# Cynara_Viride.net
KiCad netlist of a schematic drawn in EAGLE
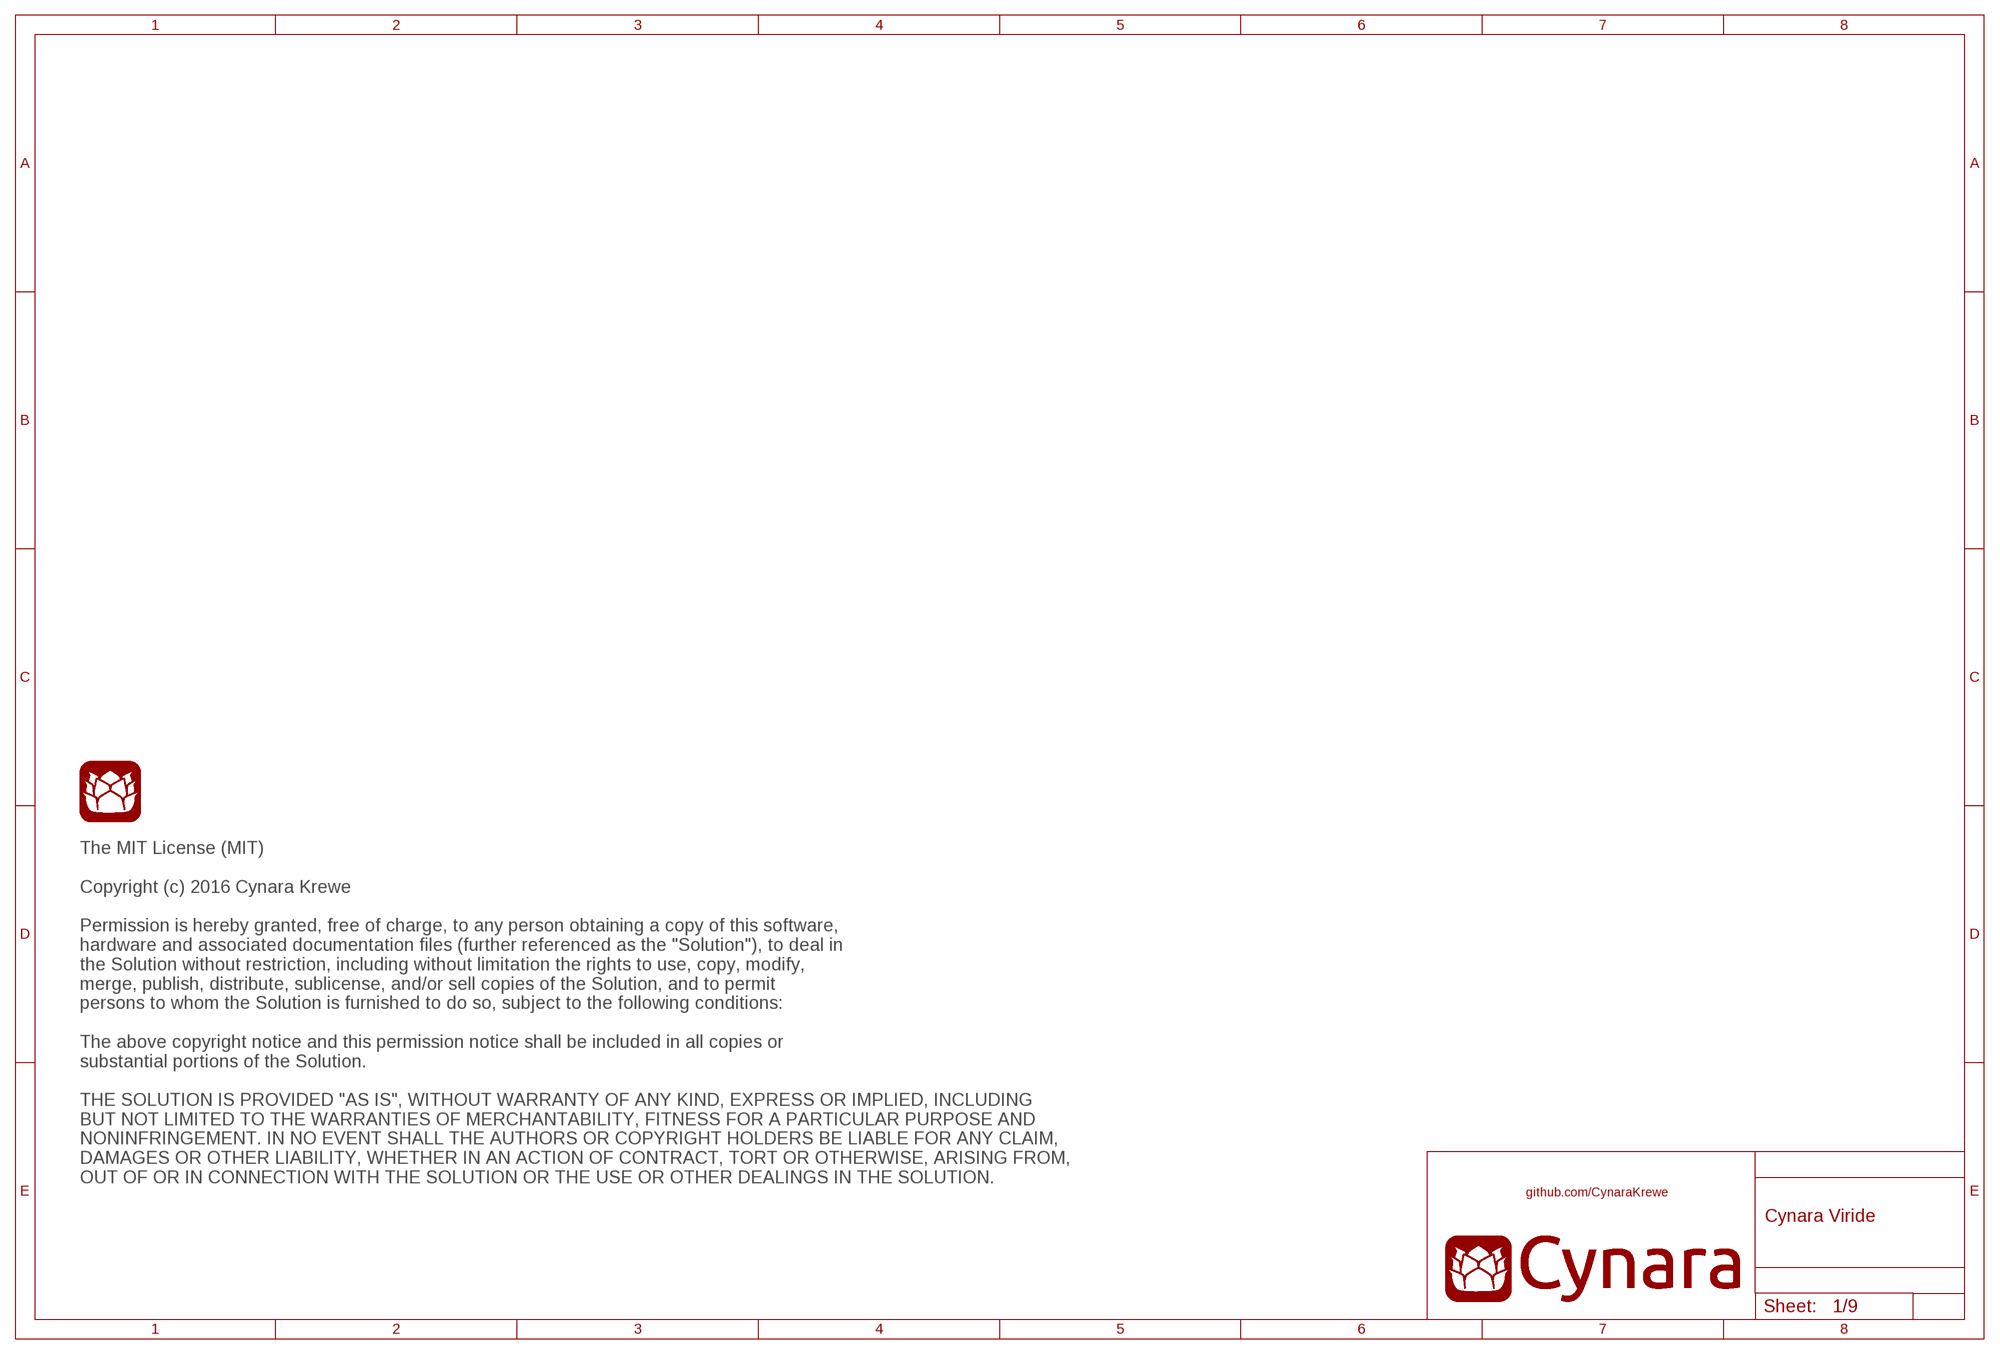
[diagram p0: schematic, sheet 1]
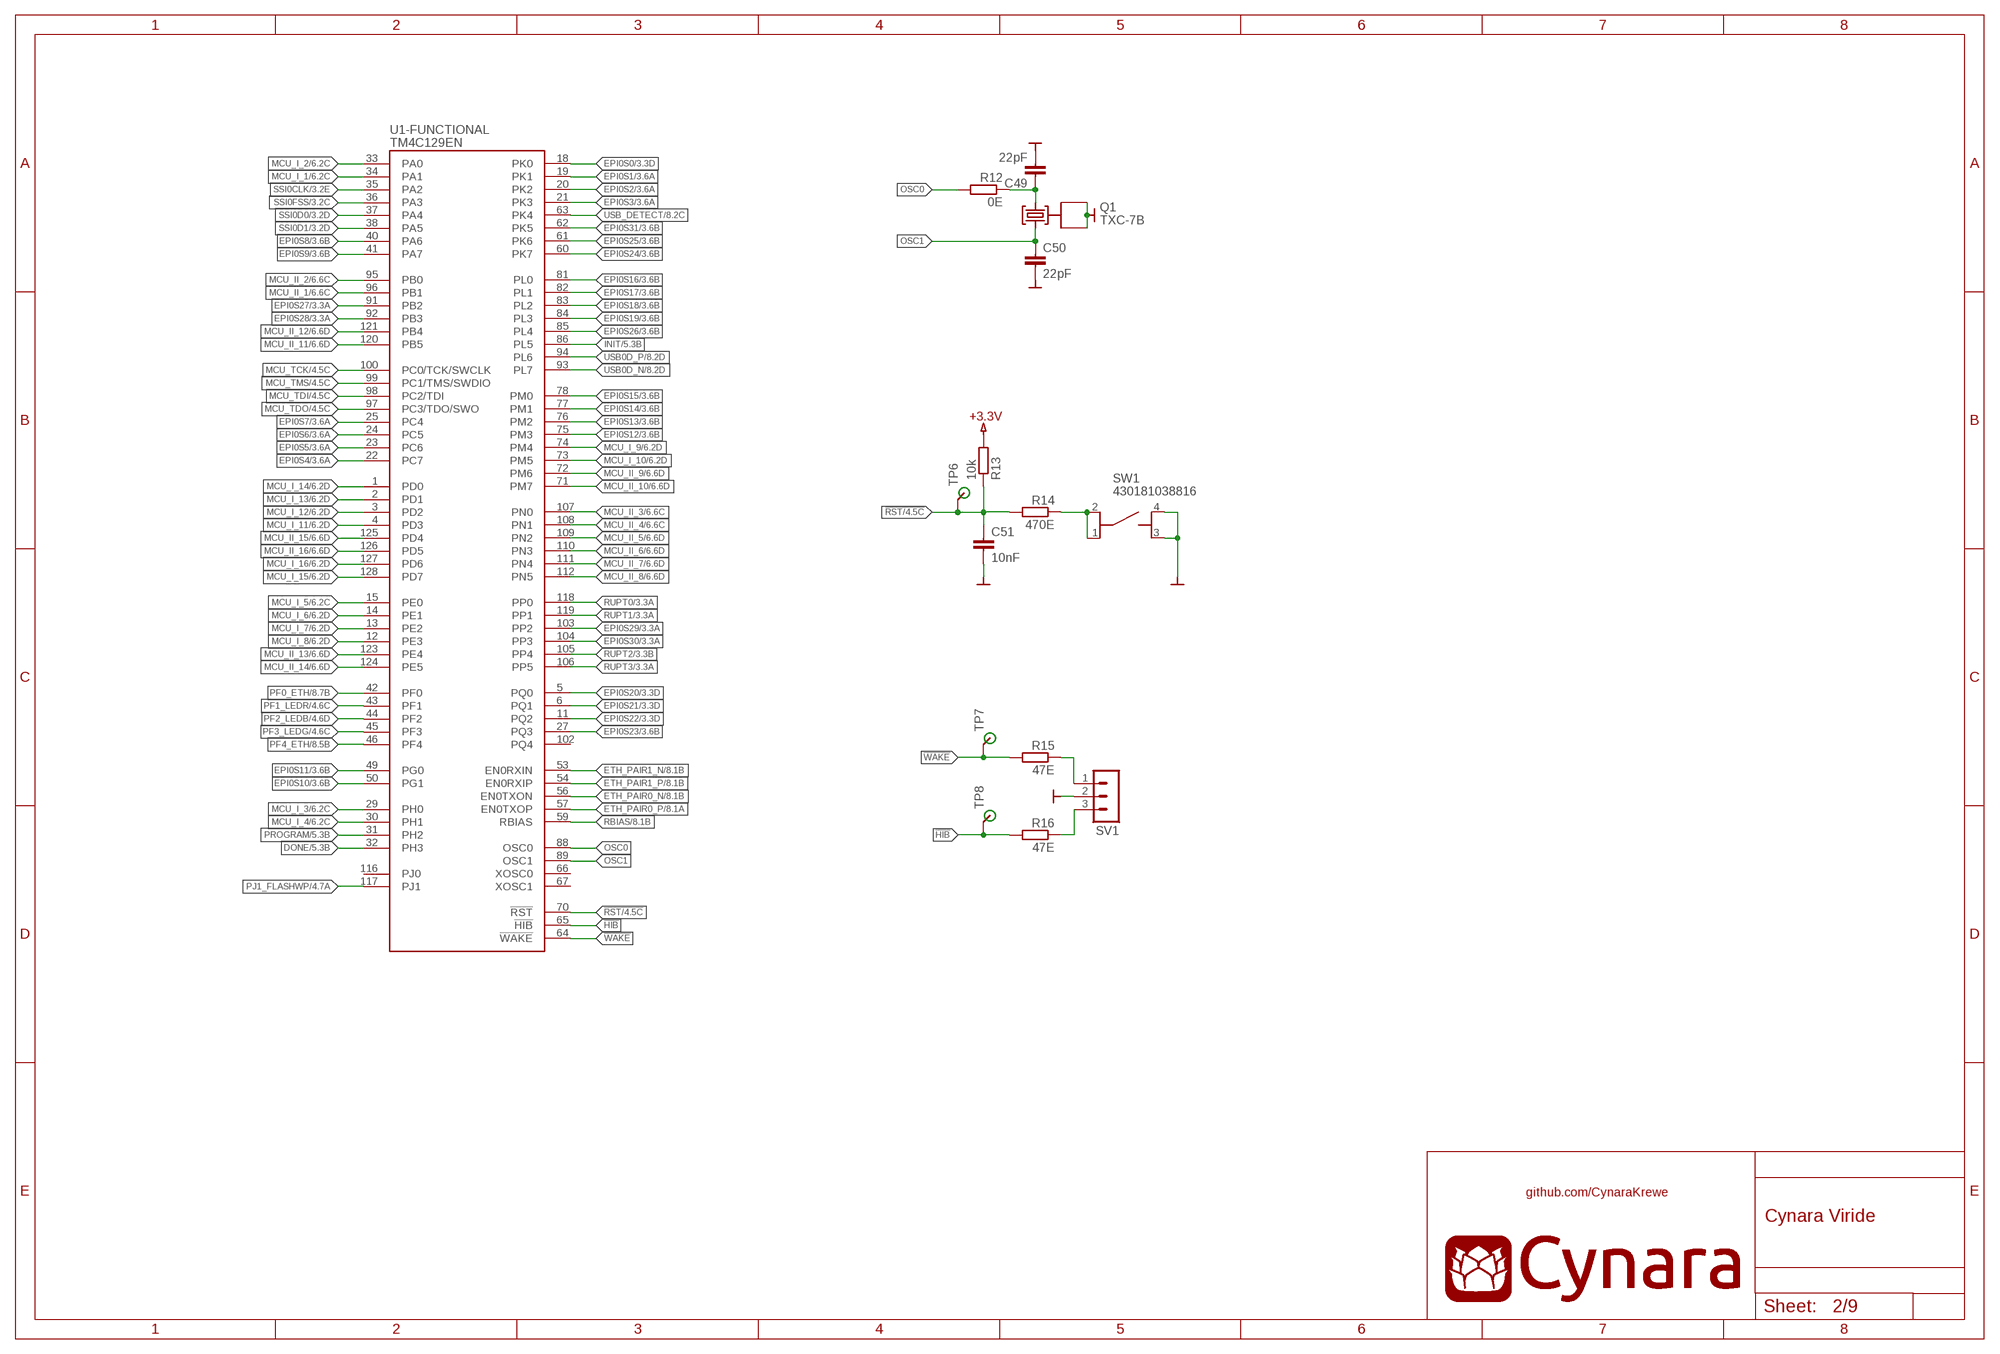
[diagram p1: schematic, sheet 2]
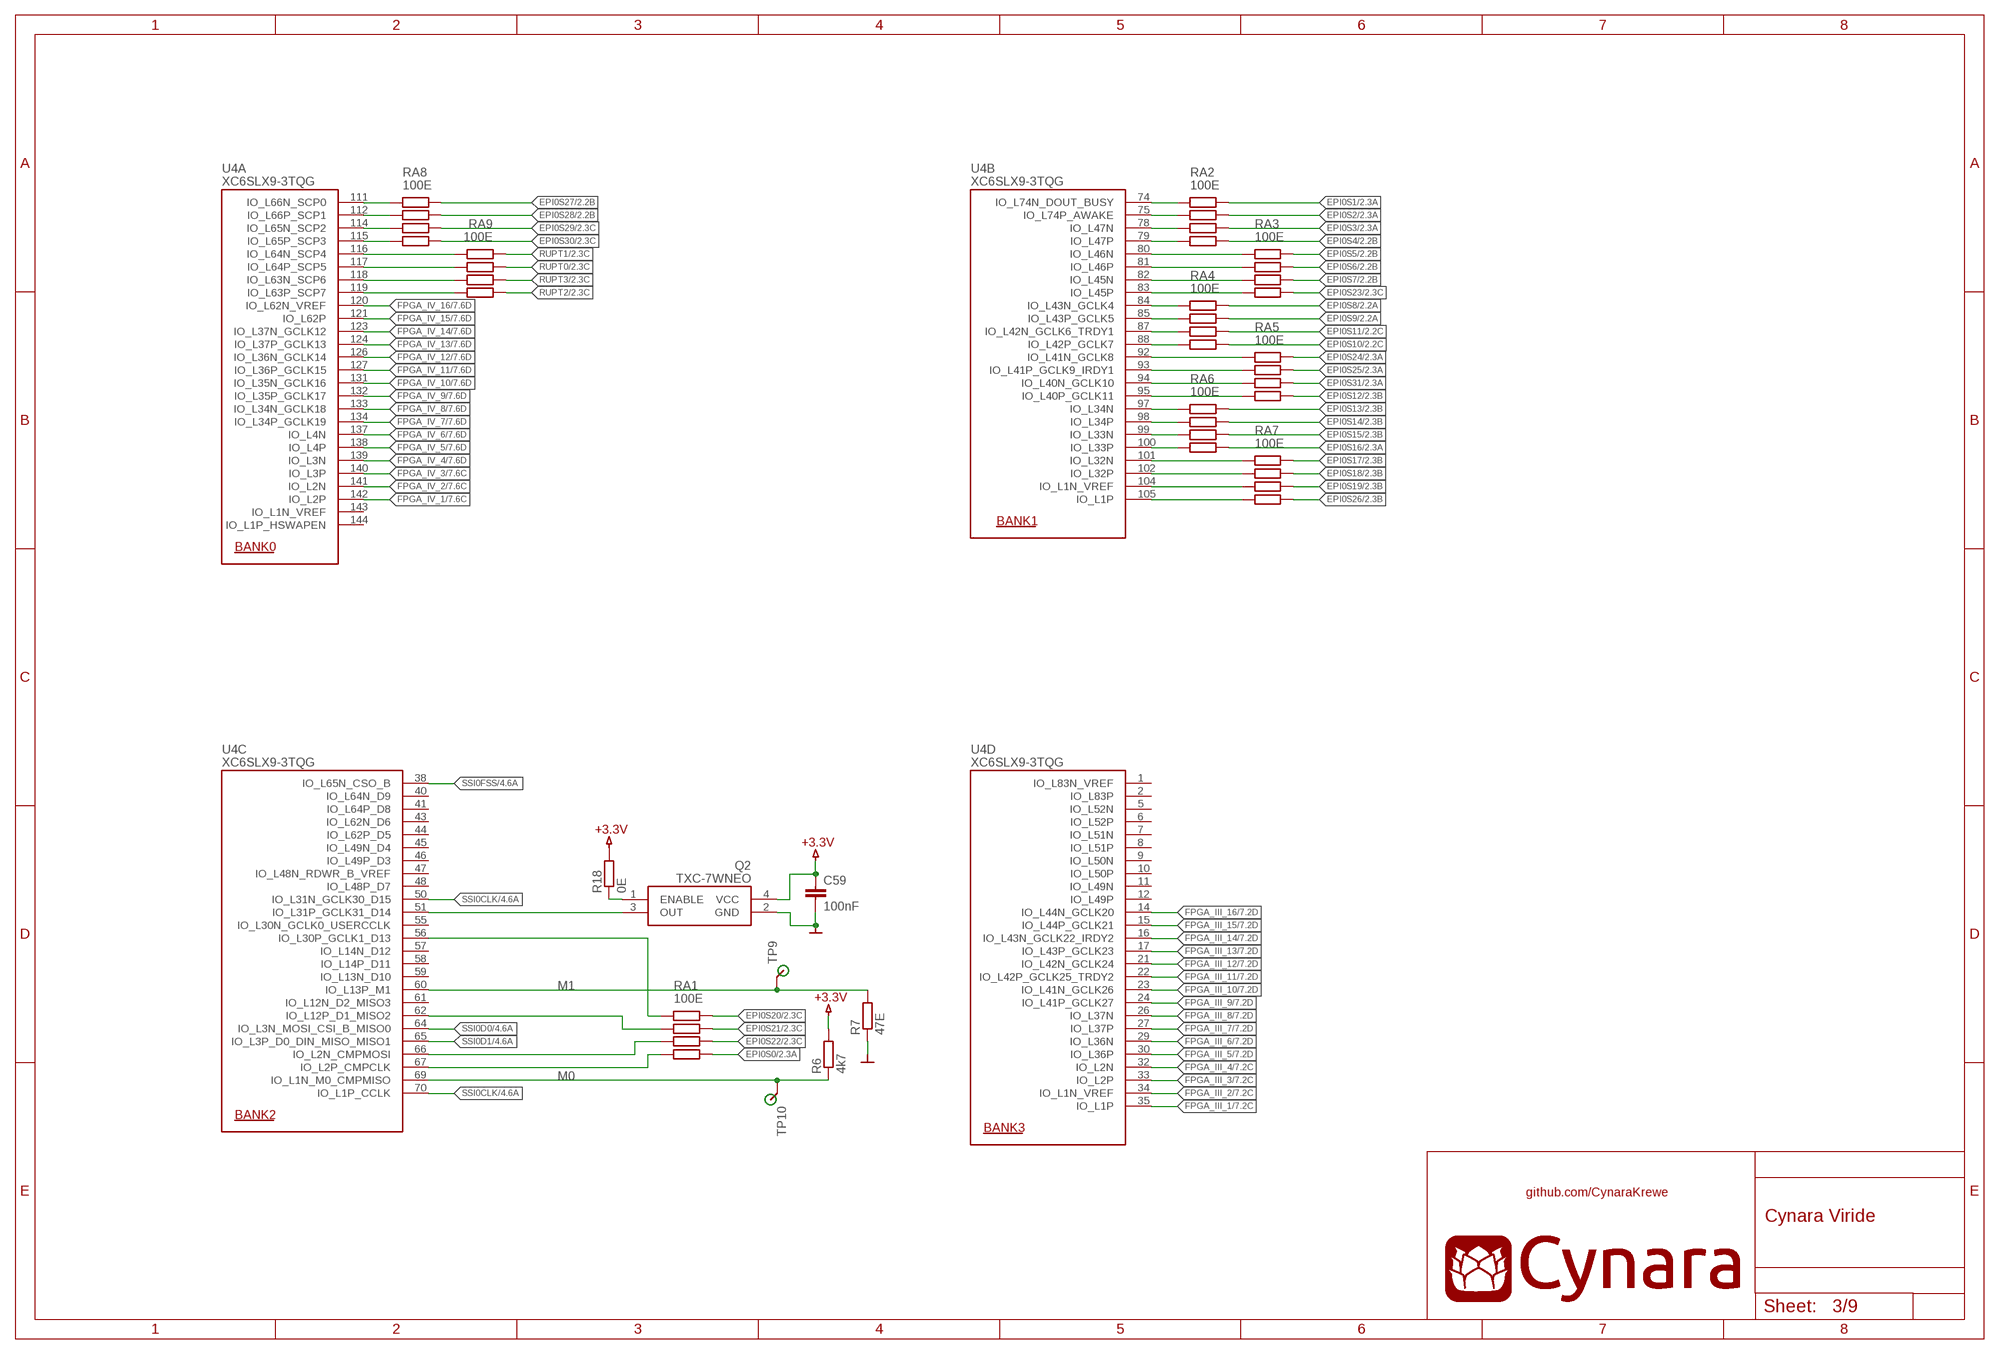
[diagram p2: schematic, sheet 3]
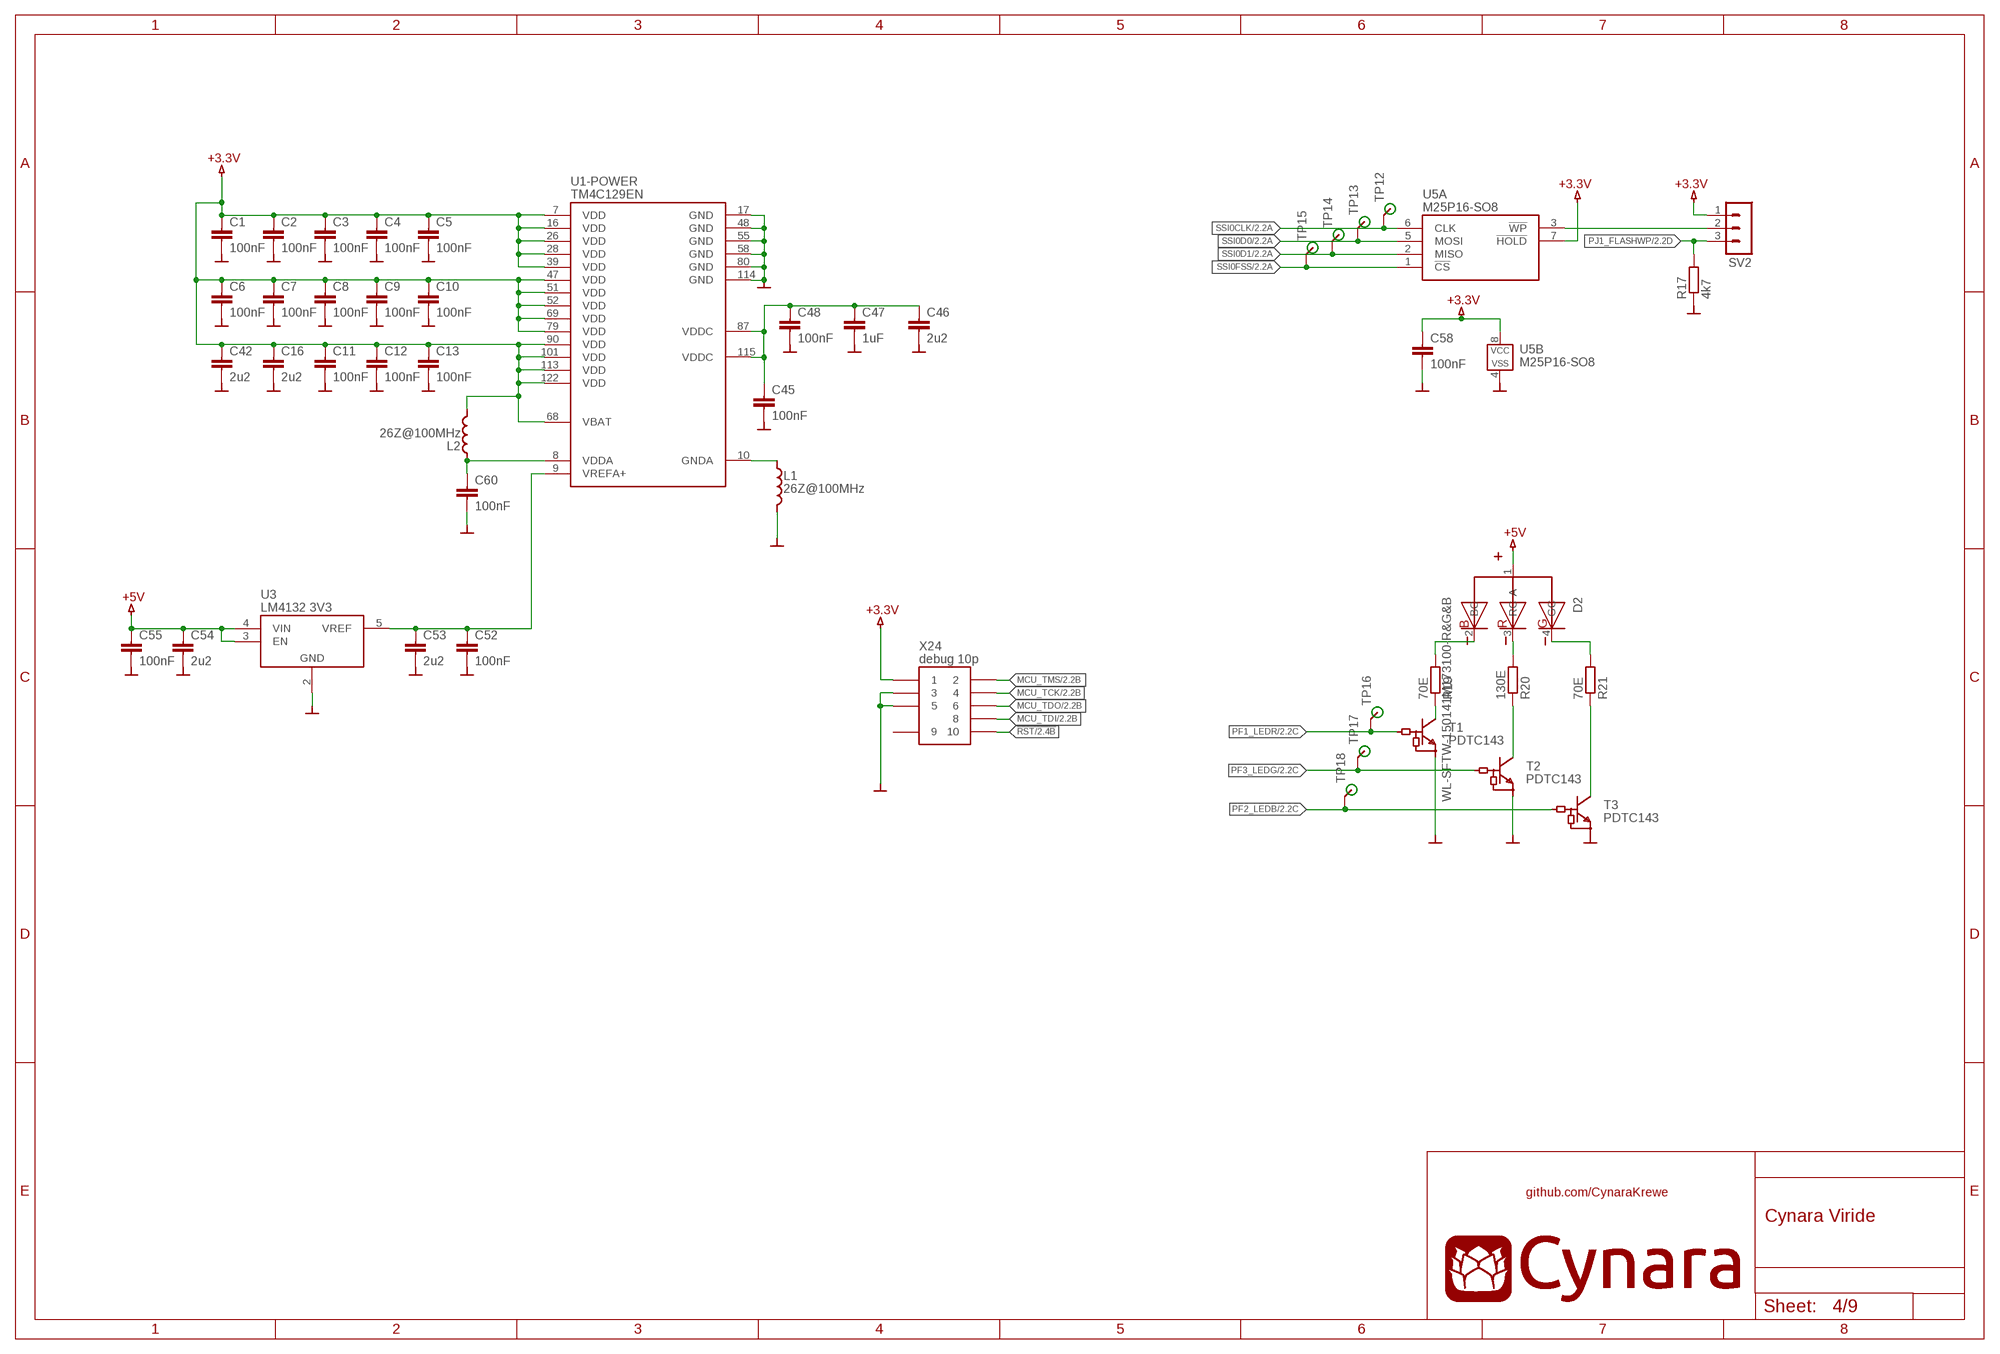
[diagram p3: schematic, sheet 4]
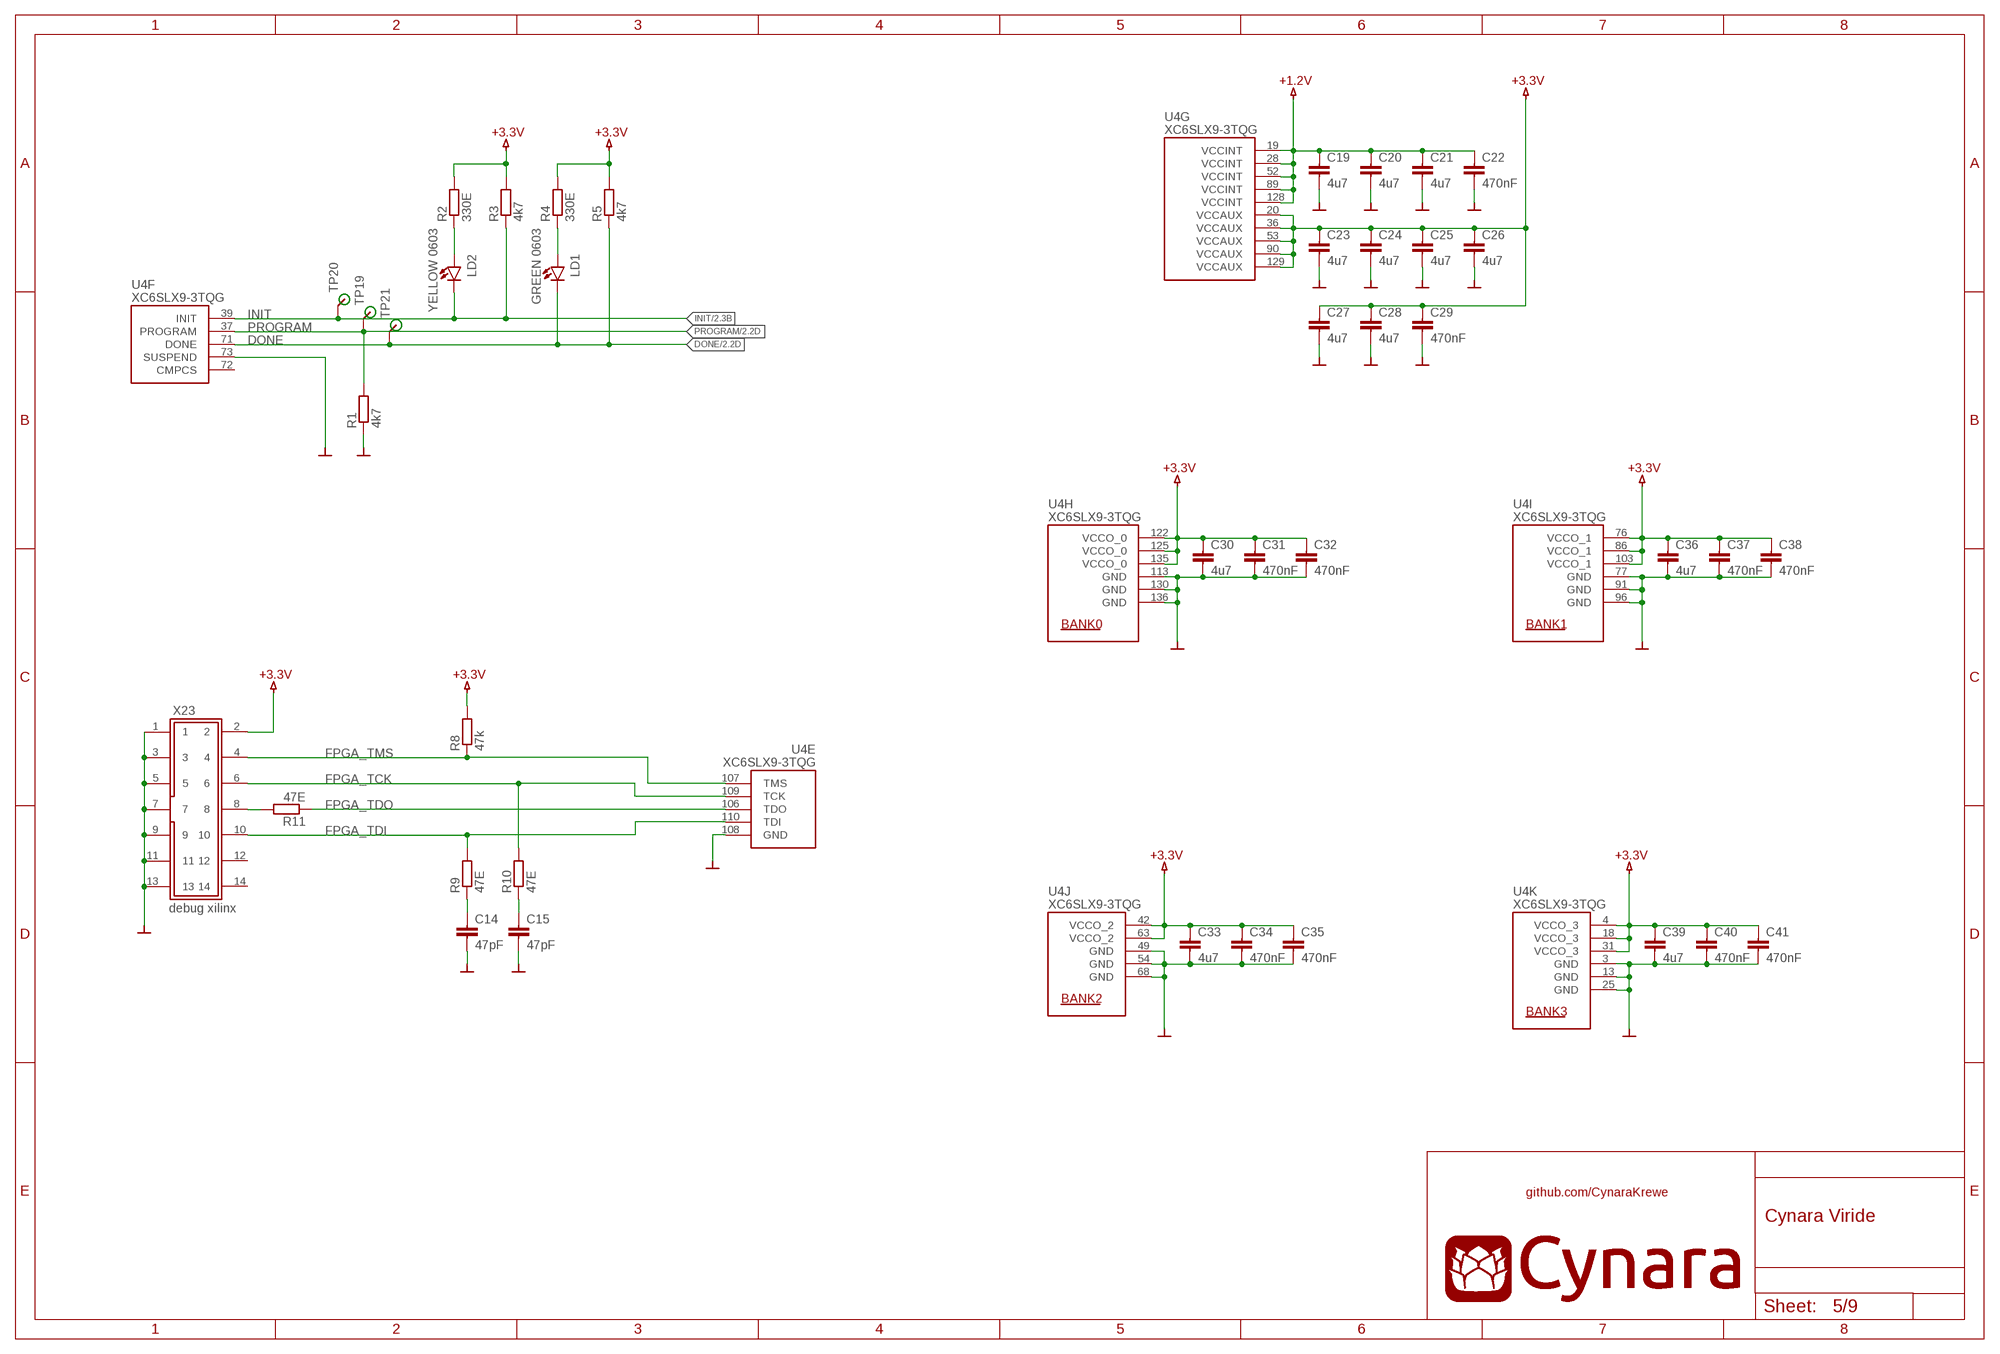
[diagram p4: schematic, sheet 5]
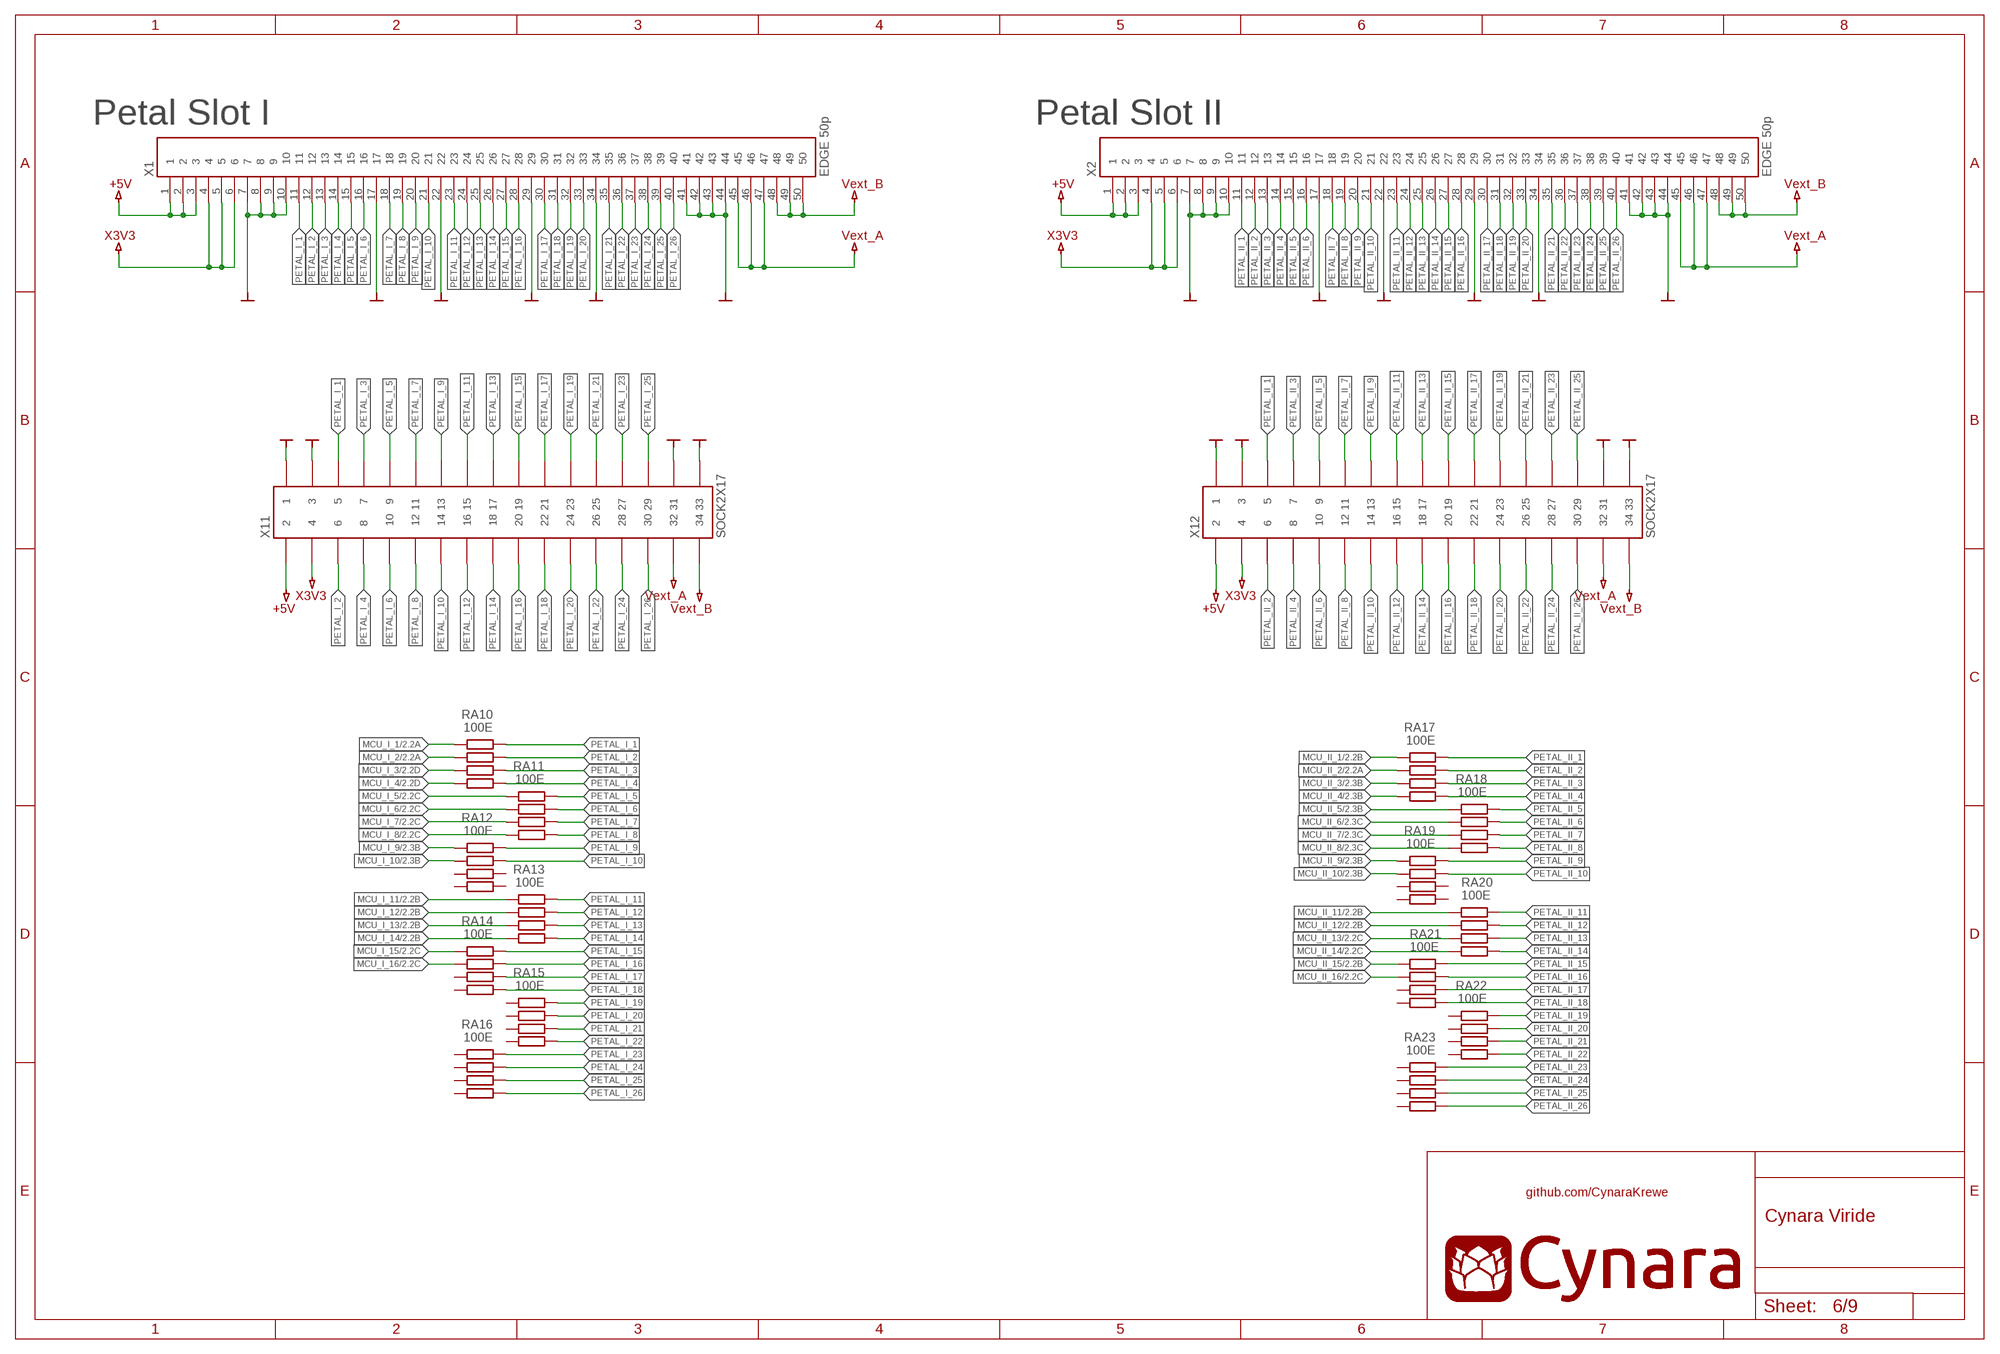
[diagram p5: schematic, sheet 6]
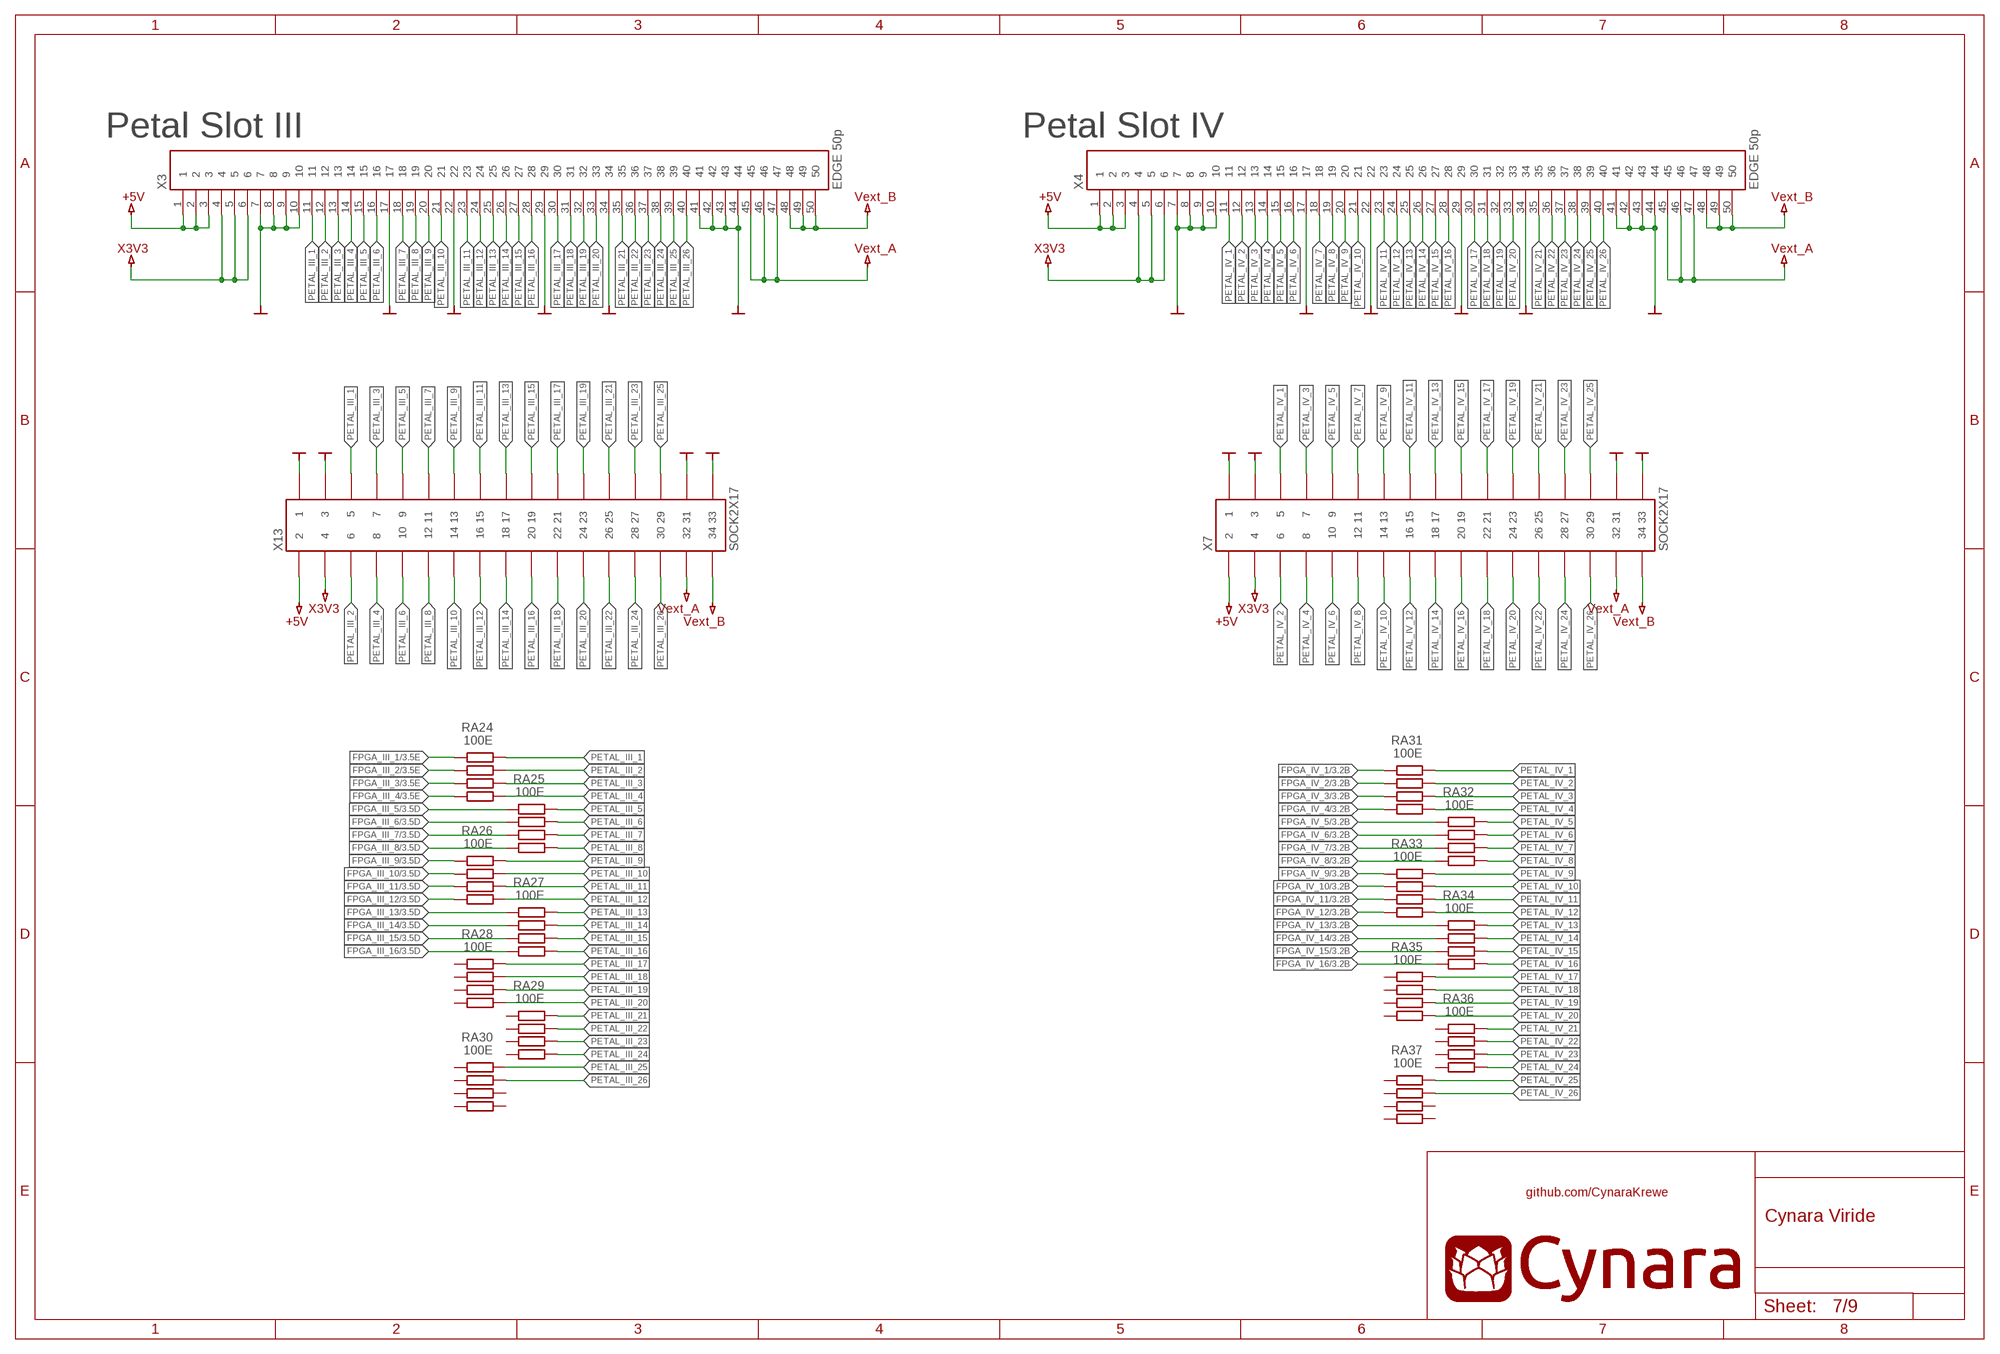
[diagram p6: schematic, sheet 7]
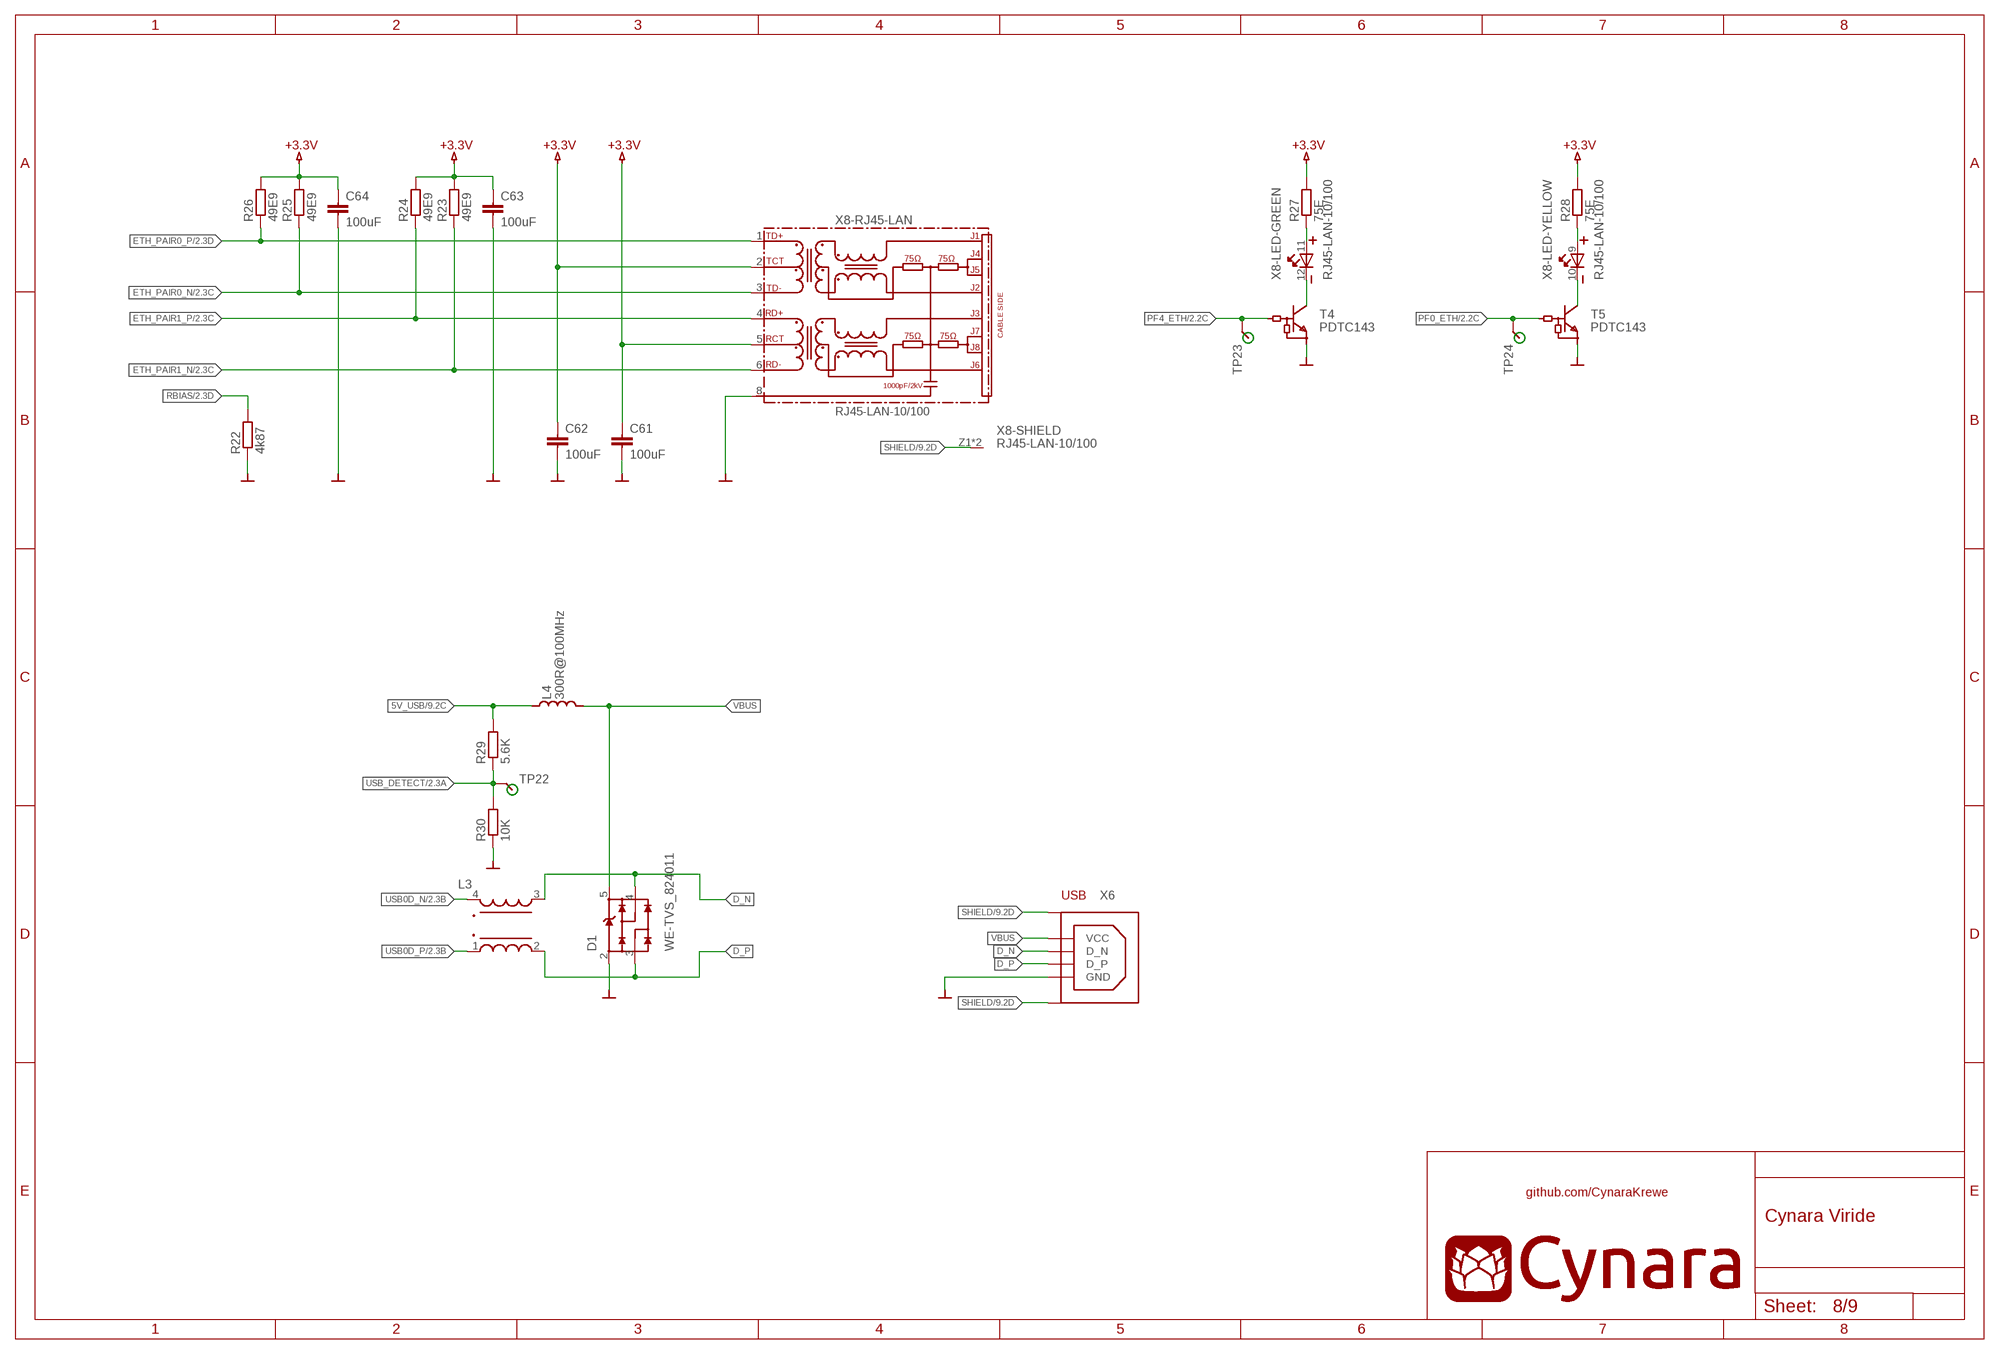
[diagram p7: schematic, sheet 8]
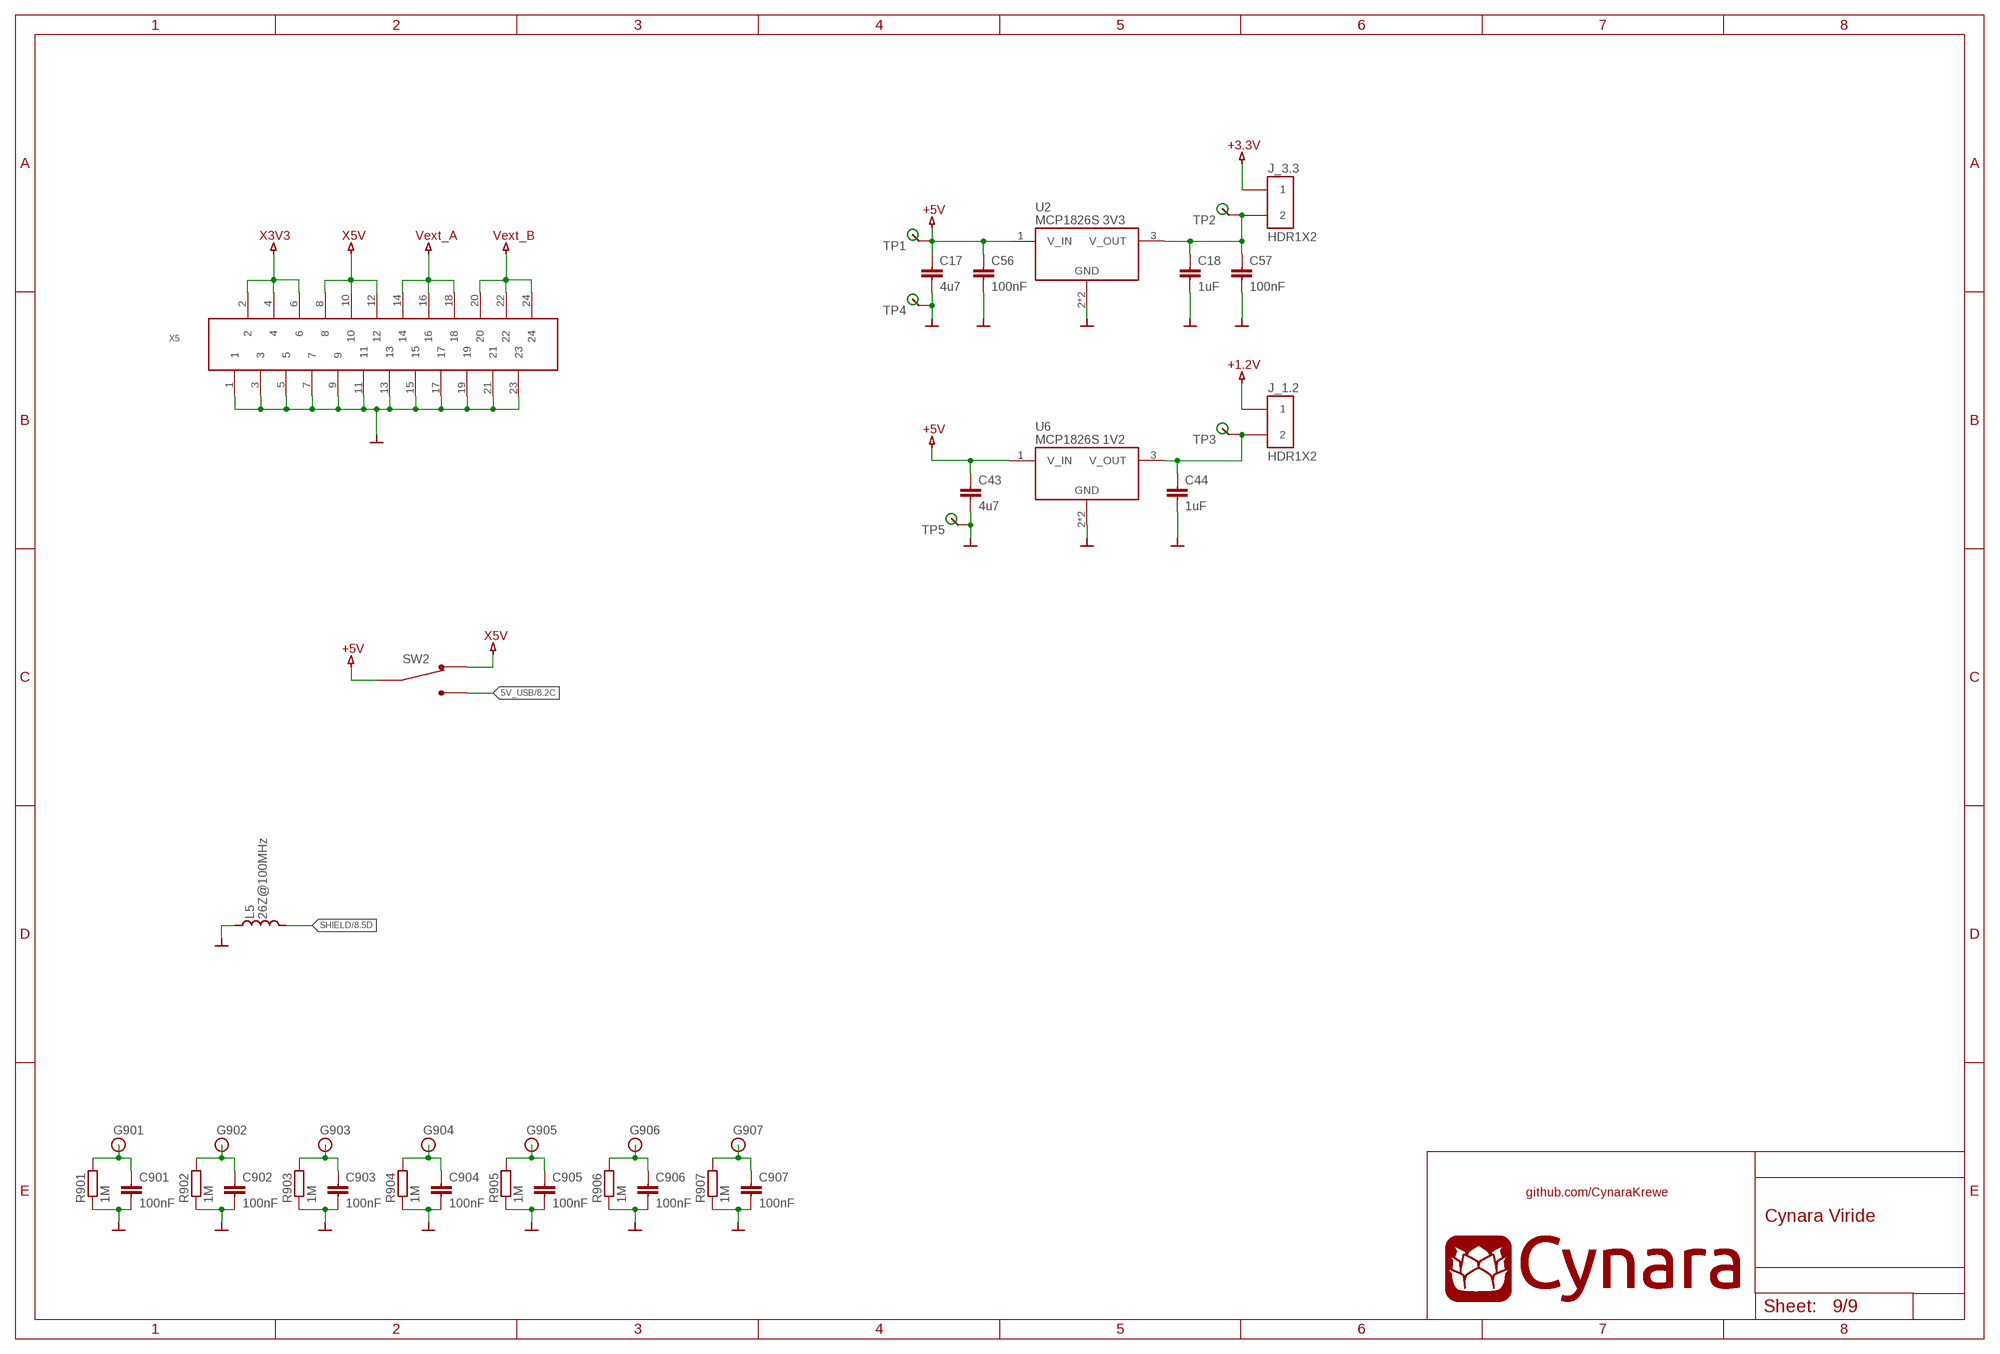
[diagram p8: schematic, sheet 9]

(export (version "E")
  (design (tool "Eeschema 10.0.6"))
  (components
    (comp (ref "C61")
      (value "100uF")
      (footprint "eagle-import:C0603")
      (libsource (lib "eagle-import") (part "C-EUC0603"))
    )
    (comp (ref "C62")
      (value "100uF")
      (footprint "eagle-import:C0603")
      (libsource (lib "eagle-import") (part "C-EUC0603"))
    )
    (comp (ref "C63")
      (value "100uF")
      (footprint "eagle-import:C0603")
      (libsource (lib "eagle-import") (part "C-EUC0603"))
    )
    (comp (ref "C64")
      (value "100uF")
      (footprint "eagle-import:C0603")
      (libsource (lib "eagle-import") (part "C-EUC0603"))
    )
    (comp (ref "D1")
      (value "WE-TVS_824011")
      (footprint "eagle-import:WE-TVS_SOT23-5L")
      (libsource (lib "eagle-import") (part "WE-TVS_824011"))
    )
    (comp (ref "L3")
      (value "WE-CNSW_1206")
      (footprint "eagle-import:WE-CNSW_1206")
      (libsource (lib "eagle-import") (part "WE-CNSW_1206"))
    )
    (comp (ref "L4")
      (value "300R@100MHz")
      (footprint "eagle-import:L1608")
      (fields (field (name "MANUFACTURER") "Wurth") (field (name "MANUFACTURERPARTNO") "742792641"))
      (libsource (lib "eagle-import") (part "BEAD_[0603]300R@100MHZ"))
    )
    (comp (ref "R22")
      (value "4k87")
      (footprint "eagle-import:R0603")
      (libsource (lib "eagle-import") (part "R-EU_R0603"))
    )
    (comp (ref "R23")
      (value "49E9")
      (footprint "eagle-import:R0603")
      (libsource (lib "eagle-import") (part "R-EU_R0603"))
    )
    (comp (ref "R24")
      (value "49E9")
      (footprint "eagle-import:R0603")
      (libsource (lib "eagle-import") (part "R-EU_R0603"))
    )
    (comp (ref "R25")
      (value "49E9")
      (footprint "eagle-import:R0603")
      (libsource (lib "eagle-import") (part "R-EU_R0603"))
    )
    (comp (ref "R26")
      (value "49E9")
      (footprint "eagle-import:R0603")
      (libsource (lib "eagle-import") (part "R-EU_R0603"))
    )
    (comp (ref "R27")
      (value "75E")
      (footprint "eagle-import:R0603")
      (libsource (lib "eagle-import") (part "R-EU_R0603"))
    )
    (comp (ref "R28")
      (value "75E")
      (footprint "eagle-import:R0603")
      (libsource (lib "eagle-import") (part "R-EU_R0603"))
    )
    (comp (ref "R29")
      (value "5.6K")
      (footprint "eagle-import:R0603")
      (libsource (lib "eagle-import") (part "R-EU_R0603"))
    )
    (comp (ref "R30")
      (value "10K")
      (footprint "eagle-import:R0603")
      (libsource (lib "eagle-import") (part "R-EU_R0603"))
    )
    (comp (ref "T4")
      (value "PDTC143")
      (footprint "eagle-import:SOT23-3")
      (fields (field (name "MANUFACTURER") "NXP") (field (name "MANUFACTURERPARTNO") "PDTC143ET,215"))
      (libsource (lib "eagle-import") (part "DIGITAL_TRANSISTOR4K7"))
    )
    (comp (ref "T5")
      (value "PDTC143")
      (footprint "eagle-import:SOT23-3")
      (fields (field (name "MANUFACTURER") "NXP") (field (name "MANUFACTURERPARTNO") "PDTC143ET,215"))
      (libsource (lib "eagle-import") (part "DIGITAL_TRANSISTOR4K7"))
    )
    (comp (ref "TP22")
      (value "TESTPAD-SMD")
      (footprint "eagle-import:TP-SMD")
      (libsource (lib "eagle-import") (part "TESTPAD-SMD"))
    )
    (comp (ref "TP23")
      (value "TESTPAD-SMD")
      (footprint "eagle-import:TP-SMD")
      (libsource (lib "eagle-import") (part "TESTPAD-SMD"))
    )
    (comp (ref "TP24")
      (value "TESTPAD-SMD")
      (footprint "eagle-import:TP-SMD")
      (libsource (lib "eagle-import") (part "TESTPAD-SMD"))
    )
    (comp (ref "X6")
      (value "USB2.0-TYPE-B")
      (footprint "eagle-import:61400416121")
      (fields (field (name "MANUFACTURER") "Wurth") (field (name "MANUFACTURERPARTNO") "61400416121"))
      (libsource (lib "eagle-import") (part "USB2.0-TYPE-B"))
    )
    (comp (ref "X8")
      (value "RJ45-LAN-10/100")
      (footprint "eagle-import:74990-WITH-LED-TYPE1")
      (fields
        (field (name "MANUFACTURER") "Würth Elektronik eiSos GmbH")
        (field (name "CREATED-BY") "Christin Zierenner")
      )
      (libsource (lib "eagle-import") (part "RJ45-LAN-10/100"))
    )
    (comp (ref "U$21")
      (value "CYNARA_FRONT")
      (footprint "eagle-import:CYNARA_BELOW_W15MM")
      (libsource (lib "eagle-import") (part "CYNARA_FRONT"))
    )
    (comp (ref "C59")
      (value "100nF")
      (footprint "eagle-import:C0603")
      (libsource (lib "eagle-import") (part "C-EUC0603"))
    )
    (comp (ref "Q2")
      (value "TXC-7WNEO")
      (footprint "eagle-import:TXC-7W")
      (libsource (lib "eagle-import") (part "TXC-7WNEO"))
    )
    (comp (ref "R6")
      (value "4k7")
      (footprint "eagle-import:R0603")
      (libsource (lib "eagle-import") (part "R-EU_R0603"))
    )
    (comp (ref "R7")
      (value "47E")
      (footprint "eagle-import:R0603")
      (libsource (lib "eagle-import") (part "R-EU_R0603"))
    )
    (comp (ref "R18")
      (value "0E")
      (footprint "eagle-import:R0603")
      (libsource (lib "eagle-import") (part "R-EU_R0603"))
    )
    (comp (ref "RA1")
      (value "100E")
      (footprint "eagle-import:CRA06S")
      (libsource (lib "eagle-import") (part "RES-ARRAY--4X100E"))
    )
    (comp (ref "RA2")
      (value "100E")
      (footprint "eagle-import:CRA06S")
      (libsource (lib "eagle-import") (part "RES-ARRAY--4X100E"))
    )
    (comp (ref "RA3")
      (value "100E")
      (footprint "eagle-import:CRA06S")
      (libsource (lib "eagle-import") (part "RES-ARRAY--4X100E"))
    )
    (comp (ref "RA4")
      (value "100E")
      (footprint "eagle-import:CRA06S")
      (libsource (lib "eagle-import") (part "RES-ARRAY--4X100E"))
    )
    (comp (ref "RA5")
      (value "100E")
      (footprint "eagle-import:CRA06S")
      (libsource (lib "eagle-import") (part "RES-ARRAY--4X100E"))
    )
    (comp (ref "RA6")
      (value "100E")
      (footprint "eagle-import:CRA06S")
      (libsource (lib "eagle-import") (part "RES-ARRAY--4X100E"))
    )
    (comp (ref "RA7")
      (value "100E")
      (footprint "eagle-import:CRA06S")
      (libsource (lib "eagle-import") (part "RES-ARRAY--4X100E"))
    )
    (comp (ref "RA8")
      (value "100E")
      (footprint "eagle-import:CRA06S")
      (libsource (lib "eagle-import") (part "RES-ARRAY--4X100E"))
    )
    (comp (ref "RA9")
      (value "100E")
      (footprint "eagle-import:CRA06S")
      (libsource (lib "eagle-import") (part "RES-ARRAY--4X100E"))
    )
    (comp (ref "TP9")
      (value "TESTPAD-SMD")
      (footprint "eagle-import:TP-SMD")
      (libsource (lib "eagle-import") (part "TESTPAD-SMD"))
    )
    (comp (ref "TP10")
      (value "TESTPAD-SMD")
      (footprint "eagle-import:TP-SMD")
      (libsource (lib "eagle-import") (part "TESTPAD-SMD"))
    )
    (comp (ref "U4")
      (value "XC6SLX9-3TQG")
      (footprint "eagle-import:TQG144")
      (fields (field (name "MANUFACTURER") "Xilinx") (field (name "MANUFACTURERPARTNO") "XC6SLX9-3TQG144C"))
      (libsource (lib "eagle-import") (part "XC6SLX9-3TQG144C"))
    )
    (comp (ref "C1")
      (value "100nF")
      (footprint "eagle-import:C0603")
      (libsource (lib "eagle-import") (part "C-EUC0603"))
    )
    (comp (ref "C2")
      (value "100nF")
      (footprint "eagle-import:C0603")
      (libsource (lib "eagle-import") (part "C-EUC0603"))
    )
    (comp (ref "C3")
      (value "100nF")
      (footprint "eagle-import:C0603")
      (libsource (lib "eagle-import") (part "C-EUC0603"))
    )
    (comp (ref "C4")
      (value "100nF")
      (footprint "eagle-import:C0603")
      (libsource (lib "eagle-import") (part "C-EUC0603"))
    )
    (comp (ref "C5")
      (value "100nF")
      (footprint "eagle-import:C0603")
      (libsource (lib "eagle-import") (part "C-EUC0603"))
    )
    (comp (ref "C6")
      (value "100nF")
      (footprint "eagle-import:C0603")
      (libsource (lib "eagle-import") (part "C-EUC0603"))
    )
    (comp (ref "C7")
      (value "100nF")
      (footprint "eagle-import:C0603")
      (libsource (lib "eagle-import") (part "C-EUC0603"))
    )
    (comp (ref "C8")
      (value "100nF")
      (footprint "eagle-import:C0603")
      (libsource (lib "eagle-import") (part "C-EUC0603"))
    )
    (comp (ref "C9")
      (value "100nF")
      (footprint "eagle-import:C0603")
      (libsource (lib "eagle-import") (part "C-EUC0603"))
    )
    (comp (ref "C10")
      (value "100nF")
      (footprint "eagle-import:C0603")
      (libsource (lib "eagle-import") (part "C-EUC0603"))
    )
    (comp (ref "C11")
      (value "100nF")
      (footprint "eagle-import:C0603")
      (libsource (lib "eagle-import") (part "C-EUC0603"))
    )
    (comp (ref "C12")
      (value "100nF")
      (footprint "eagle-import:C0603")
      (libsource (lib "eagle-import") (part "C-EUC0603"))
    )
    (comp (ref "C13")
      (value "100nF")
      (footprint "eagle-import:C0603")
      (libsource (lib "eagle-import") (part "C-EUC0603"))
    )
    (comp (ref "C16")
      (value "2u2")
      (footprint "eagle-import:C0603")
      (libsource (lib "eagle-import") (part "C-EUC0603"))
    )
    (comp (ref "C42")
      (value "2u2")
      (footprint "eagle-import:C0603")
      (libsource (lib "eagle-import") (part "C-EUC0603"))
    )
    (comp (ref "C45")
      (value "100nF")
      (footprint "eagle-import:C0603")
      (libsource (lib "eagle-import") (part "C-EUC0603"))
    )
    (comp (ref "C46")
      (value "2u2")
      (footprint "eagle-import:C0603")
      (libsource (lib "eagle-import") (part "C-EUC0603"))
    )
    (comp (ref "C47")
      (value "1uF")
      (footprint "eagle-import:C0603")
      (libsource (lib "eagle-import") (part "C-EUC0603"))
    )
    (comp (ref "C48")
      (value "100nF")
      (footprint "eagle-import:C0603")
      (libsource (lib "eagle-import") (part "C-EUC0603"))
    )
    (comp (ref "C52")
      (value "100nF")
      (footprint "eagle-import:C0603")
      (libsource (lib "eagle-import") (part "C-EUC0603"))
    )
    (comp (ref "C53")
      (value "2u2")
      (footprint "eagle-import:C0603")
      (libsource (lib "eagle-import") (part "C-EUC0603"))
    )
    (comp (ref "C54")
      (value "2u2")
      (footprint "eagle-import:C0603")
      (libsource (lib "eagle-import") (part "C-EUC0603"))
    )
    (comp (ref "C55")
      (value "100nF")
      (footprint "eagle-import:C0603")
      (libsource (lib "eagle-import") (part "C-EUC0603"))
    )
    (comp (ref "C58")
      (value "100nF")
      (footprint "eagle-import:C0603")
      (libsource (lib "eagle-import") (part "C-EUC0603"))
    )
    (comp (ref "C60")
      (value "100nF")
      (footprint "eagle-import:C0603")
      (libsource (lib "eagle-import") (part "C-EUC0603"))
    )
    (comp (ref "D2")
      (value "WL-SFTW-150141M173100-R&G&B")
      (footprint "eagle-import:3528-COMMON-ANODE")
      (libsource (lib "eagle-import") (part "WL-SFTW-150141M173100-R&G&B"))
    )
    (comp (ref "L1")
      (value "26Z@100MHz")
      (footprint "eagle-import:L1608")
      (fields (field (name "MANUFACTURER") "Murata") (field (name "MANUFACTURERPARTNO") "BLM18KG260TN1D"))
      (libsource (lib "eagle-import") (part "BEAD_[0603]26Z@100MHZ"))
    )
    (comp (ref "L2")
      (value "26Z@100MHz")
      (footprint "eagle-import:L1608")
      (fields (field (name "MANUFACTURER") "Murata") (field (name "MANUFACTURERPARTNO") "BLM18KG260TN1D"))
      (libsource (lib "eagle-import") (part "BEAD_[0603]26Z@100MHZ"))
    )
    (comp (ref "R17")
      (value "4k7")
      (footprint "eagle-import:R0603")
      (libsource (lib "eagle-import") (part "R-EU_R0603"))
    )
    (comp (ref "R19")
      (value "70E")
      (footprint "eagle-import:R0603")
      (libsource (lib "eagle-import") (part "R-EU_R0603"))
    )
    (comp (ref "R20")
      (value "130E")
      (footprint "eagle-import:R0603")
      (libsource (lib "eagle-import") (part "R-EU_R0603"))
    )
    (comp (ref "R21")
      (value "70E")
      (footprint "eagle-import:R0603")
      (libsource (lib "eagle-import") (part "R-EU_R0603"))
    )
    (comp (ref "SV2")
      (value "MA03-1")
      (footprint "eagle-import:MA03-1")
      (libsource (lib "eagle-import") (part "MA03-1"))
    )
    (comp (ref "T1")
      (value "PDTC143")
      (footprint "eagle-import:SOT23-3")
      (fields (field (name "MANUFACTURER") "NXP") (field (name "MANUFACTURERPARTNO") "PDTC143ET,215"))
      (libsource (lib "eagle-import") (part "DIGITAL_TRANSISTOR4K7"))
    )
    (comp (ref "T2")
      (value "PDTC143")
      (footprint "eagle-import:SOT23-3")
      (fields (field (name "MANUFACTURER") "NXP") (field (name "MANUFACTURERPARTNO") "PDTC143ET,215"))
      (libsource (lib "eagle-import") (part "DIGITAL_TRANSISTOR4K7"))
    )
    (comp (ref "T3")
      (value "PDTC143")
      (footprint "eagle-import:SOT23-3")
      (fields (field (name "MANUFACTURER") "NXP") (field (name "MANUFACTURERPARTNO") "PDTC143ET,215"))
      (libsource (lib "eagle-import") (part "DIGITAL_TRANSISTOR4K7"))
    )
    (comp (ref "TP12")
      (value "TESTPAD-SMD")
      (footprint "eagle-import:TP-SMD")
      (libsource (lib "eagle-import") (part "TESTPAD-SMD"))
    )
    (comp (ref "TP13")
      (value "TESTPAD-SMD")
      (footprint "eagle-import:TP-SMD")
      (libsource (lib "eagle-import") (part "TESTPAD-SMD"))
    )
    (comp (ref "TP14")
      (value "TESTPAD-SMD")
      (footprint "eagle-import:TP-SMD")
      (libsource (lib "eagle-import") (part "TESTPAD-SMD"))
    )
    (comp (ref "TP15")
      (value "TESTPAD-SMD")
      (footprint "eagle-import:TP-SMD")
      (libsource (lib "eagle-import") (part "TESTPAD-SMD"))
    )
    (comp (ref "TP16")
      (value "TESTPAD-SMD")
      (footprint "eagle-import:TP-SMD")
      (libsource (lib "eagle-import") (part "TESTPAD-SMD"))
    )
    (comp (ref "TP17")
      (value "TESTPAD-SMD")
      (footprint "eagle-import:TP-SMD")
      (libsource (lib "eagle-import") (part "TESTPAD-SMD"))
    )
    (comp (ref "TP18")
      (value "TESTPAD-SMD")
      (footprint "eagle-import:TP-SMD")
      (libsource (lib "eagle-import") (part "TESTPAD-SMD"))
    )
    (comp (ref "U1")
      (value "TM4C129EN")
      (footprint "eagle-import:S-PQFP-G128")
      (fields
        (field (name "MANUFACTURER") "Texas Instruments")
        (field (name "MANUFACTURERPARTNO") "TM4C129ENCPDT")
      )
      (libsource (lib "eagle-import") (part "SPLIT-TM4C129ENCPDT-TQFP128"))
    )
    (comp (ref "U3")
      (value "LM4132 3V3")
      (footprint "eagle-import:DBV(R-PDSO-G5)")
      (fields
        (field (name "MANUFACTURER") "Texas Instruments")
        (field (name "MANUFACTURERPARTNO") "LM4132AMF-3.3/NOPB")
      )
      (libsource (lib "eagle-import") (part "LM4132-3V3"))
    )
    (comp (ref "U5")
      (value "M25P16-SO8")
      (footprint "eagle-import:SOIC127P600X120-8N")
      (fields (field (name "MANUFACTURER") "Micron") (field (name "MANUFACTURERPARTNO") "M25P16-VMN6P"))
      (libsource (lib "eagle-import") (part "M25P16-SO8"))
    )
    (comp (ref "X24")
      (value "debug 10p")
      (footprint "eagle-import:DEBUG-CORTEXM10")
      (fields (field (name "MANUFACTURER") "SAMTEC") (field (name "MANUFACTURERPARTNO") "62101021021"))
      (libsource (lib "eagle-import") (part "DEBUG-CORTEXM10"))
    )
    (comp (ref "C14")
      (value "47pF")
      (footprint "eagle-import:C0603")
      (libsource (lib "eagle-import") (part "C-EUC0603"))
    )
    (comp (ref "C15")
      (value "47pF")
      (footprint "eagle-import:C0603")
      (libsource (lib "eagle-import") (part "C-EUC0603"))
    )
    (comp (ref "C19")
      (value "4u7")
      (footprint "eagle-import:C0603")
      (libsource (lib "eagle-import") (part "C-EUC0603"))
    )
    (comp (ref "C20")
      (value "4u7")
      (footprint "eagle-import:C0603")
      (libsource (lib "eagle-import") (part "C-EUC0603"))
    )
    (comp (ref "C21")
      (value "4u7")
      (footprint "eagle-import:C0603")
      (libsource (lib "eagle-import") (part "C-EUC0603"))
    )
    (comp (ref "C22")
      (value "470nF")
      (footprint "eagle-import:C0603")
      (libsource (lib "eagle-import") (part "C-EUC0603"))
    )
    (comp (ref "C23")
      (value "4u7")
      (footprint "eagle-import:C0603")
      (libsource (lib "eagle-import") (part "C-EUC0603"))
    )
    (comp (ref "C24")
      (value "4u7")
      (footprint "eagle-import:C0603")
      (libsource (lib "eagle-import") (part "C-EUC0603"))
    )
    (comp (ref "C25")
      (value "4u7")
      (footprint "eagle-import:C0603")
      (libsource (lib "eagle-import") (part "C-EUC0603"))
    )
    (comp (ref "C26")
      (value "4u7")
      (footprint "eagle-import:C0603")
      (libsource (lib "eagle-import") (part "C-EUC0603"))
    )
    (comp (ref "C27")
      (value "4u7")
      (footprint "eagle-import:C0603")
      (libsource (lib "eagle-import") (part "C-EUC0603"))
    )
    (comp (ref "C28")
      (value "4u7")
      (footprint "eagle-import:C0603")
      (libsource (lib "eagle-import") (part "C-EUC0603"))
    )
    (comp (ref "C29")
      (value "470nF")
      (footprint "eagle-import:C0603")
      (libsource (lib "eagle-import") (part "C-EUC0603"))
    )
    (comp (ref "C30")
      (value "4u7")
      (footprint "eagle-import:C0603")
      (libsource (lib "eagle-import") (part "C-EUC0603"))
    )
    (comp (ref "C31")
      (value "470nF")
      (footprint "eagle-import:C0603")
      (libsource (lib "eagle-import") (part "C-EUC0603"))
    )
    (comp (ref "C32")
      (value "470nF")
      (footprint "eagle-import:C0603")
      (libsource (lib "eagle-import") (part "C-EUC0603"))
    )
    (comp (ref "C33")
      (value "4u7")
      (footprint "eagle-import:C0603")
      (libsource (lib "eagle-import") (part "C-EUC0603"))
    )
    (comp (ref "C34")
      (value "470nF")
      (footprint "eagle-import:C0603")
      (libsource (lib "eagle-import") (part "C-EUC0603"))
    )
    (comp (ref "C35")
      (value "470nF")
      (footprint "eagle-import:C0603")
      (libsource (lib "eagle-import") (part "C-EUC0603"))
    )
    (comp (ref "C36")
      (value "4u7")
      (footprint "eagle-import:C0603")
      (libsource (lib "eagle-import") (part "C-EUC0603"))
    )
    (comp (ref "C37")
      (value "470nF")
      (footprint "eagle-import:C0603")
      (libsource (lib "eagle-import") (part "C-EUC0603"))
    )
    (comp (ref "C38")
      (value "470nF")
      (footprint "eagle-import:C0603")
      (libsource (lib "eagle-import") (part "C-EUC0603"))
    )
    (comp (ref "C39")
      (value "4u7")
      (footprint "eagle-import:C0603")
      (libsource (lib "eagle-import") (part "C-EUC0603"))
    )
    (comp (ref "C40")
      (value "470nF")
      (footprint "eagle-import:C0603")
      (libsource (lib "eagle-import") (part "C-EUC0603"))
    )
    (comp (ref "C41")
      (value "470nF")
      (footprint "eagle-import:C0603")
      (libsource (lib "eagle-import") (part "C-EUC0603"))
    )
    (comp (ref "LD1")
      (value "GREEN 0603")
      (footprint "eagle-import:LED_1608")
      (fields (field (name "MANUFACTURER") "KINGBRIGHT") (field (name "MANUFACTURERPARTNO") "KP-1608SGC"))
      (libsource (lib "eagle-import") (part "LED-0603_GREEN"))
    )
    (comp (ref "LD2")
      (value "YELLOW 0603")
      (footprint "eagle-import:LED_1608")
      (fields (field (name "MANUFACTURER") "KINGBRIGHT") (field (name "MANUFACTURERPARTNO") "KP-1608SYC"))
      (libsource (lib "eagle-import") (part "LED-0603_YELLOW"))
    )
    (comp (ref "R1")
      (value "4k7")
      (footprint "eagle-import:R0603")
      (libsource (lib "eagle-import") (part "R-EU_R0603"))
    )
    (comp (ref "R2")
      (value "330E")
      (footprint "eagle-import:R0603")
      (libsource (lib "eagle-import") (part "R-EU_R0603"))
    )
    (comp (ref "R3")
      (value "4k7")
      (footprint "eagle-import:R0603")
      (libsource (lib "eagle-import") (part "R-EU_R0603"))
    )
    (comp (ref "R4")
      (value "330E")
      (footprint "eagle-import:R0603")
      (libsource (lib "eagle-import") (part "R-EU_R0603"))
    )
    (comp (ref "R5")
      (value "4k7")
      (footprint "eagle-import:R0603")
      (libsource (lib "eagle-import") (part "R-EU_R0603"))
    )
    (comp (ref "R8")
      (value "47k")
      (footprint "eagle-import:R0603")
      (libsource (lib "eagle-import") (part "R-EU_R0603"))
    )
    (comp (ref "R9")
      (value "47E")
      (footprint "eagle-import:R0603")
      (libsource (lib "eagle-import") (part "R-EU_R0603"))
    )
    (comp (ref "R10")
      (value "47E")
      (footprint "eagle-import:R0603")
      (libsource (lib "eagle-import") (part "R-EU_R0603"))
    )
    (comp (ref "R11")
      (value "47E")
      (footprint "eagle-import:R0603")
      (libsource (lib "eagle-import") (part "R-EU_R0603"))
    )
    (comp (ref "TP19")
      (value "TESTPAD-SMD")
      (footprint "eagle-import:TP-SMD")
      (libsource (lib "eagle-import") (part "TESTPAD-SMD"))
    )
    (comp (ref "TP20")
      (value "TESTPAD-SMD")
      (footprint "eagle-import:TP-SMD")
      (libsource (lib "eagle-import") (part "TESTPAD-SMD"))
    )
    (comp (ref "TP21")
      (value "TESTPAD-SMD")
      (footprint "eagle-import:TP-SMD")
      (libsource (lib "eagle-import") (part "TESTPAD-SMD"))
    )
    (comp (ref "X23")
      (value "debug xilinx")
      (footprint "eagle-import:87832-1420")
      (fields (field (name "MANUFACTURER") "MOLEX") (field (name "MANUFACTURERPARTNO") "87832-1420"))
      (libsource (lib "eagle-import") (part "DEBUG-XILINX"))
    )
    (comp (ref "RA10")
      (value "100E")
      (footprint "eagle-import:CRA06S")
      (libsource (lib "eagle-import") (part "RES-ARRAY--4X100E"))
    )
    (comp (ref "RA11")
      (value "100E")
      (footprint "eagle-import:CRA06S")
      (libsource (lib "eagle-import") (part "RES-ARRAY--4X100E"))
    )
    (comp (ref "RA12")
      (value "100E")
      (footprint "eagle-import:CRA06S")
      (libsource (lib "eagle-import") (part "RES-ARRAY--4X100E"))
    )
    (comp (ref "RA13")
      (value "100E")
      (footprint "eagle-import:CRA06S")
      (libsource (lib "eagle-import") (part "RES-ARRAY--4X100E"))
    )
    (comp (ref "RA14")
      (value "100E")
      (footprint "eagle-import:CRA06S")
      (libsource (lib "eagle-import") (part "RES-ARRAY--4X100E"))
    )
    (comp (ref "RA15")
      (value "100E")
      (footprint "eagle-import:CRA06S")
      (libsource (lib "eagle-import") (part "RES-ARRAY--4X100E"))
    )
    (comp (ref "RA16")
      (value "100E")
      (footprint "eagle-import:CRA06S")
      (libsource (lib "eagle-import") (part "RES-ARRAY--4X100E"))
    )
    (comp (ref "RA17")
      (value "100E")
      (footprint "eagle-import:CRA06S")
      (libsource (lib "eagle-import") (part "RES-ARRAY--4X100E"))
    )
    (comp (ref "RA18")
      (value "100E")
      (footprint "eagle-import:CRA06S")
      (libsource (lib "eagle-import") (part "RES-ARRAY--4X100E"))
    )
    (comp (ref "RA19")
      (value "100E")
      (footprint "eagle-import:CRA06S")
      (libsource (lib "eagle-import") (part "RES-ARRAY--4X100E"))
    )
    (comp (ref "RA20")
      (value "100E")
      (footprint "eagle-import:CRA06S")
      (libsource (lib "eagle-import") (part "RES-ARRAY--4X100E"))
    )
    (comp (ref "RA21")
      (value "100E")
      (footprint "eagle-import:CRA06S")
      (libsource (lib "eagle-import") (part "RES-ARRAY--4X100E"))
    )
    (comp (ref "RA22")
      (value "100E")
      (footprint "eagle-import:CRA06S")
      (libsource (lib "eagle-import") (part "RES-ARRAY--4X100E"))
    )
    (comp (ref "RA23")
      (value "100E")
      (footprint "eagle-import:CRA06S")
      (libsource (lib "eagle-import") (part "RES-ARRAY--4X100E"))
    )
    (comp (ref "X1")
      (value "EDGE 50p")
      (footprint "eagle-import:MB1-150-01-XX-S-XX-SL")
      (fields
        (field (name "MANUFACTURER") "SAMTEC")
        (field (name "MANUFACTURERPARTNO") "MB1-150-01-F-S-02-SL")
      )
      (libsource (lib "eagle-import") (part "EDGE_CONNECT"))
    )
    (comp (ref "X2")
      (value "EDGE 50p")
      (footprint "eagle-import:MB1-150-01-XX-S-XX-SL")
      (fields
        (field (name "MANUFACTURER") "SAMTEC")
        (field (name "MANUFACTURERPARTNO") "MB1-150-01-F-S-02-SL")
      )
      (libsource (lib "eagle-import") (part "EDGE_CONNECT"))
    )
    (comp (ref "X11")
      (value "SOCK2X17")
      (footprint "eagle-import:2X17P-FEMALE")
      (fields (field (name "MANUFACTURER") "WURTH") (field (name "MANUFACTURERPARTNO") "61303421821"))
      (libsource (lib "eagle-import") (part "HDR2X17-F-VERT"))
    )
    (comp (ref "X12")
      (value "SOCK2X17")
      (footprint "eagle-import:2X17P-FEMALE")
      (fields (field (name "MANUFACTURER") "WURTH") (field (name "MANUFACTURERPARTNO") "61303421821"))
      (libsource (lib "eagle-import") (part "HDR2X17-F-VERT"))
    )
    (comp (ref "C49")
      (value "22pF")
      (footprint "eagle-import:C0603")
      (libsource (lib "eagle-import") (part "C-EUC0603"))
    )
    (comp (ref "C50")
      (value "22pF")
      (footprint "eagle-import:C0603")
      (libsource (lib "eagle-import") (part "C-EUC0603"))
    )
    (comp (ref "C51")
      (value "10nF")
      (footprint "eagle-import:C0603")
      (libsource (lib "eagle-import") (part "C-EUC0603"))
    )
    (comp (ref "Q1")
      (value "TXC-7B")
      (footprint "eagle-import:TXC-7B")
      (libsource (lib "eagle-import") (part "TXC-7B"))
    )
    (comp (ref "R12")
      (value "0E")
      (footprint "eagle-import:R0603")
      (libsource (lib "eagle-import") (part "R-EU_R0603"))
    )
    (comp (ref "R13")
      (value "10k")
      (footprint "eagle-import:R0603")
      (libsource (lib "eagle-import") (part "R-EU_R0603"))
    )
    (comp (ref "R14")
      (value "470E")
      (footprint "eagle-import:R0603")
      (libsource (lib "eagle-import") (part "R-EU_R0603"))
    )
    (comp (ref "R15")
      (value "47E")
      (footprint "eagle-import:R0603")
      (libsource (lib "eagle-import") (part "R-EU_R0603"))
    )
    (comp (ref "R16")
      (value "47E")
      (footprint "eagle-import:R0603")
      (libsource (lib "eagle-import") (part "R-EU_R0603"))
    )
    (comp (ref "SV1")
      (value "MA03-1")
      (footprint "eagle-import:MA03-1")
      (libsource (lib "eagle-import") (part "MA03-1"))
    )
    (comp (ref "SW1")
      (value "430181038816")
      (footprint "eagle-import:430181038816")
      (libsource (lib "eagle-import") (part "430181038816"))
    )
    (comp (ref "TP6")
      (value "TESTPAD-SMD")
      (footprint "eagle-import:TP-SMD")
      (libsource (lib "eagle-import") (part "TESTPAD-SMD"))
    )
    (comp (ref "TP7")
      (value "TESTPAD-SMD")
      (footprint "eagle-import:TP-SMD")
      (libsource (lib "eagle-import") (part "TESTPAD-SMD"))
    )
    (comp (ref "TP8")
      (value "TESTPAD-SMD")
      (footprint "eagle-import:TP-SMD")
      (libsource (lib "eagle-import") (part "TESTPAD-SMD"))
    )
    (comp (ref "C17")
      (value "4u7")
      (footprint "eagle-import:C0603")
      (libsource (lib "eagle-import") (part "C-EUC0603"))
    )
    (comp (ref "C18")
      (value "1uF")
      (footprint "eagle-import:C0603")
      (libsource (lib "eagle-import") (part "C-EUC0603"))
    )
    (comp (ref "C43")
      (value "4u7")
      (footprint "eagle-import:C0603")
      (libsource (lib "eagle-import") (part "C-EUC0603"))
    )
    (comp (ref "C44")
      (value "1uF")
      (footprint "eagle-import:C0603")
      (libsource (lib "eagle-import") (part "C-EUC0603"))
    )
    (comp (ref "C56")
      (value "100nF")
      (footprint "eagle-import:C0603")
      (libsource (lib "eagle-import") (part "C-EUC0603"))
    )
    (comp (ref "C57")
      (value "100nF")
      (footprint "eagle-import:C0603")
      (libsource (lib "eagle-import") (part "C-EUC0603"))
    )
    (comp (ref "C901")
      (value "100nF")
      (footprint "eagle-import:C0603")
      (libsource (lib "eagle-import") (part "C-EUC0603"))
    )
    (comp (ref "C902")
      (value "100nF")
      (footprint "eagle-import:C0603")
      (libsource (lib "eagle-import") (part "C-EUC0603"))
    )
    (comp (ref "C903")
      (value "100nF")
      (footprint "eagle-import:C0603")
      (libsource (lib "eagle-import") (part "C-EUC0603"))
    )
    (comp (ref "C904")
      (value "100nF")
      (footprint "eagle-import:C0603")
      (libsource (lib "eagle-import") (part "C-EUC0603"))
    )
    (comp (ref "C905")
      (value "100nF")
      (footprint "eagle-import:C0603")
      (libsource (lib "eagle-import") (part "C-EUC0603"))
    )
    (comp (ref "C906")
      (value "100nF")
      (footprint "eagle-import:C0603")
      (libsource (lib "eagle-import") (part "C-EUC0603"))
    )
    (comp (ref "C907")
      (value "100nF")
      (footprint "eagle-import:C0603")
      (libsource (lib "eagle-import") (part "C-EUC0603"))
    )
    (comp (ref "G901")
      (value "HOLE=3,5/6,6")
      (footprint "eagle-import:HOLE-3,5_6,6")
      (libsource (lib "eagle-import") (part "HOLE=3,5/6,6"))
    )
    (comp (ref "G902")
      (value "HOLE=3,5/6,6")
      (footprint "eagle-import:HOLE-3,5_6,6")
      (libsource (lib "eagle-import") (part "HOLE=3,5/6,6"))
    )
    (comp (ref "G903")
      (value "HOLE=3,5/6,6")
      (footprint "eagle-import:HOLE-3,5_6,6")
      (libsource (lib "eagle-import") (part "HOLE=3,5/6,6"))
    )
    (comp (ref "G904")
      (value "HOLE=3,5/6,6")
      (footprint "eagle-import:HOLE-3,5_6,6")
      (libsource (lib "eagle-import") (part "HOLE=3,5/6,6"))
    )
    (comp (ref "G905")
      (value "HOLE=3,5/6,6")
      (footprint "eagle-import:HOLE-3,5_6,6")
      (libsource (lib "eagle-import") (part "HOLE=3,5/6,6"))
    )
    (comp (ref "G906")
      (value "HOLE=3,5/6,6")
      (footprint "eagle-import:HOLE-3,5_6,6")
      (libsource (lib "eagle-import") (part "HOLE=3,5/6,6"))
    )
    (comp (ref "G907")
      (value "HOLE=3,5/6,6")
      (footprint "eagle-import:HOLE-3,5_6,6")
      (libsource (lib "eagle-import") (part "HOLE=3,5/6,6"))
    )
    (comp (ref "J_1.2")
      (value "HDR1X2")
      (footprint "eagle-import:1X2")
      (fields (field (name "MANUFACTURER") "Wurth") (field (name "MANUFACTURERPARTNO") "61300211121"))
      (libsource (lib "eagle-import") (part "HDR1X2-M"))
    )
    (comp (ref "J_3.3")
      (value "HDR1X2")
      (footprint "eagle-import:1X2")
      (fields (field (name "MANUFACTURER") "Wurth") (field (name "MANUFACTURERPARTNO") "61300211121"))
      (libsource (lib "eagle-import") (part "HDR1X2-M"))
    )
    (comp (ref "L5")
      (value "26Z@100MHz")
      (footprint "eagle-import:L1608")
      (fields (field (name "MANUFACTURER") "Murata") (field (name "MANUFACTURERPARTNO") "BLM18KG260TN1D"))
      (libsource (lib "eagle-import") (part "BEAD_[0603]26Z@100MHZ"))
    )
    (comp (ref "R901")
      (value "1M")
      (footprint "eagle-import:R0603")
      (libsource (lib "eagle-import") (part "R-EU_R0603"))
    )
    (comp (ref "R902")
      (value "1M")
      (footprint "eagle-import:R0603")
      (libsource (lib "eagle-import") (part "R-EU_R0603"))
    )
    (comp (ref "R903")
      (value "1M")
      (footprint "eagle-import:R0603")
      (libsource (lib "eagle-import") (part "R-EU_R0603"))
    )
    (comp (ref "R904")
      (value "1M")
      (footprint "eagle-import:R0603")
      (libsource (lib "eagle-import") (part "R-EU_R0603"))
    )
    (comp (ref "R905")
      (value "1M")
      (footprint "eagle-import:R0603")
      (libsource (lib "eagle-import") (part "R-EU_R0603"))
    )
    (comp (ref "R906")
      (value "1M")
      (footprint "eagle-import:R0603")
      (libsource (lib "eagle-import") (part "R-EU_R0603"))
    )
    (comp (ref "R907")
      (value "1M")
      (footprint "eagle-import:R0603")
      (libsource (lib "eagle-import") (part "R-EU_R0603"))
    )
    (comp (ref "SW2")
      (value "C&K_1000")
      (footprint "eagle-import:1XXX-MX-XX-C")
      (fields
        (field (name "MANUFACTURER") "C&K Components")
        (field (name "MANUFACTURERPARTNO") "1101M2S3CGE2")
      )
      (libsource (lib "eagle-import") (part "C&K_1000"))
    )
    (comp (ref "TP1")
      (value "TESTPAD-SMD")
      (footprint "eagle-import:TP-SMD")
      (libsource (lib "eagle-import") (part "TESTPAD-SMD"))
    )
    (comp (ref "TP2")
      (value "TESTPAD-SMD")
      (footprint "eagle-import:TP-SMD")
      (libsource (lib "eagle-import") (part "TESTPAD-SMD"))
    )
    (comp (ref "TP3")
      (value "TESTPAD-SMD")
      (footprint "eagle-import:TP-SMD")
      (libsource (lib "eagle-import") (part "TESTPAD-SMD"))
    )
    (comp (ref "TP4")
      (value "TESTPAD-SMD")
      (footprint "eagle-import:TP-SMD")
      (libsource (lib "eagle-import") (part "TESTPAD-SMD"))
    )
    (comp (ref "TP5")
      (value "TESTPAD-SMD")
      (footprint "eagle-import:TP-SMD")
      (libsource (lib "eagle-import") (part "TESTPAD-SMD"))
    )
    (comp (ref "U2")
      (value "MCP1826S 3V3")
      (footprint "eagle-import:SOT-223")
      (fields
        (field (name "MANUFACTURER") "Microchip")
        (field (name "MANUFACTURERPARTNO") "MCP1826S-3302E/DB")
      )
      (libsource (lib "eagle-import") (part "MCP1826S-3V3"))
    )
    (comp (ref "U6")
      (value "MCP1826S 1V2")
      (footprint "eagle-import:SOT-223")
      (fields
        (field (name "MANUFACTURER") "Microchip")
        (field (name "MANUFACTURERPARTNO") "MCP1826S-1202E/DB")
      )
      (libsource (lib "eagle-import") (part "MCP1826S-1V2"))
    )
    (comp (ref "X5")
      (value "MicroMatch 24")
      (footprint "eagle-import:MICROMATCH-24-MALE")
      (fields (field (name "MANUFACTURER") "WURTH") (field (name "MANUFACTURERPARTNO") "690357102472"))
      (libsource (lib "eagle-import") (part "WR-MM_MALEP24"))
    )
    (comp (ref "RA24")
      (value "100E")
      (footprint "eagle-import:CRA06S")
      (libsource (lib "eagle-import") (part "RES-ARRAY--4X100E"))
    )
    (comp (ref "RA25")
      (value "100E")
      (footprint "eagle-import:CRA06S")
      (libsource (lib "eagle-import") (part "RES-ARRAY--4X100E"))
    )
    (comp (ref "RA26")
      (value "100E")
      (footprint "eagle-import:CRA06S")
      (libsource (lib "eagle-import") (part "RES-ARRAY--4X100E"))
    )
    (comp (ref "RA27")
      (value "100E")
      (footprint "eagle-import:CRA06S")
      (libsource (lib "eagle-import") (part "RES-ARRAY--4X100E"))
    )
    (comp (ref "RA28")
      (value "100E")
      (footprint "eagle-import:CRA06S")
      (libsource (lib "eagle-import") (part "RES-ARRAY--4X100E"))
    )
    (comp (ref "RA29")
      (value "100E")
      (footprint "eagle-import:CRA06S")
      (libsource (lib "eagle-import") (part "RES-ARRAY--4X100E"))
    )
    (comp (ref "RA30")
      (value "100E")
      (footprint "eagle-import:CRA06S")
      (libsource (lib "eagle-import") (part "RES-ARRAY--4X100E"))
    )
    (comp (ref "RA31")
      (value "100E")
      (footprint "eagle-import:CRA06S")
      (libsource (lib "eagle-import") (part "RES-ARRAY--4X100E"))
    )
    (comp (ref "RA32")
      (value "100E")
      (footprint "eagle-import:CRA06S")
      (libsource (lib "eagle-import") (part "RES-ARRAY--4X100E"))
    )
    (comp (ref "RA33")
      (value "100E")
      (footprint "eagle-import:CRA06S")
      (libsource (lib "eagle-import") (part "RES-ARRAY--4X100E"))
    )
    (comp (ref "RA34")
      (value "100E")
      (footprint "eagle-import:CRA06S")
      (libsource (lib "eagle-import") (part "RES-ARRAY--4X100E"))
    )
    (comp (ref "RA35")
      (value "100E")
      (footprint "eagle-import:CRA06S")
      (libsource (lib "eagle-import") (part "RES-ARRAY--4X100E"))
    )
    (comp (ref "RA36")
      (value "100E")
      (footprint "eagle-import:CRA06S")
      (libsource (lib "eagle-import") (part "RES-ARRAY--4X100E"))
    )
    (comp (ref "RA37")
      (value "100E")
      (footprint "eagle-import:CRA06S")
      (libsource (lib "eagle-import") (part "RES-ARRAY--4X100E"))
    )
    (comp (ref "X3")
      (value "EDGE 50p")
      (footprint "eagle-import:MB1-150-01-XX-S-XX-SL")
      (fields
        (field (name "MANUFACTURER") "SAMTEC")
        (field (name "MANUFACTURERPARTNO") "MB1-150-01-F-S-02-SL")
      )
      (libsource (lib "eagle-import") (part "EDGE_CONNECT"))
    )
    (comp (ref "X4")
      (value "EDGE 50p")
      (footprint "eagle-import:MB1-150-01-XX-S-XX-SL")
      (fields
        (field (name "MANUFACTURER") "SAMTEC")
        (field (name "MANUFACTURERPARTNO") "MB1-150-01-F-S-02-SL")
      )
      (libsource (lib "eagle-import") (part "EDGE_CONNECT"))
    )
    (comp (ref "X7")
      (value "SOCK2X17")
      (footprint "eagle-import:2X17P-FEMALE")
      (fields (field (name "MANUFACTURER") "WURTH") (field (name "MANUFACTURERPARTNO") "61303421821"))
      (libsource (lib "eagle-import") (part "HDR2X17-F-VERT"))
    )
    (comp (ref "X13")
      (value "SOCK2X17")
      (footprint "eagle-import:2X17P-FEMALE")
      (fields (field (name "MANUFACTURER") "WURTH") (field (name "MANUFACTURERPARTNO") "61303421821"))
      (libsource (lib "eagle-import") (part "HDR2X17-F-VERT"))
    )
  )
  (nets
    (net (code "1") (name "+1.2V") (class "Default")
      (node (ref "C19") (pin "1") (pinfunction "1_1") (pintype "passive"))
      (node (ref "C20") (pin "1") (pinfunction "1_1") (pintype "passive"))
      (node (ref "C21") (pin "1") (pinfunction "1_1") (pintype "passive"))
      (node (ref "C22") (pin "1") (pinfunction "1_1") (pintype "passive"))
      (node (ref "J_1.2") (pin "1") (pinfunction "1_1") (pintype "passive"))
      (node (ref "U4") (pin "128") (pinfunction "VCCINT_128") (pintype "power_in"))
      (node (ref "U4") (pin "19") (pinfunction "VCCINT_19") (pintype "power_in"))
      (node (ref "U4") (pin "28") (pinfunction "VCCINT_28") (pintype "power_in"))
      (node (ref "U4") (pin "52") (pinfunction "VCCINT_52") (pintype "power_in"))
      (node (ref "U4") (pin "89") (pinfunction "VCCINT_89") (pintype "power_in"))
    )
    (net (code "2") (name "+3.3V") (class "Default")
      (node (ref "C1") (pin "1") (pinfunction "1_1") (pintype "passive"))
      (node (ref "C10") (pin "1") (pinfunction "1_1") (pintype "passive"))
      (node (ref "C11") (pin "1") (pinfunction "1_1") (pintype "passive"))
      (node (ref "C12") (pin "1") (pinfunction "1_1") (pintype "passive"))
      (node (ref "C13") (pin "1") (pinfunction "1_1") (pintype "passive"))
      (node (ref "C16") (pin "1") (pinfunction "1_1") (pintype "passive"))
      (node (ref "C2") (pin "1") (pinfunction "1_1") (pintype "passive"))
      (node (ref "C23") (pin "1") (pinfunction "1_1") (pintype "passive"))
      (node (ref "C24") (pin "1") (pinfunction "1_1") (pintype "passive"))
      (node (ref "C25") (pin "1") (pinfunction "1_1") (pintype "passive"))
      (node (ref "C26") (pin "1") (pinfunction "1_1") (pintype "passive"))
      (node (ref "C27") (pin "1") (pinfunction "1_1") (pintype "passive"))
      (node (ref "C28") (pin "1") (pinfunction "1_1") (pintype "passive"))
      (node (ref "C29") (pin "1") (pinfunction "1_1") (pintype "passive"))
      (node (ref "C3") (pin "1") (pinfunction "1_1") (pintype "passive"))
      (node (ref "C30") (pin "1") (pinfunction "1_1") (pintype "passive"))
      (node (ref "C31") (pin "1") (pinfunction "1_1") (pintype "passive"))
      (node (ref "C32") (pin "1") (pinfunction "1_1") (pintype "passive"))
      (node (ref "C33") (pin "1") (pinfunction "1_1") (pintype "passive"))
      (node (ref "C34") (pin "1") (pinfunction "1_1") (pintype "passive"))
      (node (ref "C35") (pin "1") (pinfunction "1_1") (pintype "passive"))
      (node (ref "C36") (pin "1") (pinfunction "1_1") (pintype "passive"))
      (node (ref "C37") (pin "1") (pinfunction "1_1") (pintype "passive"))
      (node (ref "C38") (pin "1") (pinfunction "1_1") (pintype "passive"))
      (node (ref "C39") (pin "1") (pinfunction "1_1") (pintype "passive"))
      (node (ref "C4") (pin "1") (pinfunction "1_1") (pintype "passive"))
      (node (ref "C40") (pin "1") (pinfunction "1_1") (pintype "passive"))
      (node (ref "C41") (pin "1") (pinfunction "1_1") (pintype "passive"))
      (node (ref "C42") (pin "1") (pinfunction "1_1") (pintype "passive"))
      (node (ref "C5") (pin "1") (pinfunction "1_1") (pintype "passive"))
      (node (ref "C58") (pin "1") (pinfunction "1_1") (pintype "passive"))
      (node (ref "C59") (pin "1") (pinfunction "1_1") (pintype "passive"))
      (node (ref "C6") (pin "1") (pinfunction "1_1") (pintype "passive"))
      (node (ref "C61") (pin "1") (pinfunction "1_1") (pintype "passive"))
      (node (ref "C62") (pin "1") (pinfunction "1_1") (pintype "passive"))
      (node (ref "C63") (pin "1") (pinfunction "1_1") (pintype "passive"))
      (node (ref "C64") (pin "1") (pinfunction "1_1") (pintype "passive"))
      (node (ref "C7") (pin "1") (pinfunction "1_1") (pintype "passive"))
      (node (ref "C8") (pin "1") (pinfunction "1_1") (pintype "passive"))
      (node (ref "C9") (pin "1") (pinfunction "1_1") (pintype "passive"))
      (node (ref "J_3.3") (pin "1") (pinfunction "1_1") (pintype "passive"))
      (node (ref "L2") (pin "2") (pinfunction "F_2") (pintype "passive"))
      (node (ref "Q2") (pin "4") (pinfunction "VCC_4") (pintype "power_in"))
      (node (ref "R13") (pin "2") (pinfunction "2_2") (pintype "passive"))
      (node (ref "R18") (pin "2") (pinfunction "2_2") (pintype "passive"))
      (node (ref "R2") (pin "2") (pinfunction "2_2") (pintype "passive"))
      (node (ref "R23") (pin "2") (pinfunction "2_2") (pintype "passive"))
      (node (ref "R24") (pin "2") (pinfunction "2_2") (pintype "passive"))
      (node (ref "R25") (pin "2") (pinfunction "2_2") (pintype "passive"))
      (node (ref "R26") (pin "2") (pinfunction "2_2") (pintype "passive"))
      (node (ref "R27") (pin "2") (pinfunction "2_2") (pintype "passive"))
      (node (ref "R28") (pin "2") (pinfunction "2_2") (pintype "passive"))
      (node (ref "R3") (pin "2") (pinfunction "2_2") (pintype "passive"))
      (node (ref "R4") (pin "2") (pinfunction "2_2") (pintype "passive"))
      (node (ref "R5") (pin "2") (pinfunction "2_2") (pintype "passive"))
      (node (ref "R6") (pin "2") (pinfunction "2_2") (pintype "passive"))
      (node (ref "R8") (pin "2") (pinfunction "2_2") (pintype "passive"))
      (node (ref "SV2") (pin "1") (pinfunction "1_1") (pintype "passive"))
      (node (ref "U1") (pin "101") (pinfunction "VDD_101") (pintype "power_in"))
      (node (ref "U1") (pin "113") (pinfunction "VDD_113") (pintype "power_in"))
      (node (ref "U1") (pin "122") (pinfunction "VDD_122") (pintype "power_in"))
      (node (ref "U1") (pin "16") (pinfunction "VDD_16") (pintype "power_in"))
      (node (ref "U1") (pin "26") (pinfunction "VDD_26") (pintype "power_in"))
      (node (ref "U1") (pin "28") (pinfunction "VDD_28") (pintype "power_in"))
      (node (ref "U1") (pin "39") (pinfunction "VDD_39") (pintype "power_in"))
      (node (ref "U1") (pin "47") (pinfunction "VDD_47") (pintype "power_in"))
      (node (ref "U1") (pin "51") (pinfunction "VDD_51") (pintype "power_in"))
      (node (ref "U1") (pin "52") (pinfunction "VDD_52") (pintype "power_in"))
      (node (ref "U1") (pin "68") (pinfunction "VBAT_68") (pintype "power_in"))
      (node (ref "U1") (pin "69") (pinfunction "VDD_69") (pintype "power_in"))
      (node (ref "U1") (pin "7") (pinfunction "VDD_7") (pintype "power_in"))
      (node (ref "U1") (pin "79") (pinfunction "VDD_79") (pintype "power_in"))
      (node (ref "U1") (pin "90") (pinfunction "VDD_90") (pintype "power_in"))
      (node (ref "U4") (pin "103") (pinfunction "VCCO_1_103") (pintype "power_in"))
      (node (ref "U4") (pin "122") (pinfunction "VCCO_0_122") (pintype "power_in"))
      (node (ref "U4") (pin "125") (pinfunction "VCCO_0_125") (pintype "power_in"))
      (node (ref "U4") (pin "129") (pinfunction "VCCAUX_129") (pintype "power_in"))
      (node (ref "U4") (pin "135") (pinfunction "VCCO_0_135") (pintype "power_in"))
      (node (ref "U4") (pin "18") (pinfunction "VCCO_3_18") (pintype "power_in"))
      (node (ref "U4") (pin "20") (pinfunction "VCCAUX_20") (pintype "power_in"))
      (node (ref "U4") (pin "31") (pinfunction "VCCO_3_31") (pintype "power_in"))
      (node (ref "U4") (pin "36") (pinfunction "VCCAUX_36") (pintype "power_in"))
      (node (ref "U4") (pin "4") (pinfunction "VCCO_3_4") (pintype "power_in"))
      (node (ref "U4") (pin "42") (pinfunction "VCCO_2_42") (pintype "power_in"))
      (node (ref "U4") (pin "53") (pinfunction "VCCAUX_53") (pintype "power_in"))
      (node (ref "U4") (pin "63") (pinfunction "VCCO_2_63") (pintype "power_in"))
      (node (ref "U4") (pin "76") (pinfunction "VCCO_1_76") (pintype "power_in"))
      (node (ref "U4") (pin "86") (pinfunction "VCCO_1_86") (pintype "power_in"))
      (node (ref "U4") (pin "90") (pinfunction "VCCAUX_90") (pintype "power_in"))
      (node (ref "U5") (pin "7") (pinfunction "~{HOLD}_7") (pintype "bidirectional"))
      (node (ref "U5") (pin "8") (pinfunction "VCC_8") (pintype "power_in"))
      (node (ref "X23") (pin "2") (pinfunction "2_2") (pintype "passive"))
      (node (ref "X24") (pin "1") (pinfunction "1_1") (pintype "passive"))
      (node (ref "X8") (pin "2") (pinfunction "TCT_2") (pintype "bidirectional"))
      (node (ref "X8") (pin "5") (pinfunction "RCT_5") (pintype "bidirectional"))
    )
    (net (code "3") (name "+5V") (class "Default")
      (node (ref "C17") (pin "1") (pinfunction "1_1") (pintype "passive"))
      (node (ref "C43") (pin "1") (pinfunction "1_1") (pintype "passive"))
      (node (ref "C54") (pin "1") (pinfunction "1_1") (pintype "passive"))
      (node (ref "C55") (pin "1") (pinfunction "1_1") (pintype "passive"))
      (node (ref "C56") (pin "1") (pinfunction "1_1") (pintype "passive"))
      (node (ref "D2") (pin "1") (pinfunction "A_1") (pintype "bidirectional"))
      (node (ref "SW2") (pin "2") (pinfunction "2_2") (pintype "bidirectional"))
      (node (ref "TP1") (pin "1") (pinfunction "1_1") (pintype "passive"))
      (node (ref "U2") (pin "1") (pinfunction "V_IN_1") (pintype "input"))
      (node (ref "U3") (pin "3") (pinfunction "EN_3") (pintype "input"))
      (node (ref "U3") (pin "4") (pinfunction "VIN_4") (pintype "power_in"))
      (node (ref "U6") (pin "1") (pinfunction "V_IN_1") (pintype "input"))
      (node (ref "X1") (pin "1") (pinfunction "1_1") (pintype "bidirectional"))
      (node (ref "X1") (pin "2") (pinfunction "2_2") (pintype "bidirectional"))
      (node (ref "X1") (pin "3") (pinfunction "3_3") (pintype "bidirectional"))
      (node (ref "X11") (pin "2") (pinfunction "2_2") (pintype "passive"))
      (node (ref "X12") (pin "2") (pinfunction "2_2") (pintype "passive"))
      (node (ref "X13") (pin "2") (pinfunction "2_2") (pintype "passive"))
      (node (ref "X2") (pin "1") (pinfunction "1_1") (pintype "bidirectional"))
      (node (ref "X2") (pin "2") (pinfunction "2_2") (pintype "bidirectional"))
      (node (ref "X2") (pin "3") (pinfunction "3_3") (pintype "bidirectional"))
      (node (ref "X3") (pin "1") (pinfunction "1_1") (pintype "bidirectional"))
      (node (ref "X3") (pin "2") (pinfunction "2_2") (pintype "bidirectional"))
      (node (ref "X3") (pin "3") (pinfunction "3_3") (pintype "bidirectional"))
      (node (ref "X4") (pin "1") (pinfunction "1_1") (pintype "bidirectional"))
      (node (ref "X4") (pin "2") (pinfunction "2_2") (pintype "bidirectional"))
      (node (ref "X4") (pin "3") (pinfunction "3_3") (pintype "bidirectional"))
      (node (ref "X7") (pin "2") (pinfunction "2_2") (pintype "passive"))
    )
    (net (code "4") (name "5V_USB") (class "Default")
      (node (ref "L4") (pin "1") (pinfunction "E_1") (pintype "passive"))
      (node (ref "R29") (pin "2") (pinfunction "2_2") (pintype "passive"))
      (node (ref "SW2") (pin "1") (pinfunction "1_1") (pintype "bidirectional"))
    )
    (net (code "5") (name "DONE") (class "Default")
      (node (ref "LD1") (pin "C") (pinfunction "K_C") (pintype "tri_state"))
      (node (ref "R5") (pin "1") (pinfunction "1_1") (pintype "passive"))
      (node (ref "TP21") (pin "1") (pinfunction "1_1") (pintype "passive"))
      (node (ref "U1") (pin "32") (pinfunction "PH3_32") (pintype "bidirectional"))
      (node (ref "U4") (pin "71") (pinfunction "DONE_71") (pintype "output"))
    )
    (net (code "6") (name "D_N") (class "Default")
      (node (ref "D1") (pin "4") (pinfunction "2_4") (pintype "passive"))
      (node (ref "L3") (pin "3") (pinfunction "2_3") (pintype "passive"))
      (node (ref "X6") (pin "2") (pinfunction "D_N_2") (pintype "passive"))
    )
    (net (code "7") (name "D_P") (class "Default")
      (node (ref "D1") (pin "3") (pinfunction "1_3") (pintype "passive"))
      (node (ref "L3") (pin "2") (pinfunction "3_2") (pintype "passive"))
      (node (ref "X6") (pin "3") (pinfunction "D_P_3") (pintype "passive"))
    )
    (net (code "8") (name "EPI0S0") (class "Default")
      (node (ref "RA1") (pin "4B") (pinfunction "4B_4B") (pintype "passive"))
      (node (ref "U1") (pin "18") (pinfunction "PK0_18") (pintype "bidirectional"))
    )
    (net (code "9") (name "EPI0S1") (class "Default")
      (node (ref "RA2") (pin "1B") (pinfunction "1B_1B") (pintype "passive"))
      (node (ref "U1") (pin "19") (pinfunction "PK1_19") (pintype "bidirectional"))
    )
    (net (code "10") (name "EPI0S2") (class "Default")
      (node (ref "RA2") (pin "2B") (pinfunction "2B_2B") (pintype "passive"))
      (node (ref "U1") (pin "20") (pinfunction "PK2_20") (pintype "bidirectional"))
    )
    (net (code "11") (name "EPI0S3") (class "Default")
      (node (ref "RA2") (pin "3B") (pinfunction "3B_3B") (pintype "passive"))
      (node (ref "U1") (pin "21") (pinfunction "PK3_21") (pintype "bidirectional"))
    )
    (net (code "12") (name "EPI0S4") (class "Default")
      (node (ref "RA2") (pin "4B") (pinfunction "4B_4B") (pintype "passive"))
      (node (ref "U1") (pin "22") (pinfunction "PC7_22") (pintype "bidirectional"))
    )
    (net (code "13") (name "EPI0S5") (class "Default")
      (node (ref "RA3") (pin "1B") (pinfunction "1B_1B") (pintype "passive"))
      (node (ref "U1") (pin "23") (pinfunction "PC6_23") (pintype "bidirectional"))
    )
    (net (code "14") (name "EPI0S6") (class "Default")
      (node (ref "RA3") (pin "2B") (pinfunction "2B_2B") (pintype "passive"))
      (node (ref "U1") (pin "24") (pinfunction "PC5_24") (pintype "bidirectional"))
    )
    (net (code "15") (name "EPI0S7") (class "Default")
      (node (ref "RA3") (pin "3B") (pinfunction "3B_3B") (pintype "passive"))
      (node (ref "U1") (pin "25") (pinfunction "PC4_25") (pintype "bidirectional"))
    )
    (net (code "16") (name "EPI0S8") (class "Default")
      (node (ref "RA4") (pin "1B") (pinfunction "1B_1B") (pintype "passive"))
      (node (ref "U1") (pin "40") (pinfunction "PA6_40") (pintype "bidirectional"))
    )
    (net (code "17") (name "EPI0S9") (class "Default")
      (node (ref "RA4") (pin "2B") (pinfunction "2B_2B") (pintype "passive"))
      (node (ref "U1") (pin "41") (pinfunction "PA7_41") (pintype "bidirectional"))
    )
    (net (code "18") (name "EPI0S10") (class "Default")
      (node (ref "RA4") (pin "4B") (pinfunction "4B_4B") (pintype "passive"))
      (node (ref "U1") (pin "50") (pinfunction "PG1_50") (pintype "bidirectional"))
    )
    (net (code "19") (name "EPI0S11") (class "Default")
      (node (ref "RA4") (pin "3B") (pinfunction "3B_3B") (pintype "passive"))
      (node (ref "U1") (pin "49") (pinfunction "PG0_49") (pintype "bidirectional"))
    )
    (net (code "20") (name "EPI0S12") (class "Default")
      (node (ref "RA5") (pin "4B") (pinfunction "4B_4B") (pintype "passive"))
      (node (ref "U1") (pin "75") (pinfunction "PM3_75") (pintype "bidirectional"))
    )
    (net (code "21") (name "EPI0S13") (class "Default")
      (node (ref "RA6") (pin "1B") (pinfunction "1B_1B") (pintype "passive"))
      (node (ref "U1") (pin "76") (pinfunction "PM2_76") (pintype "bidirectional"))
    )
    (net (code "22") (name "EPI0S14") (class "Default")
      (node (ref "RA6") (pin "2B") (pinfunction "2B_2B") (pintype "passive"))
      (node (ref "U1") (pin "77") (pinfunction "PM1_77") (pintype "bidirectional"))
    )
    (net (code "23") (name "EPI0S15") (class "Default")
      (node (ref "RA6") (pin "3B") (pinfunction "3B_3B") (pintype "passive"))
      (node (ref "U1") (pin "78") (pinfunction "PM0_78") (pintype "bidirectional"))
    )
    (net (code "24") (name "EPI0S16") (class "Default")
      (node (ref "RA6") (pin "4B") (pinfunction "4B_4B") (pintype "passive"))
      (node (ref "U1") (pin "81") (pinfunction "PL0_81") (pintype "bidirectional"))
    )
    (net (code "25") (name "EPI0S17") (class "Default")
      (node (ref "RA7") (pin "1B") (pinfunction "1B_1B") (pintype "passive"))
      (node (ref "U1") (pin "82") (pinfunction "PL1_82") (pintype "bidirectional"))
    )
    (net (code "26") (name "EPI0S18") (class "Default")
      (node (ref "RA7") (pin "2B") (pinfunction "2B_2B") (pintype "passive"))
      (node (ref "U1") (pin "83") (pinfunction "PL2_83") (pintype "bidirectional"))
    )
    (net (code "27") (name "EPI0S19") (class "Default")
      (node (ref "RA7") (pin "3B") (pinfunction "3B_3B") (pintype "passive"))
      (node (ref "U1") (pin "84") (pinfunction "PL3_84") (pintype "bidirectional"))
    )
    (net (code "28") (name "EPI0S20") (class "Default")
      (node (ref "RA1") (pin "1B") (pinfunction "1B_1B") (pintype "passive"))
      (node (ref "U1") (pin "5") (pinfunction "PQ0_5") (pintype "bidirectional"))
    )
    (net (code "29") (name "EPI0S21") (class "Default")
      (node (ref "RA1") (pin "2B") (pinfunction "2B_2B") (pintype "passive"))
      (node (ref "U1") (pin "6") (pinfunction "PQ1_6") (pintype "bidirectional"))
    )
    (net (code "30") (name "EPI0S22") (class "Default")
      (node (ref "RA1") (pin "3B") (pinfunction "3B_3B") (pintype "passive"))
      (node (ref "U1") (pin "11") (pinfunction "PQ2_11") (pintype "bidirectional"))
    )
    (net (code "31") (name "EPI0S23") (class "Default")
      (node (ref "RA3") (pin "4B") (pinfunction "4B_4B") (pintype "passive"))
      (node (ref "U1") (pin "27") (pinfunction "PQ3_27") (pintype "bidirectional"))
    )
    (net (code "32") (name "EPI0S24") (class "Default")
      (node (ref "RA5") (pin "1B") (pinfunction "1B_1B") (pintype "passive"))
      (node (ref "U1") (pin "60") (pinfunction "PK7_60") (pintype "bidirectional"))
    )
    (net (code "33") (name "EPI0S25") (class "Default")
      (node (ref "RA5") (pin "2B") (pinfunction "2B_2B") (pintype "passive"))
      (node (ref "U1") (pin "61") (pinfunction "PK6_61") (pintype "bidirectional"))
    )
    (net (code "34") (name "EPI0S26") (class "Default")
      (node (ref "RA7") (pin "4B") (pinfunction "4B_4B") (pintype "passive"))
      (node (ref "U1") (pin "85") (pinfunction "PL4_85") (pintype "bidirectional"))
    )
    (net (code "35") (name "EPI0S27") (class "Default")
      (node (ref "RA8") (pin "1B") (pinfunction "1B_1B") (pintype "passive"))
      (node (ref "U1") (pin "91") (pinfunction "PB2_91") (pintype "bidirectional"))
    )
    (net (code "36") (name "EPI0S28") (class "Default")
      (node (ref "RA8") (pin "2B") (pinfunction "2B_2B") (pintype "passive"))
      (node (ref "U1") (pin "92") (pinfunction "PB3_92") (pintype "bidirectional"))
    )
    (net (code "37") (name "EPI0S29") (class "Default")
      (node (ref "RA8") (pin "3B") (pinfunction "3B_3B") (pintype "passive"))
      (node (ref "U1") (pin "103") (pinfunction "PP2_103") (pintype "bidirectional"))
    )
    (net (code "38") (name "EPI0S30") (class "Default")
      (node (ref "RA8") (pin "4B") (pinfunction "4B_4B") (pintype "passive"))
      (node (ref "U1") (pin "104") (pinfunction "PP3_104") (pintype "bidirectional"))
    )
    (net (code "39") (name "EPI0S31") (class "Default")
      (node (ref "RA5") (pin "3B") (pinfunction "3B_3B") (pintype "passive"))
      (node (ref "U1") (pin "62") (pinfunction "PK5_62") (pintype "bidirectional"))
    )
    (net (code "40") (name "ETH_PAIR0_N") (class "Default")
      (node (ref "R25") (pin "1") (pinfunction "1_1") (pintype "passive"))
      (node (ref "U1") (pin "56") (pinfunction "EN0TXON_56") (pintype "bidirectional"))
      (node (ref "X8") (pin "3") (pinfunction "TD-_3") (pintype "bidirectional"))
    )
    (net (code "41") (name "ETH_PAIR0_P") (class "Default")
      (node (ref "R26") (pin "1") (pinfunction "1_1") (pintype "passive"))
      (node (ref "U1") (pin "57") (pinfunction "EN0TXOP_57") (pintype "bidirectional"))
      (node (ref "X8") (pin "1") (pinfunction "TD+_1") (pintype "bidirectional"))
    )
    (net (code "42") (name "ETH_PAIR1_N") (class "Default")
      (node (ref "R23") (pin "1") (pinfunction "1_1") (pintype "passive"))
      (node (ref "U1") (pin "53") (pinfunction "EN0RXIN_53") (pintype "bidirectional"))
      (node (ref "X8") (pin "6") (pinfunction "RD-_6") (pintype "bidirectional"))
    )
    (net (code "43") (name "ETH_PAIR1_P") (class "Default")
      (node (ref "R24") (pin "1") (pinfunction "1_1") (pintype "passive"))
      (node (ref "U1") (pin "54") (pinfunction "EN0RXIP_54") (pintype "bidirectional"))
      (node (ref "X8") (pin "4") (pinfunction "RD+_4") (pintype "bidirectional"))
    )
    (net (code "44") (name "FPGA_III_1") (class "Default")
      (node (ref "RA24") (pin "1B") (pinfunction "1B_1B") (pintype "passive"))
      (node (ref "U4") (pin "35") (pinfunction "IO_L1P_35") (pintype "bidirectional"))
    )
    (net (code "45") (name "FPGA_III_2") (class "Default")
      (node (ref "RA24") (pin "2B") (pinfunction "2B_2B") (pintype "passive"))
      (node (ref "U4") (pin "34") (pinfunction "IO_L1N_VREF_34") (pintype "bidirectional"))
    )
    (net (code "46") (name "FPGA_III_3") (class "Default")
      (node (ref "RA24") (pin "3B") (pinfunction "3B_3B") (pintype "passive"))
      (node (ref "U4") (pin "33") (pinfunction "IO_L2P_33") (pintype "bidirectional"))
    )
    (net (code "47") (name "FPGA_III_4") (class "Default")
      (node (ref "RA24") (pin "4B") (pinfunction "4B_4B") (pintype "passive"))
      (node (ref "U4") (pin "32") (pinfunction "IO_L2N_32") (pintype "bidirectional"))
    )
    (net (code "48") (name "FPGA_III_5") (class "Default")
      (node (ref "RA25") (pin "1B") (pinfunction "1B_1B") (pintype "passive"))
      (node (ref "U4") (pin "30") (pinfunction "IO_L36P_30") (pintype "bidirectional"))
    )
    (net (code "49") (name "FPGA_III_6") (class "Default")
      (node (ref "RA25") (pin "2B") (pinfunction "2B_2B") (pintype "passive"))
      (node (ref "U4") (pin "29") (pinfunction "IO_L36N_29") (pintype "bidirectional"))
    )
    (net (code "50") (name "FPGA_III_7") (class "Default")
      (node (ref "RA25") (pin "3B") (pinfunction "3B_3B") (pintype "passive"))
      (node (ref "U4") (pin "27") (pinfunction "IO_L37P_27") (pintype "bidirectional"))
    )
    (net (code "51") (name "FPGA_III_8") (class "Default")
      (node (ref "RA25") (pin "4B") (pinfunction "4B_4B") (pintype "passive"))
      (node (ref "U4") (pin "26") (pinfunction "IO_L37N_26") (pintype "bidirectional"))
    )
    (net (code "52") (name "FPGA_III_9") (class "Default")
      (node (ref "RA26") (pin "1B") (pinfunction "1B_1B") (pintype "passive"))
      (node (ref "U4") (pin "24") (pinfunction "IO_L41P_GCLK27_24") (pintype "bidirectional"))
    )
    (net (code "53") (name "FPGA_III_10") (class "Default")
      (node (ref "RA26") (pin "2B") (pinfunction "2B_2B") (pintype "passive"))
      (node (ref "U4") (pin "23") (pinfunction "IO_L41N_GCLK26_23") (pintype "bidirectional"))
    )
    (net (code "54") (name "FPGA_III_11") (class "Default")
      (node (ref "RA26") (pin "3B") (pinfunction "3B_3B") (pintype "passive"))
      (node (ref "U4") (pin "22") (pinfunction "IO_L42P_GCLK25_TRDY2_22") (pintype "bidirectional"))
    )
    (net (code "55") (name "FPGA_III_12") (class "Default")
      (node (ref "RA26") (pin "4B") (pinfunction "4B_4B") (pintype "passive"))
      (node (ref "U4") (pin "21") (pinfunction "IO_L42N_GCLK24_21") (pintype "bidirectional"))
    )
    (net (code "56") (name "FPGA_III_13") (class "Default")
      (node (ref "RA27") (pin "1B") (pinfunction "1B_1B") (pintype "passive"))
      (node (ref "U4") (pin "17") (pinfunction "IO_L43P_GCLK23_17") (pintype "bidirectional"))
    )
    (net (code "57") (name "FPGA_III_14") (class "Default")
      (node (ref "RA27") (pin "2B") (pinfunction "2B_2B") (pintype "passive"))
      (node (ref "U4") (pin "16") (pinfunction "IO_L43N_GCLK22_IRDY2_16") (pintype "bidirectional"))
    )
    (net (code "58") (name "FPGA_III_15") (class "Default")
      (node (ref "RA27") (pin "3B") (pinfunction "3B_3B") (pintype "passive"))
      (node (ref "U4") (pin "15") (pinfunction "IO_L44P_GCLK21_15") (pintype "bidirectional"))
    )
    (net (code "59") (name "FPGA_III_16") (class "Default")
      (node (ref "RA27") (pin "4B") (pinfunction "4B_4B") (pintype "passive"))
      (node (ref "U4") (pin "14") (pinfunction "IO_L44N_GCLK20_14") (pintype "bidirectional"))
    )
    (net (code "60") (name "FPGA_IV_1") (class "Default")
      (node (ref "RA31") (pin "1B") (pinfunction "1B_1B") (pintype "passive"))
      (node (ref "U4") (pin "142") (pinfunction "IO_L2P_142") (pintype "bidirectional"))
    )
    (net (code "61") (name "FPGA_IV_2") (class "Default")
      (node (ref "RA31") (pin "2B") (pinfunction "2B_2B") (pintype "passive"))
      (node (ref "U4") (pin "141") (pinfunction "IO_L2N_141") (pintype "bidirectional"))
    )
    (net (code "62") (name "FPGA_IV_3") (class "Default")
      (node (ref "RA31") (pin "3B") (pinfunction "3B_3B") (pintype "passive"))
      (node (ref "U4") (pin "140") (pinfunction "IO_L3P_140") (pintype "bidirectional"))
    )
    (net (code "63") (name "FPGA_IV_4") (class "Default")
      (node (ref "RA31") (pin "4B") (pinfunction "4B_4B") (pintype "passive"))
      (node (ref "U4") (pin "139") (pinfunction "IO_L3N_139") (pintype "bidirectional"))
    )
    (net (code "64") (name "FPGA_IV_5") (class "Default")
      (node (ref "RA32") (pin "1B") (pinfunction "1B_1B") (pintype "passive"))
      (node (ref "U4") (pin "138") (pinfunction "IO_L4P_138") (pintype "bidirectional"))
    )
    (net (code "65") (name "FPGA_IV_6") (class "Default")
      (node (ref "RA32") (pin "2B") (pinfunction "2B_2B") (pintype "passive"))
      (node (ref "U4") (pin "137") (pinfunction "IO_L4N_137") (pintype "bidirectional"))
    )
    (net (code "66") (name "FPGA_IV_7") (class "Default")
      (node (ref "RA32") (pin "3B") (pinfunction "3B_3B") (pintype "passive"))
      (node (ref "U4") (pin "134") (pinfunction "IO_L34P_GCLK19_134") (pintype "bidirectional"))
    )
    (net (code "67") (name "FPGA_IV_8") (class "Default")
      (node (ref "RA32") (pin "4B") (pinfunction "4B_4B") (pintype "passive"))
      (node (ref "U4") (pin "133") (pinfunction "IO_L34N_GCLK18_133") (pintype "bidirectional"))
    )
    (net (code "68") (name "FPGA_IV_9") (class "Default")
      (node (ref "RA33") (pin "1B") (pinfunction "1B_1B") (pintype "passive"))
      (node (ref "U4") (pin "132") (pinfunction "IO_L35P_GCLK17_132") (pintype "bidirectional"))
    )
    (net (code "69") (name "FPGA_IV_10") (class "Default")
      (node (ref "RA33") (pin "2B") (pinfunction "2B_2B") (pintype "passive"))
      (node (ref "U4") (pin "131") (pinfunction "IO_L35N_GCLK16_131") (pintype "bidirectional"))
    )
    (net (code "70") (name "FPGA_IV_11") (class "Default")
      (node (ref "RA33") (pin "3B") (pinfunction "3B_3B") (pintype "passive"))
      (node (ref "U4") (pin "127") (pinfunction "IO_L36P_GCLK15_127") (pintype "bidirectional"))
    )
    (net (code "71") (name "FPGA_IV_12") (class "Default")
      (node (ref "RA33") (pin "4B") (pinfunction "4B_4B") (pintype "passive"))
      (node (ref "U4") (pin "126") (pinfunction "IO_L36N_GCLK14_126") (pintype "bidirectional"))
    )
    (net (code "72") (name "FPGA_IV_13") (class "Default")
      (node (ref "RA34") (pin "1B") (pinfunction "1B_1B") (pintype "passive"))
      (node (ref "U4") (pin "124") (pinfunction "IO_L37P_GCLK13_124") (pintype "bidirectional"))
    )
    (net (code "73") (name "FPGA_IV_14") (class "Default")
      (node (ref "RA34") (pin "2B") (pinfunction "2B_2B") (pintype "passive"))
      (node (ref "U4") (pin "123") (pinfunction "IO_L37N_GCLK12_123") (pintype "bidirectional"))
    )
    (net (code "74") (name "FPGA_IV_15") (class "Default")
      (node (ref "RA34") (pin "3B") (pinfunction "3B_3B") (pintype "passive"))
      (node (ref "U4") (pin "121") (pinfunction "IO_L62P_121") (pintype "bidirectional"))
    )
    (net (code "75") (name "FPGA_IV_16") (class "Default")
      (node (ref "RA34") (pin "4B") (pinfunction "4B_4B") (pintype "passive"))
      (node (ref "U4") (pin "120") (pinfunction "IO_L62N_VREF_120") (pintype "bidirectional"))
    )
    (net (code "76") (name "FPGA_TCK") (class "Default")
      (node (ref "R10") (pin "2") (pinfunction "2_2") (pintype "passive"))
      (node (ref "U4") (pin "109") (pinfunction "TCK_109") (pintype "bidirectional"))
      (node (ref "X23") (pin "6") (pinfunction "6_6") (pintype "passive"))
    )
    (net (code "77") (name "FPGA_TDI") (class "Default")
      (node (ref "R9") (pin "2") (pinfunction "2_2") (pintype "passive"))
      (node (ref "U4") (pin "110") (pinfunction "TDI_110") (pintype "bidirectional"))
      (node (ref "X23") (pin "10") (pinfunction "10_10") (pintype "passive"))
    )
    (net (code "78") (name "FPGA_TDO") (class "Default")
      (node (ref "R11") (pin "1") (pinfunction "1_1") (pintype "passive"))
      (node (ref "U4") (pin "106") (pinfunction "TDO_106") (pintype "bidirectional"))
    )
    (net (code "79") (name "FPGA_TMS") (class "Default")
      (node (ref "R8") (pin "1") (pinfunction "1_1") (pintype "passive"))
      (node (ref "U4") (pin "107") (pinfunction "TMS_107") (pintype "bidirectional"))
      (node (ref "X23") (pin "4") (pinfunction "4_4") (pintype "passive"))
    )
    (net (code "80") (name "GND") (class "Default")
      (node (ref "C1") (pin "2") (pinfunction "2_2") (pintype "passive"))
      (node (ref "C10") (pin "2") (pinfunction "2_2") (pintype "passive"))
      (node (ref "C11") (pin "2") (pinfunction "2_2") (pintype "passive"))
      (node (ref "C12") (pin "2") (pinfunction "2_2") (pintype "passive"))
      (node (ref "C13") (pin "2") (pinfunction "2_2") (pintype "passive"))
      (node (ref "C14") (pin "2") (pinfunction "2_2") (pintype "passive"))
      (node (ref "C15") (pin "2") (pinfunction "2_2") (pintype "passive"))
      (node (ref "C16") (pin "2") (pinfunction "2_2") (pintype "passive"))
      (node (ref "C17") (pin "2") (pinfunction "2_2") (pintype "passive"))
      (node (ref "C18") (pin "2") (pinfunction "2_2") (pintype "passive"))
      (node (ref "C19") (pin "2") (pinfunction "2_2") (pintype "passive"))
      (node (ref "C2") (pin "2") (pinfunction "2_2") (pintype "passive"))
      (node (ref "C20") (pin "2") (pinfunction "2_2") (pintype "passive"))
      (node (ref "C21") (pin "2") (pinfunction "2_2") (pintype "passive"))
      (node (ref "C22") (pin "2") (pinfunction "2_2") (pintype "passive"))
      (node (ref "C23") (pin "2") (pinfunction "2_2") (pintype "passive"))
      (node (ref "C24") (pin "2") (pinfunction "2_2") (pintype "passive"))
      (node (ref "C25") (pin "2") (pinfunction "2_2") (pintype "passive"))
      (node (ref "C26") (pin "2") (pinfunction "2_2") (pintype "passive"))
      (node (ref "C27") (pin "2") (pinfunction "2_2") (pintype "passive"))
      (node (ref "C28") (pin "2") (pinfunction "2_2") (pintype "passive"))
      (node (ref "C29") (pin "2") (pinfunction "2_2") (pintype "passive"))
      (node (ref "C3") (pin "2") (pinfunction "2_2") (pintype "passive"))
      (node (ref "C30") (pin "2") (pinfunction "2_2") (pintype "passive"))
      (node (ref "C31") (pin "2") (pinfunction "2_2") (pintype "passive"))
      (node (ref "C32") (pin "2") (pinfunction "2_2") (pintype "passive"))
      (node (ref "C33") (pin "2") (pinfunction "2_2") (pintype "passive"))
      (node (ref "C34") (pin "2") (pinfunction "2_2") (pintype "passive"))
      (node (ref "C35") (pin "2") (pinfunction "2_2") (pintype "passive"))
      (node (ref "C36") (pin "2") (pinfunction "2_2") (pintype "passive"))
      (node (ref "C37") (pin "2") (pinfunction "2_2") (pintype "passive"))
      (node (ref "C38") (pin "2") (pinfunction "2_2") (pintype "passive"))
      (node (ref "C39") (pin "2") (pinfunction "2_2") (pintype "passive"))
      (node (ref "C4") (pin "2") (pinfunction "2_2") (pintype "passive"))
      (node (ref "C40") (pin "2") (pinfunction "2_2") (pintype "passive"))
      (node (ref "C41") (pin "2") (pinfunction "2_2") (pintype "passive"))
      (node (ref "C42") (pin "2") (pinfunction "2_2") (pintype "passive"))
      (node (ref "C43") (pin "2") (pinfunction "2_2") (pintype "passive"))
      (node (ref "C44") (pin "2") (pinfunction "2_2") (pintype "passive"))
      (node (ref "C45") (pin "2") (pinfunction "2_2") (pintype "passive"))
      (node (ref "C46") (pin "2") (pinfunction "2_2") (pintype "passive"))
      (node (ref "C47") (pin "2") (pinfunction "2_2") (pintype "passive"))
      (node (ref "C48") (pin "2") (pinfunction "2_2") (pintype "passive"))
      (node (ref "C49") (pin "2") (pinfunction "2_2") (pintype "passive"))
      (node (ref "C5") (pin "2") (pinfunction "2_2") (pintype "passive"))
      (node (ref "C50") (pin "2") (pinfunction "2_2") (pintype "passive"))
      (node (ref "C51") (pin "2") (pinfunction "2_2") (pintype "passive"))
      (node (ref "C52") (pin "2") (pinfunction "2_2") (pintype "passive"))
      (node (ref "C53") (pin "2") (pinfunction "2_2") (pintype "passive"))
      (node (ref "C54") (pin "2") (pinfunction "2_2") (pintype "passive"))
      (node (ref "C55") (pin "2") (pinfunction "2_2") (pintype "passive"))
      (node (ref "C56") (pin "2") (pinfunction "2_2") (pintype "passive"))
      (node (ref "C57") (pin "2") (pinfunction "2_2") (pintype "passive"))
      (node (ref "C58") (pin "2") (pinfunction "2_2") (pintype "passive"))
      (node (ref "C59") (pin "2") (pinfunction "2_2") (pintype "passive"))
      (node (ref "C6") (pin "2") (pinfunction "2_2") (pintype "passive"))
      (node (ref "C60") (pin "2") (pinfunction "2_2") (pintype "passive"))
      (node (ref "C61") (pin "2") (pinfunction "2_2") (pintype "passive"))
      (node (ref "C62") (pin "2") (pinfunction "2_2") (pintype "passive"))
      (node (ref "C63") (pin "2") (pinfunction "2_2") (pintype "passive"))
      (node (ref "C64") (pin "2") (pinfunction "2_2") (pintype "passive"))
      (node (ref "C7") (pin "2") (pinfunction "2_2") (pintype "passive"))
      (node (ref "C8") (pin "2") (pinfunction "2_2") (pintype "passive"))
      (node (ref "C9") (pin "2") (pinfunction "2_2") (pintype "passive"))
      (node (ref "C901") (pin "2") (pinfunction "2_2") (pintype "passive"))
      (node (ref "C902") (pin "2") (pinfunction "2_2") (pintype "passive"))
      (node (ref "C903") (pin "2") (pinfunction "2_2") (pintype "passive"))
      (node (ref "C904") (pin "2") (pinfunction "2_2") (pintype "passive"))
      (node (ref "C905") (pin "2") (pinfunction "2_2") (pintype "passive"))
      (node (ref "C906") (pin "2") (pinfunction "2_2") (pintype "passive"))
      (node (ref "C907") (pin "2") (pinfunction "2_2") (pintype "passive"))
      (node (ref "D1") (pin "2") (pinfunction "GND_2") (pintype "power_in"))
      (node (ref "L1") (pin "2") (pinfunction "F_2") (pintype "passive"))
      (node (ref "L5") (pin "1") (pinfunction "E_1") (pintype "passive"))
      (node (ref "Q1") (pin "2") (pinfunction "GND_2") (pintype "power_in"))
      (node (ref "Q1") (pin "4") (pinfunction "GND_4") (pintype "power_in"))
      (node (ref "Q2") (pin "2") (pinfunction "GND_2") (pintype "power_in"))
      (node (ref "R1") (pin "1") (pinfunction "1_1") (pintype "passive"))
      (node (ref "R17") (pin "1") (pinfunction "1_1") (pintype "passive"))
      (node (ref "R22") (pin "1") (pinfunction "1_1") (pintype "passive"))
      (node (ref "R30") (pin "1") (pinfunction "1_1") (pintype "passive"))
      (node (ref "R7") (pin "1") (pinfunction "1_1") (pintype "passive"))
      (node (ref "R901") (pin "1") (pinfunction "1_1") (pintype "passive"))
      (node (ref "R902") (pin "1") (pinfunction "1_1") (pintype "passive"))
      (node (ref "R903") (pin "1") (pinfunction "1_1") (pintype "passive"))
      (node (ref "R904") (pin "1") (pinfunction "1_1") (pintype "passive"))
      (node (ref "R905") (pin "1") (pinfunction "1_1") (pintype "passive"))
      (node (ref "R906") (pin "1") (pinfunction "1_1") (pintype "passive"))
      (node (ref "R907") (pin "1") (pinfunction "1_1") (pintype "passive"))
      (node (ref "SV1") (pin "2") (pinfunction "2_2") (pintype "passive"))
      (node (ref "SW1") (pin "3") (pinfunction "3_3") (pintype "passive"))
      (node (ref "SW1") (pin "4") (pinfunction "4_4") (pintype "passive"))
      (node (ref "T1") (pin "2") (pinfunction "E_2") (pintype "tri_state"))
      (node (ref "T2") (pin "2") (pinfunction "E_2") (pintype "tri_state"))
      (node (ref "T3") (pin "2") (pinfunction "E_2") (pintype "tri_state"))
      (node (ref "T4") (pin "2") (pinfunction "E_2") (pintype "tri_state"))
      (node (ref "T5") (pin "2") (pinfunction "E_2") (pintype "tri_state"))
      (node (ref "TP4") (pin "1") (pinfunction "1_1") (pintype "passive"))
      (node (ref "TP5") (pin "1") (pinfunction "1_1") (pintype "passive"))
      (node (ref "U1") (pin "114") (pinfunction "GND_114") (pintype "power_in"))
      (node (ref "U1") (pin "17") (pinfunction "GND_17") (pintype "power_in"))
      (node (ref "U1") (pin "48") (pinfunction "GND_48") (pintype "power_in"))
      (node (ref "U1") (pin "55") (pinfunction "GND_55") (pintype "power_in"))
      (node (ref "U1") (pin "58") (pinfunction "GND_58") (pintype "power_in"))
      (node (ref "U1") (pin "80") (pinfunction "GND_80") (pintype "power_in"))
      (node (ref "U2") (pin "2") (pinfunction "GND_2") (pintype "power_in"))
      (node (ref "U2") (pin "4") (pinfunction "GND_4") (pintype "power_in"))
      (node (ref "U3") (pin "2") (pinfunction "GND_2") (pintype "power_in"))
      (node (ref "U4") (pin "108") (pinfunction "GND_108") (pintype "power_in"))
      (node (ref "U4") (pin "113") (pinfunction "GND_113") (pintype "power_in"))
      (node (ref "U4") (pin "13") (pinfunction "GND_13") (pintype "power_in"))
      (node (ref "U4") (pin "130") (pinfunction "GND_130") (pintype "power_in"))
      (node (ref "U4") (pin "136") (pinfunction "GND_136") (pintype "power_in"))
      (node (ref "U4") (pin "25") (pinfunction "GND_25") (pintype "power_in"))
      (node (ref "U4") (pin "3") (pinfunction "GND_3") (pintype "power_in"))
      (node (ref "U4") (pin "49") (pinfunction "GND_49") (pintype "power_in"))
      (node (ref "U4") (pin "54") (pinfunction "GND_54") (pintype "power_in"))
      (node (ref "U4") (pin "68") (pinfunction "GND_68") (pintype "power_in"))
      (node (ref "U4") (pin "73") (pinfunction "SUSPEND_73") (pintype "input"))
      (node (ref "U4") (pin "77") (pinfunction "GND_77") (pintype "power_in"))
      (node (ref "U4") (pin "91") (pinfunction "GND_91") (pintype "power_in"))
      (node (ref "U4") (pin "96") (pinfunction "GND_96") (pintype "power_in"))
      (node (ref "U5") (pin "4") (pinfunction "VSS_4") (pintype "power_in"))
      (node (ref "U6") (pin "2") (pinfunction "GND_2") (pintype "power_in"))
      (node (ref "U6") (pin "4") (pinfunction "GND_4") (pintype "power_in"))
      (node (ref "X1") (pin "10") (pinfunction "10_10") (pintype "bidirectional"))
      (node (ref "X1") (pin "17") (pinfunction "17_17") (pintype "bidirectional"))
      (node (ref "X1") (pin "22") (pinfunction "22_22") (pintype "bidirectional"))
      (node (ref "X1") (pin "29") (pinfunction "29_29") (pintype "bidirectional"))
      (node (ref "X1") (pin "34") (pinfunction "34_34") (pintype "bidirectional"))
      (node (ref "X1") (pin "41") (pinfunction "41_41") (pintype "bidirectional"))
      (node (ref "X1") (pin "42") (pinfunction "42_42") (pintype "bidirectional"))
      (node (ref "X1") (pin "43") (pinfunction "43_43") (pintype "bidirectional"))
      (node (ref "X1") (pin "44") (pinfunction "44_44") (pintype "bidirectional"))
      (node (ref "X1") (pin "7") (pinfunction "7_7") (pintype "bidirectional"))
      (node (ref "X1") (pin "8") (pinfunction "8_8") (pintype "bidirectional"))
      (node (ref "X1") (pin "9") (pinfunction "9_9") (pintype "bidirectional"))
      (node (ref "X11") (pin "1") (pinfunction "1_1") (pintype "passive"))
      (node (ref "X11") (pin "3") (pinfunction "3_3") (pintype "passive"))
      (node (ref "X11") (pin "31") (pinfunction "31_31") (pintype "passive"))
      (node (ref "X11") (pin "33") (pinfunction "33_33") (pintype "passive"))
      (node (ref "X12") (pin "1") (pinfunction "1_1") (pintype "passive"))
      (node (ref "X12") (pin "3") (pinfunction "3_3") (pintype "passive"))
      (node (ref "X12") (pin "31") (pinfunction "31_31") (pintype "passive"))
      (node (ref "X12") (pin "33") (pinfunction "33_33") (pintype "passive"))
      (node (ref "X13") (pin "1") (pinfunction "1_1") (pintype "passive"))
      (node (ref "X13") (pin "3") (pinfunction "3_3") (pintype "passive"))
      (node (ref "X13") (pin "31") (pinfunction "31_31") (pintype "passive"))
      (node (ref "X13") (pin "33") (pinfunction "33_33") (pintype "passive"))
      (node (ref "X2") (pin "10") (pinfunction "10_10") (pintype "bidirectional"))
      (node (ref "X2") (pin "17") (pinfunction "17_17") (pintype "bidirectional"))
      (node (ref "X2") (pin "22") (pinfunction "22_22") (pintype "bidirectional"))
      (node (ref "X2") (pin "29") (pinfunction "29_29") (pintype "bidirectional"))
      (node (ref "X2") (pin "34") (pinfunction "34_34") (pintype "bidirectional"))
      (node (ref "X2") (pin "41") (pinfunction "41_41") (pintype "bidirectional"))
      (node (ref "X2") (pin "42") (pinfunction "42_42") (pintype "bidirectional"))
      (node (ref "X2") (pin "43") (pinfunction "43_43") (pintype "bidirectional"))
      (node (ref "X2") (pin "44") (pinfunction "44_44") (pintype "bidirectional"))
      (node (ref "X2") (pin "7") (pinfunction "7_7") (pintype "bidirectional"))
      (node (ref "X2") (pin "8") (pinfunction "8_8") (pintype "bidirectional"))
      (node (ref "X2") (pin "9") (pinfunction "9_9") (pintype "bidirectional"))
      (node (ref "X23") (pin "1") (pinfunction "1_1") (pintype "passive"))
      (node (ref "X23") (pin "11") (pinfunction "11_11") (pintype "passive"))
      (node (ref "X23") (pin "13") (pinfunction "13_13") (pintype "passive"))
      (node (ref "X23") (pin "3") (pinfunction "3_3") (pintype "passive"))
      (node (ref "X23") (pin "5") (pinfunction "5_5") (pintype "passive"))
      (node (ref "X23") (pin "7") (pinfunction "7_7") (pintype "passive"))
      (node (ref "X23") (pin "9") (pinfunction "9_9") (pintype "passive"))
      (node (ref "X24") (pin "3") (pinfunction "3_3") (pintype "passive"))
      (node (ref "X24") (pin "5") (pinfunction "5_5") (pintype "passive"))
      (node (ref "X3") (pin "10") (pinfunction "10_10") (pintype "bidirectional"))
      (node (ref "X3") (pin "17") (pinfunction "17_17") (pintype "bidirectional"))
      (node (ref "X3") (pin "22") (pinfunction "22_22") (pintype "bidirectional"))
      (node (ref "X3") (pin "29") (pinfunction "29_29") (pintype "bidirectional"))
      (node (ref "X3") (pin "34") (pinfunction "34_34") (pintype "bidirectional"))
      (node (ref "X3") (pin "41") (pinfunction "41_41") (pintype "bidirectional"))
      (node (ref "X3") (pin "42") (pinfunction "42_42") (pintype "bidirectional"))
      (node (ref "X3") (pin "43") (pinfunction "43_43") (pintype "bidirectional"))
      (node (ref "X3") (pin "44") (pinfunction "44_44") (pintype "bidirectional"))
      (node (ref "X3") (pin "7") (pinfunction "7_7") (pintype "bidirectional"))
      (node (ref "X3") (pin "8") (pinfunction "8_8") (pintype "bidirectional"))
      (node (ref "X3") (pin "9") (pinfunction "9_9") (pintype "bidirectional"))
      (node (ref "X4") (pin "10") (pinfunction "10_10") (pintype "bidirectional"))
      (node (ref "X4") (pin "17") (pinfunction "17_17") (pintype "bidirectional"))
      (node (ref "X4") (pin "22") (pinfunction "22_22") (pintype "bidirectional"))
      (node (ref "X4") (pin "29") (pinfunction "29_29") (pintype "bidirectional"))
      (node (ref "X4") (pin "34") (pinfunction "34_34") (pintype "bidirectional"))
      (node (ref "X4") (pin "41") (pinfunction "41_41") (pintype "bidirectional"))
      (node (ref "X4") (pin "42") (pinfunction "42_42") (pintype "bidirectional"))
      (node (ref "X4") (pin "43") (pinfunction "43_43") (pintype "bidirectional"))
      (node (ref "X4") (pin "44") (pinfunction "44_44") (pintype "bidirectional"))
      (node (ref "X4") (pin "7") (pinfunction "7_7") (pintype "bidirectional"))
      (node (ref "X4") (pin "8") (pinfunction "8_8") (pintype "bidirectional"))
      (node (ref "X4") (pin "9") (pinfunction "9_9") (pintype "bidirectional"))
      (node (ref "X5") (pin "1") (pinfunction "1_1") (pintype "passive"))
      (node (ref "X5") (pin "11") (pinfunction "11_11") (pintype "passive"))
      (node (ref "X5") (pin "13") (pinfunction "13_13") (pintype "passive"))
      (node (ref "X5") (pin "15") (pinfunction "15_15") (pintype "passive"))
      (node (ref "X5") (pin "17") (pinfunction "17_17") (pintype "passive"))
      (node (ref "X5") (pin "19") (pinfunction "19_19") (pintype "passive"))
      (node (ref "X5") (pin "21") (pinfunction "21_21") (pintype "passive"))
      (node (ref "X5") (pin "23") (pinfunction "23_23") (pintype "passive"))
      (node (ref "X5") (pin "3") (pinfunction "3_3") (pintype "passive"))
      (node (ref "X5") (pin "5") (pinfunction "5_5") (pintype "passive"))
      (node (ref "X5") (pin "7") (pinfunction "7_7") (pintype "passive"))
      (node (ref "X5") (pin "9") (pinfunction "9_9") (pintype "passive"))
      (node (ref "X6") (pin "4") (pinfunction "GND_4") (pintype "passive"))
      (node (ref "X7") (pin "1") (pinfunction "1_1") (pintype "passive"))
      (node (ref "X7") (pin "3") (pinfunction "3_3") (pintype "passive"))
      (node (ref "X7") (pin "31") (pinfunction "31_31") (pintype "passive"))
      (node (ref "X7") (pin "33") (pinfunction "33_33") (pintype "passive"))
      (node (ref "X8") (pin "8") (pinfunction "SH_8") (pintype "power_in"))
    )
    (net (code "81") (name "INIT") (class "Default")
      (node (ref "LD2") (pin "C") (pinfunction "K_C") (pintype "tri_state"))
      (node (ref "R3") (pin "1") (pinfunction "1_1") (pintype "passive"))
      (node (ref "TP20") (pin "1") (pinfunction "1_1") (pintype "passive"))
      (node (ref "U1") (pin "86") (pinfunction "PL5_86") (pintype "bidirectional"))
      (node (ref "U4") (pin "39") (pinfunction "INIT_39") (pintype "bidirectional"))
    )
    (net (code "82") (name "M0") (class "Default")
      (node (ref "R6") (pin "1") (pinfunction "1_1") (pintype "passive"))
      (node (ref "TP10") (pin "1") (pinfunction "1_1") (pintype "passive"))
      (node (ref "U4") (pin "69") (pinfunction "IO_L1N_M0_CMPMISO_69") (pintype "bidirectional"))
    )
    (net (code "83") (name "M1") (class "Default")
      (node (ref "R7") (pin "2") (pinfunction "2_2") (pintype "passive"))
      (node (ref "TP9") (pin "1") (pinfunction "1_1") (pintype "passive"))
      (node (ref "U4") (pin "60") (pinfunction "IO_L13P_M1_60") (pintype "bidirectional"))
    )
    (net (code "84") (name "MCU_II_1") (class "Default")
      (node (ref "RA17") (pin "1B") (pinfunction "1B_1B") (pintype "passive"))
      (node (ref "U1") (pin "96") (pinfunction "PB1_96") (pintype "bidirectional"))
    )
    (net (code "85") (name "MCU_II_2") (class "Default")
      (node (ref "RA17") (pin "2B") (pinfunction "2B_2B") (pintype "passive"))
      (node (ref "U1") (pin "95") (pinfunction "PB0_95") (pintype "bidirectional"))
    )
    (net (code "86") (name "MCU_II_3") (class "Default")
      (node (ref "RA17") (pin "3B") (pinfunction "3B_3B") (pintype "passive"))
      (node (ref "U1") (pin "107") (pinfunction "PN0_107") (pintype "bidirectional"))
    )
    (net (code "87") (name "MCU_II_4") (class "Default")
      (node (ref "RA17") (pin "4B") (pinfunction "4B_4B") (pintype "passive"))
      (node (ref "U1") (pin "108") (pinfunction "PN1_108") (pintype "bidirectional"))
    )
    (net (code "88") (name "MCU_II_5") (class "Default")
      (node (ref "RA18") (pin "1B") (pinfunction "1B_1B") (pintype "passive"))
      (node (ref "U1") (pin "109") (pinfunction "PN2_109") (pintype "bidirectional"))
    )
    (net (code "89") (name "MCU_II_6") (class "Default")
      (node (ref "RA18") (pin "2B") (pinfunction "2B_2B") (pintype "passive"))
      (node (ref "U1") (pin "110") (pinfunction "PN3_110") (pintype "bidirectional"))
    )
    (net (code "90") (name "MCU_II_7") (class "Default")
      (node (ref "RA18") (pin "3B") (pinfunction "3B_3B") (pintype "passive"))
      (node (ref "U1") (pin "111") (pinfunction "PN4_111") (pintype "bidirectional"))
    )
    (net (code "91") (name "MCU_II_8") (class "Default")
      (node (ref "RA18") (pin "4B") (pinfunction "4B_4B") (pintype "passive"))
      (node (ref "U1") (pin "112") (pinfunction "PN5_112") (pintype "bidirectional"))
    )
    (net (code "92") (name "MCU_II_9") (class "Default")
      (node (ref "RA19") (pin "1B") (pinfunction "1B_1B") (pintype "passive"))
      (node (ref "U1") (pin "72") (pinfunction "PM6_72") (pintype "bidirectional"))
    )
    (net (code "93") (name "MCU_II_10") (class "Default")
      (node (ref "RA19") (pin "2B") (pinfunction "2B_2B") (pintype "passive"))
      (node (ref "U1") (pin "71") (pinfunction "PM7_71") (pintype "bidirectional"))
    )
    (net (code "94") (name "MCU_II_11") (class "Default")
      (node (ref "RA20") (pin "1A") (pinfunction "1A_1A") (pintype "passive"))
      (node (ref "U1") (pin "120") (pinfunction "PB5_120") (pintype "bidirectional"))
    )
    (net (code "95") (name "MCU_II_12") (class "Default")
      (node (ref "RA20") (pin "2A") (pinfunction "2A_2A") (pintype "passive"))
      (node (ref "U1") (pin "121") (pinfunction "PB4_121") (pintype "bidirectional"))
    )
    (net (code "96") (name "MCU_II_13") (class "Default")
      (node (ref "RA20") (pin "3A") (pinfunction "3A_3A") (pintype "passive"))
      (node (ref "U1") (pin "123") (pinfunction "PE4_123") (pintype "bidirectional"))
    )
    (net (code "97") (name "MCU_II_14") (class "Default")
      (node (ref "RA20") (pin "4A") (pinfunction "4A_4A") (pintype "passive"))
      (node (ref "U1") (pin "124") (pinfunction "PE5_124") (pintype "bidirectional"))
    )
    (net (code "98") (name "MCU_II_15") (class "Default")
      (node (ref "RA21") (pin "1A") (pinfunction "1A_1A") (pintype "passive"))
      (node (ref "U1") (pin "125") (pinfunction "PD4_125") (pintype "bidirectional"))
    )
    (net (code "99") (name "MCU_II_16") (class "Default")
      (node (ref "RA21") (pin "2A") (pinfunction "2A_2A") (pintype "passive"))
      (node (ref "U1") (pin "126") (pinfunction "PD5_126") (pintype "bidirectional"))
    )
    (net (code "100") (name "MCU_I_1") (class "Default")
      (node (ref "RA10") (pin "1B") (pinfunction "1B_1B") (pintype "passive"))
      (node (ref "U1") (pin "34") (pinfunction "PA1_34") (pintype "bidirectional"))
    )
    (net (code "101") (name "MCU_I_2") (class "Default")
      (node (ref "RA10") (pin "2B") (pinfunction "2B_2B") (pintype "passive"))
      (node (ref "U1") (pin "33") (pinfunction "PA0_33") (pintype "bidirectional"))
    )
    (net (code "102") (name "MCU_I_3") (class "Default")
      (node (ref "RA10") (pin "3B") (pinfunction "3B_3B") (pintype "passive"))
      (node (ref "U1") (pin "29") (pinfunction "PH0_29") (pintype "bidirectional"))
    )
    (net (code "103") (name "MCU_I_4") (class "Default")
      (node (ref "RA10") (pin "4B") (pinfunction "4B_4B") (pintype "passive"))
      (node (ref "U1") (pin "30") (pinfunction "PH1_30") (pintype "bidirectional"))
    )
    (net (code "104") (name "MCU_I_5") (class "Default")
      (node (ref "RA11") (pin "1B") (pinfunction "1B_1B") (pintype "passive"))
      (node (ref "U1") (pin "15") (pinfunction "PE0_15") (pintype "bidirectional"))
    )
    (net (code "105") (name "MCU_I_6") (class "Default")
      (node (ref "RA11") (pin "2B") (pinfunction "2B_2B") (pintype "passive"))
      (node (ref "U1") (pin "14") (pinfunction "PE1_14") (pintype "bidirectional"))
    )
    (net (code "106") (name "MCU_I_7") (class "Default")
      (node (ref "RA11") (pin "3B") (pinfunction "3B_3B") (pintype "passive"))
      (node (ref "U1") (pin "13") (pinfunction "PE2_13") (pintype "bidirectional"))
    )
    (net (code "107") (name "MCU_I_8") (class "Default")
      (node (ref "RA11") (pin "4B") (pinfunction "4B_4B") (pintype "passive"))
      (node (ref "U1") (pin "12") (pinfunction "PE3_12") (pintype "bidirectional"))
    )
    (net (code "108") (name "MCU_I_9") (class "Default")
      (node (ref "RA12") (pin "1B") (pinfunction "1B_1B") (pintype "passive"))
      (node (ref "U1") (pin "74") (pinfunction "PM4_74") (pintype "bidirectional"))
    )
    (net (code "109") (name "MCU_I_10") (class "Default")
      (node (ref "RA12") (pin "2B") (pinfunction "2B_2B") (pintype "passive"))
      (node (ref "U1") (pin "73") (pinfunction "PM5_73") (pintype "bidirectional"))
    )
    (net (code "110") (name "MCU_I_11") (class "Default")
      (node (ref "RA13") (pin "1B") (pinfunction "1B_1B") (pintype "passive"))
      (node (ref "U1") (pin "4") (pinfunction "PD3_4") (pintype "bidirectional"))
    )
    (net (code "111") (name "MCU_I_12") (class "Default")
      (node (ref "RA13") (pin "2B") (pinfunction "2B_2B") (pintype "passive"))
      (node (ref "U1") (pin "3") (pinfunction "PD2_3") (pintype "bidirectional"))
    )
    (net (code "112") (name "MCU_I_13") (class "Default")
      (node (ref "RA13") (pin "3B") (pinfunction "3B_3B") (pintype "passive"))
      (node (ref "U1") (pin "2") (pinfunction "PD1_2") (pintype "bidirectional"))
    )
    (net (code "113") (name "MCU_I_14") (class "Default")
      (node (ref "RA13") (pin "4B") (pinfunction "4B_4B") (pintype "passive"))
      (node (ref "U1") (pin "1") (pinfunction "PD0_1") (pintype "bidirectional"))
    )
    (net (code "114") (name "MCU_I_15") (class "Default")
      (node (ref "RA14") (pin "1B") (pinfunction "1B_1B") (pintype "passive"))
      (node (ref "U1") (pin "128") (pinfunction "PD7_128") (pintype "bidirectional"))
    )
    (net (code "115") (name "MCU_I_16") (class "Default")
      (node (ref "RA14") (pin "2B") (pinfunction "2B_2B") (pintype "passive"))
      (node (ref "U1") (pin "127") (pinfunction "PD6_127") (pintype "bidirectional"))
    )
    (net (code "116") (name "MCU_TCK") (class "Default")
      (node (ref "U1") (pin "100") (pinfunction "PC0/TCK/SWCLK_100") (pintype "bidirectional"))
      (node (ref "X24") (pin "4") (pinfunction "4_4") (pintype "passive"))
    )
    (net (code "117") (name "MCU_TDI") (class "Default")
      (node (ref "U1") (pin "98") (pinfunction "PC2/TDI_98") (pintype "bidirectional"))
      (node (ref "X24") (pin "8") (pinfunction "8_8") (pintype "passive"))
    )
    (net (code "118") (name "MCU_TDO") (class "Default")
      (node (ref "U1") (pin "97") (pinfunction "PC3/TDO/SWO_97") (pintype "bidirectional"))
      (node (ref "X24") (pin "6") (pinfunction "6_6") (pintype "passive"))
    )
    (net (code "119") (name "MCU_TMS") (class "Default")
      (node (ref "U1") (pin "99") (pinfunction "PC1/TMS/SWDIO_99") (pintype "bidirectional"))
      (node (ref "X24") (pin "2") (pinfunction "2_2") (pintype "passive"))
    )
    (net (code "120") (name "Net-(C14-Pad1)") (class "Default")
      (node (ref "C14") (pin "1") (pinfunction "1_1") (pintype "passive"))
      (node (ref "R9") (pin "1") (pinfunction "1_1") (pintype "passive"))
    )
    (net (code "121") (name "Net-(C15-Pad1)") (class "Default")
      (node (ref "C15") (pin "1") (pinfunction "1_1") (pintype "passive"))
      (node (ref "R10") (pin "1") (pinfunction "1_1") (pintype "passive"))
    )
    (net (code "122") (name "Net-(C45-Pad1)") (class "Default")
      (node (ref "C45") (pin "1") (pinfunction "1_1") (pintype "passive"))
      (node (ref "C46") (pin "1") (pinfunction "1_1") (pintype "passive"))
      (node (ref "C47") (pin "1") (pinfunction "1_1") (pintype "passive"))
      (node (ref "C48") (pin "1") (pinfunction "1_1") (pintype "passive"))
      (node (ref "U1") (pin "115") (pinfunction "VDDC_115") (pintype "power_in"))
      (node (ref "U1") (pin "87") (pinfunction "VDDC_87") (pintype "power_in"))
    )
    (net (code "123") (name "Net-(C901-Pad1)") (class "Default")
      (node (ref "C901") (pin "1") (pinfunction "1_1") (pintype "passive"))
      (node (ref "G901") (pin "1") (pinfunction "1_1") (pintype "passive"))
      (node (ref "R901") (pin "2") (pinfunction "2_2") (pintype "passive"))
    )
    (net (code "124") (name "Net-(C902-Pad1)") (class "Default")
      (node (ref "C902") (pin "1") (pinfunction "1_1") (pintype "passive"))
      (node (ref "G902") (pin "1") (pinfunction "1_1") (pintype "passive"))
      (node (ref "R902") (pin "2") (pinfunction "2_2") (pintype "passive"))
    )
    (net (code "125") (name "Net-(C903-Pad1)") (class "Default")
      (node (ref "C903") (pin "1") (pinfunction "1_1") (pintype "passive"))
      (node (ref "G903") (pin "1") (pinfunction "1_1") (pintype "passive"))
      (node (ref "R903") (pin "2") (pinfunction "2_2") (pintype "passive"))
    )
    (net (code "126") (name "Net-(C904-Pad1)") (class "Default")
      (node (ref "C904") (pin "1") (pinfunction "1_1") (pintype "passive"))
      (node (ref "G904") (pin "1") (pinfunction "1_1") (pintype "passive"))
      (node (ref "R904") (pin "2") (pinfunction "2_2") (pintype "passive"))
    )
    (net (code "127") (name "Net-(C905-Pad1)") (class "Default")
      (node (ref "C905") (pin "1") (pinfunction "1_1") (pintype "passive"))
      (node (ref "G905") (pin "1") (pinfunction "1_1") (pintype "passive"))
      (node (ref "R905") (pin "2") (pinfunction "2_2") (pintype "passive"))
    )
    (net (code "128") (name "Net-(C906-Pad1)") (class "Default")
      (node (ref "C906") (pin "1") (pinfunction "1_1") (pintype "passive"))
      (node (ref "G906") (pin "1") (pinfunction "1_1") (pintype "passive"))
      (node (ref "R906") (pin "2") (pinfunction "2_2") (pintype "passive"))
    )
    (net (code "129") (name "Net-(C907-Pad1)") (class "Default")
      (node (ref "C907") (pin "1") (pinfunction "1_1") (pintype "passive"))
      (node (ref "G907") (pin "1") (pinfunction "1_1") (pintype "passive"))
      (node (ref "R907") (pin "2") (pinfunction "2_2") (pintype "passive"))
    )
    (net (code "130") (name "Net-(D2-BC)") (class "Default")
      (node (ref "D2") (pin "2") (pinfunction "BC_2") (pintype "bidirectional"))
      (node (ref "R19") (pin "2") (pinfunction "2_2") (pintype "passive"))
    )
    (net (code "131") (name "Net-(D2-GC)") (class "Default")
      (node (ref "D2") (pin "4") (pinfunction "GC_4") (pintype "bidirectional"))
      (node (ref "R21") (pin "2") (pinfunction "2_2") (pintype "passive"))
    )
    (net (code "132") (name "Net-(D2-RC)") (class "Default")
      (node (ref "D2") (pin "3") (pinfunction "RC_3") (pintype "bidirectional"))
      (node (ref "R20") (pin "2") (pinfunction "2_2") (pintype "passive"))
    )
    (net (code "133") (name "Net-(L1-E)") (class "Default")
      (node (ref "L1") (pin "1") (pinfunction "E_1") (pintype "passive"))
      (node (ref "U1") (pin "10") (pinfunction "GNDA_10") (pintype "power_in"))
    )
    (net (code "134") (name "Net-(L2-E)") (class "Default")
      (node (ref "C60") (pin "1") (pinfunction "1_1") (pintype "passive"))
      (node (ref "L2") (pin "1") (pinfunction "E_1") (pintype "passive"))
      (node (ref "U1") (pin "8") (pinfunction "VDDA_8") (pintype "power_in"))
    )
    (net (code "135") (name "Net-(LD1-PadA)") (class "Default")
      (node (ref "LD1") (pin "A") (pinfunction "A_A") (pintype "input"))
      (node (ref "R4") (pin "1") (pinfunction "1_1") (pintype "passive"))
    )
    (net (code "136") (name "Net-(LD2-PadA)") (class "Default")
      (node (ref "LD2") (pin "A") (pinfunction "A_A") (pintype "input"))
      (node (ref "R2") (pin "1") (pinfunction "1_1") (pintype "passive"))
    )
    (net (code "137") (name "Net-(Q1-XTALA)") (class "Default")
      (node (ref "C49") (pin "1") (pinfunction "1_1") (pintype "passive"))
      (node (ref "Q1") (pin "1") (pinfunction "XTALA_1") (pintype "passive"))
      (node (ref "R12") (pin "1") (pinfunction "1_1") (pintype "passive"))
    )
    (net (code "138") (name "Net-(Q2-ENABLE)") (class "Default")
      (node (ref "Q2") (pin "1") (pinfunction "ENABLE_1") (pintype "input"))
      (node (ref "R18") (pin "1") (pinfunction "1_1") (pintype "passive"))
    )
    (net (code "139") (name "Net-(Q2-OUT)") (class "Default")
      (node (ref "Q2") (pin "3") (pinfunction "OUT_3") (pintype "output"))
      (node (ref "U4") (pin "51") (pinfunction "IO_L31P_GCLK31_D14_51") (pintype "bidirectional"))
    )
    (net (code "140") (name "Net-(R11-Pad2)") (class "Default")
      (node (ref "R11") (pin "2") (pinfunction "2_2") (pintype "passive"))
      (node (ref "X23") (pin "8") (pinfunction "8_8") (pintype "passive"))
    )
    (net (code "141") (name "Net-(R14-Pad1)") (class "Default")
      (node (ref "R14") (pin "1") (pinfunction "1_1") (pintype "passive"))
      (node (ref "SW1") (pin "1") (pinfunction "1_1") (pintype "passive"))
      (node (ref "SW1") (pin "2") (pinfunction "2_2") (pintype "passive"))
    )
    (net (code "142") (name "Net-(R15-Pad1)") (class "Default")
      (node (ref "R15") (pin "1") (pinfunction "1_1") (pintype "passive"))
      (node (ref "SV1") (pin "1") (pinfunction "1_1") (pintype "passive"))
    )
    (net (code "143") (name "Net-(R16-Pad1)") (class "Default")
      (node (ref "R16") (pin "1") (pinfunction "1_1") (pintype "passive"))
      (node (ref "SV1") (pin "3") (pinfunction "3_3") (pintype "passive"))
    )
    (net (code "144") (name "Net-(T1-C)") (class "Default")
      (node (ref "R19") (pin "1") (pinfunction "1_1") (pintype "passive"))
      (node (ref "T1") (pin "3") (pinfunction "C_3") (pintype "open_collector"))
    )
    (net (code "145") (name "Net-(T2-C)") (class "Default")
      (node (ref "R20") (pin "1") (pinfunction "1_1") (pintype "passive"))
      (node (ref "T2") (pin "3") (pinfunction "C_3") (pintype "open_collector"))
    )
    (net (code "146") (name "Net-(T3-C)") (class "Default")
      (node (ref "R21") (pin "1") (pinfunction "1_1") (pintype "passive"))
      (node (ref "T3") (pin "3") (pinfunction "C_3") (pintype "open_collector"))
    )
    (net (code "147") (name "Net-(T4-C)") (class "Default")
      (node (ref "T4") (pin "3") (pinfunction "C_3") (pintype "open_collector"))
      (node (ref "X8") (pin "12") (pinfunction "K_12") (pintype "bidirectional"))
    )
    (net (code "148") (name "Net-(T5-C)") (class "Default")
      (node (ref "T5") (pin "3") (pinfunction "C_3") (pintype "open_collector"))
      (node (ref "X8") (pin "10") (pinfunction "K_10") (pintype "bidirectional"))
    )
    (net (code "149") (name "Net-(U1B-VREFA+)") (class "Default")
      (node (ref "C52") (pin "1") (pinfunction "1_1") (pintype "passive"))
      (node (ref "C53") (pin "1") (pinfunction "1_1") (pintype "passive"))
      (node (ref "U1") (pin "9") (pinfunction "VREFA+_9") (pintype "power_in"))
      (node (ref "U3") (pin "5") (pinfunction "VREF_5") (pintype "power_in"))
    )
    (net (code "150") (name "Net-(U2-V_OUT)") (class "Default")
      (node (ref "C18") (pin "1") (pinfunction "1_1") (pintype "passive"))
      (node (ref "C57") (pin "1") (pinfunction "1_1") (pintype "passive"))
      (node (ref "J_3.3") (pin "2") (pinfunction "2_2") (pintype "passive"))
      (node (ref "TP2") (pin "1") (pinfunction "1_1") (pintype "passive"))
      (node (ref "U2") (pin "3") (pinfunction "V_OUT_3") (pintype "power_in"))
    )
    (net (code "151") (name "Net-(U4A-IO_L63N_SCP6)") (class "Default")
      (node (ref "RA9") (pin "3B") (pinfunction "3B_3B") (pintype "passive"))
      (node (ref "U4") (pin "118") (pinfunction "IO_L63N_SCP6_118") (pintype "bidirectional"))
    )
    (net (code "152") (name "Net-(U4A-IO_L63P_SCP7)") (class "Default")
      (node (ref "RA9") (pin "4B") (pinfunction "4B_4B") (pintype "passive"))
      (node (ref "U4") (pin "119") (pinfunction "IO_L63P_SCP7_119") (pintype "bidirectional"))
    )
    (net (code "153") (name "Net-(U4A-IO_L64N_SCP4)") (class "Default")
      (node (ref "RA9") (pin "1B") (pinfunction "1B_1B") (pintype "passive"))
      (node (ref "U4") (pin "116") (pinfunction "IO_L64N_SCP4_116") (pintype "bidirectional"))
    )
    (net (code "154") (name "Net-(U4A-IO_L64P_SCP5)") (class "Default")
      (node (ref "RA9") (pin "2B") (pinfunction "2B_2B") (pintype "passive"))
      (node (ref "U4") (pin "117") (pinfunction "IO_L64P_SCP5_117") (pintype "bidirectional"))
    )
    (net (code "155") (name "Net-(U4A-IO_L65N_SCP2)") (class "Default")
      (node (ref "RA8") (pin "3A") (pinfunction "3A_3A") (pintype "passive"))
      (node (ref "U4") (pin "114") (pinfunction "IO_L65N_SCP2_114") (pintype "bidirectional"))
    )
    (net (code "156") (name "Net-(U4A-IO_L65P_SCP3)") (class "Default")
      (node (ref "RA8") (pin "4A") (pinfunction "4A_4A") (pintype "passive"))
      (node (ref "U4") (pin "115") (pinfunction "IO_L65P_SCP3_115") (pintype "bidirectional"))
    )
    (net (code "157") (name "Net-(U4A-IO_L66N_SCP0)") (class "Default")
      (node (ref "RA8") (pin "1A") (pinfunction "1A_1A") (pintype "passive"))
      (node (ref "U4") (pin "111") (pinfunction "IO_L66N_SCP0_111") (pintype "bidirectional"))
    )
    (net (code "158") (name "Net-(U4A-IO_L66P_SCP1)") (class "Default")
      (node (ref "RA8") (pin "2A") (pinfunction "2A_2A") (pintype "passive"))
      (node (ref "U4") (pin "112") (pinfunction "IO_L66P_SCP1_112") (pintype "bidirectional"))
    )
    (net (code "159") (name "Net-(U4B-IO_L1N_VREF)") (class "Default")
      (node (ref "RA7") (pin "3A") (pinfunction "3A_3A") (pintype "passive"))
      (node (ref "U4") (pin "104") (pinfunction "IO_L1N_VREF_104") (pintype "bidirectional"))
    )
    (net (code "160") (name "Net-(U4B-IO_L1P)") (class "Default")
      (node (ref "RA7") (pin "4A") (pinfunction "4A_4A") (pintype "passive"))
      (node (ref "U4") (pin "105") (pinfunction "IO_L1P_105") (pintype "bidirectional"))
    )
    (net (code "161") (name "Net-(U4B-IO_L32N)") (class "Default")
      (node (ref "RA7") (pin "1A") (pinfunction "1A_1A") (pintype "passive"))
      (node (ref "U4") (pin "101") (pinfunction "IO_L32N_101") (pintype "bidirectional"))
    )
    (net (code "162") (name "Net-(U4B-IO_L32P)") (class "Default")
      (node (ref "RA7") (pin "2A") (pinfunction "2A_2A") (pintype "passive"))
      (node (ref "U4") (pin "102") (pinfunction "IO_L32P_102") (pintype "bidirectional"))
    )
    (net (code "163") (name "Net-(U4B-IO_L33N)") (class "Default")
      (node (ref "RA6") (pin "3A") (pinfunction "3A_3A") (pintype "passive"))
      (node (ref "U4") (pin "99") (pinfunction "IO_L33N_99") (pintype "bidirectional"))
    )
    (net (code "164") (name "Net-(U4B-IO_L33P)") (class "Default")
      (node (ref "RA6") (pin "4A") (pinfunction "4A_4A") (pintype "passive"))
      (node (ref "U4") (pin "100") (pinfunction "IO_L33P_100") (pintype "bidirectional"))
    )
    (net (code "165") (name "Net-(U4B-IO_L34N)") (class "Default")
      (node (ref "RA6") (pin "1A") (pinfunction "1A_1A") (pintype "passive"))
      (node (ref "U4") (pin "97") (pinfunction "IO_L34N_97") (pintype "bidirectional"))
    )
    (net (code "166") (name "Net-(U4B-IO_L34P)") (class "Default")
      (node (ref "RA6") (pin "2A") (pinfunction "2A_2A") (pintype "passive"))
      (node (ref "U4") (pin "98") (pinfunction "IO_L34P_98") (pintype "bidirectional"))
    )
    (net (code "167") (name "Net-(U4B-IO_L40N_GCLK10)") (class "Default")
      (node (ref "RA5") (pin "3A") (pinfunction "3A_3A") (pintype "passive"))
      (node (ref "U4") (pin "94") (pinfunction "IO_L40N_GCLK10_94") (pintype "bidirectional"))
    )
    (net (code "168") (name "Net-(U4B-IO_L40P_GCLK11)") (class "Default")
      (node (ref "RA5") (pin "4A") (pinfunction "4A_4A") (pintype "passive"))
      (node (ref "U4") (pin "95") (pinfunction "IO_L40P_GCLK11_95") (pintype "bidirectional"))
    )
    (net (code "169") (name "Net-(U4B-IO_L41N_GCLK8)") (class "Default")
      (node (ref "RA5") (pin "1A") (pinfunction "1A_1A") (pintype "passive"))
      (node (ref "U4") (pin "92") (pinfunction "IO_L41N_GCLK8_92") (pintype "bidirectional"))
    )
    (net (code "170") (name "Net-(U4B-IO_L41P_GCLK9_IRDY1)") (class "Default")
      (node (ref "RA5") (pin "2A") (pinfunction "2A_2A") (pintype "passive"))
      (node (ref "U4") (pin "93") (pinfunction "IO_L41P_GCLK9_IRDY1_93") (pintype "bidirectional"))
    )
    (net (code "171") (name "Net-(U4B-IO_L42N_GCLK6_TRDY1)") (class "Default")
      (node (ref "RA4") (pin "3A") (pinfunction "3A_3A") (pintype "passive"))
      (node (ref "U4") (pin "87") (pinfunction "IO_L42N_GCLK6_TRDY1_87") (pintype "bidirectional"))
    )
    (net (code "172") (name "Net-(U4B-IO_L42P_GCLK7)") (class "Default")
      (node (ref "RA4") (pin "4A") (pinfunction "4A_4A") (pintype "passive"))
      (node (ref "U4") (pin "88") (pinfunction "IO_L42P_GCLK7_88") (pintype "bidirectional"))
    )
    (net (code "173") (name "Net-(U4B-IO_L43N_GCLK4)") (class "Default")
      (node (ref "RA4") (pin "1A") (pinfunction "1A_1A") (pintype "passive"))
      (node (ref "U4") (pin "84") (pinfunction "IO_L43N_GCLK4_84") (pintype "bidirectional"))
    )
    (net (code "174") (name "Net-(U4B-IO_L43P_GCLK5)") (class "Default")
      (node (ref "RA4") (pin "2A") (pinfunction "2A_2A") (pintype "passive"))
      (node (ref "U4") (pin "85") (pinfunction "IO_L43P_GCLK5_85") (pintype "bidirectional"))
    )
    (net (code "175") (name "Net-(U4B-IO_L45N)") (class "Default")
      (node (ref "RA3") (pin "3A") (pinfunction "3A_3A") (pintype "passive"))
      (node (ref "U4") (pin "82") (pinfunction "IO_L45N_82") (pintype "bidirectional"))
    )
    (net (code "176") (name "Net-(U4B-IO_L45P)") (class "Default")
      (node (ref "RA3") (pin "4A") (pinfunction "4A_4A") (pintype "passive"))
      (node (ref "U4") (pin "83") (pinfunction "IO_L45P_83") (pintype "bidirectional"))
    )
    (net (code "177") (name "Net-(U4B-IO_L46N)") (class "Default")
      (node (ref "RA3") (pin "1A") (pinfunction "1A_1A") (pintype "passive"))
      (node (ref "U4") (pin "80") (pinfunction "IO_L46N_80") (pintype "bidirectional"))
    )
    (net (code "178") (name "Net-(U4B-IO_L46P)") (class "Default")
      (node (ref "RA3") (pin "2A") (pinfunction "2A_2A") (pintype "passive"))
      (node (ref "U4") (pin "81") (pinfunction "IO_L46P_81") (pintype "bidirectional"))
    )
    (net (code "179") (name "Net-(U4B-IO_L47N)") (class "Default")
      (node (ref "RA2") (pin "3A") (pinfunction "3A_3A") (pintype "passive"))
      (node (ref "U4") (pin "78") (pinfunction "IO_L47N_78") (pintype "bidirectional"))
    )
    (net (code "180") (name "Net-(U4B-IO_L47P)") (class "Default")
      (node (ref "RA2") (pin "4A") (pinfunction "4A_4A") (pintype "passive"))
      (node (ref "U4") (pin "79") (pinfunction "IO_L47P_79") (pintype "bidirectional"))
    )
    (net (code "181") (name "Net-(U4B-IO_L74N_DOUT_BUSY)") (class "Default")
      (node (ref "RA2") (pin "1A") (pinfunction "1A_1A") (pintype "passive"))
      (node (ref "U4") (pin "74") (pinfunction "IO_L74N_DOUT_BUSY_74") (pintype "bidirectional"))
    )
    (net (code "182") (name "Net-(U4B-IO_L74P_AWAKE)") (class "Default")
      (node (ref "RA2") (pin "2A") (pinfunction "2A_2A") (pintype "passive"))
      (node (ref "U4") (pin "75") (pinfunction "IO_L74P_AWAKE_75") (pintype "bidirectional"))
    )
    (net (code "183") (name "Net-(U4C-IO_L2N_CMPMOSI)") (class "Default")
      (node (ref "RA1") (pin "3A") (pinfunction "3A_3A") (pintype "passive"))
      (node (ref "U4") (pin "66") (pinfunction "IO_L2N_CMPMOSI_66") (pintype "bidirectional"))
    )
    (net (code "184") (name "Net-(U4C-IO_L2P_CMPCLK)") (class "Default")
      (node (ref "RA1") (pin "4A") (pinfunction "4A_4A") (pintype "passive"))
      (node (ref "U4") (pin "67") (pinfunction "IO_L2P_CMPCLK_67") (pintype "bidirectional"))
    )
    (net (code "185") (name "Net-(U4C-IO_L12P_D1_MISO2)") (class "Default")
      (node (ref "RA1") (pin "2A") (pinfunction "2A_2A") (pintype "passive"))
      (node (ref "U4") (pin "62") (pinfunction "IO_L12P_D1_MISO2_62") (pintype "bidirectional"))
    )
    (net (code "186") (name "Net-(U4C-IO_L30P_GCLK1_D13)") (class "Default")
      (node (ref "RA1") (pin "1A") (pinfunction "1A_1A") (pintype "passive"))
      (node (ref "U4") (pin "56") (pinfunction "IO_L30P_GCLK1_D13_56") (pintype "bidirectional"))
    )
    (net (code "187") (name "Net-(U5A-~{WP})") (class "Default")
      (node (ref "SV2") (pin "2") (pinfunction "2_2") (pintype "passive"))
      (node (ref "U5") (pin "3") (pinfunction "~{WP}_3") (pintype "bidirectional"))
    )
    (net (code "188") (name "Net-(U6-V_OUT)") (class "Default")
      (node (ref "C44") (pin "1") (pinfunction "1_1") (pintype "passive"))
      (node (ref "J_1.2") (pin "2") (pinfunction "2_2") (pintype "passive"))
      (node (ref "TP3") (pin "1") (pinfunction "1_1") (pintype "passive"))
      (node (ref "U6") (pin "3") (pinfunction "V_OUT_3") (pintype "power_in"))
    )
    (net (code "189") (name "Net-(X8A-A)") (class "Default")
      (node (ref "R27") (pin "1") (pinfunction "1_1") (pintype "passive"))
      (node (ref "X8") (pin "11") (pinfunction "A_11") (pintype "bidirectional"))
    )
    (net (code "190") (name "Net-(X8B-A)") (class "Default")
      (node (ref "R28") (pin "1") (pinfunction "1_1") (pintype "passive"))
      (node (ref "X8") (pin "9") (pinfunction "A_9") (pintype "bidirectional"))
    )
    (net (code "191") (name "OSC0") (class "Default")
      (node (ref "R12") (pin "2") (pinfunction "2_2") (pintype "passive"))
      (node (ref "U1") (pin "88") (pinfunction "OSC0_88") (pintype "bidirectional"))
    )
    (net (code "192") (name "OSC1") (class "Default")
      (node (ref "C50") (pin "1") (pinfunction "1_1") (pintype "passive"))
      (node (ref "Q1") (pin "3") (pinfunction "XTALB_3") (pintype "passive"))
      (node (ref "U1") (pin "89") (pinfunction "OSC1_89") (pintype "bidirectional"))
    )
    (net (code "193") (name "PETAL_III_1") (class "Default")
      (node (ref "RA24") (pin "1A") (pinfunction "1A_1A") (pintype "passive"))
      (node (ref "X13") (pin "5") (pinfunction "5_5") (pintype "passive"))
      (node (ref "X3") (pin "11") (pinfunction "11_11") (pintype "bidirectional"))
    )
    (net (code "194") (name "PETAL_III_2") (class "Default")
      (node (ref "RA24") (pin "2A") (pinfunction "2A_2A") (pintype "passive"))
      (node (ref "X13") (pin "6") (pinfunction "6_6") (pintype "passive"))
      (node (ref "X3") (pin "12") (pinfunction "12_12") (pintype "bidirectional"))
    )
    (net (code "195") (name "PETAL_III_3") (class "Default")
      (node (ref "RA24") (pin "3A") (pinfunction "3A_3A") (pintype "passive"))
      (node (ref "X13") (pin "7") (pinfunction "7_7") (pintype "passive"))
      (node (ref "X3") (pin "13") (pinfunction "13_13") (pintype "bidirectional"))
    )
    (net (code "196") (name "PETAL_III_4") (class "Default")
      (node (ref "RA24") (pin "4A") (pinfunction "4A_4A") (pintype "passive"))
      (node (ref "X13") (pin "8") (pinfunction "8_8") (pintype "passive"))
      (node (ref "X3") (pin "14") (pinfunction "14_14") (pintype "bidirectional"))
    )
    (net (code "197") (name "PETAL_III_5") (class "Default")
      (node (ref "RA25") (pin "1A") (pinfunction "1A_1A") (pintype "passive"))
      (node (ref "X13") (pin "9") (pinfunction "9_9") (pintype "passive"))
      (node (ref "X3") (pin "15") (pinfunction "15_15") (pintype "bidirectional"))
    )
    (net (code "198") (name "PETAL_III_6") (class "Default")
      (node (ref "RA25") (pin "2A") (pinfunction "2A_2A") (pintype "passive"))
      (node (ref "X13") (pin "10") (pinfunction "10_10") (pintype "passive"))
      (node (ref "X3") (pin "16") (pinfunction "16_16") (pintype "bidirectional"))
    )
    (net (code "199") (name "PETAL_III_7") (class "Default")
      (node (ref "RA25") (pin "3A") (pinfunction "3A_3A") (pintype "passive"))
      (node (ref "X13") (pin "11") (pinfunction "11_11") (pintype "passive"))
      (node (ref "X3") (pin "18") (pinfunction "18_18") (pintype "bidirectional"))
    )
    (net (code "200") (name "PETAL_III_8") (class "Default")
      (node (ref "RA25") (pin "4A") (pinfunction "4A_4A") (pintype "passive"))
      (node (ref "X13") (pin "12") (pinfunction "12_12") (pintype "passive"))
      (node (ref "X3") (pin "19") (pinfunction "19_19") (pintype "bidirectional"))
    )
    (net (code "201") (name "PETAL_III_9") (class "Default")
      (node (ref "RA26") (pin "1A") (pinfunction "1A_1A") (pintype "passive"))
      (node (ref "X13") (pin "13") (pinfunction "13_13") (pintype "passive"))
      (node (ref "X3") (pin "20") (pinfunction "20_20") (pintype "bidirectional"))
    )
    (net (code "202") (name "PETAL_III_10") (class "Default")
      (node (ref "RA26") (pin "2A") (pinfunction "2A_2A") (pintype "passive"))
      (node (ref "X13") (pin "14") (pinfunction "14_14") (pintype "passive"))
      (node (ref "X3") (pin "21") (pinfunction "21_21") (pintype "bidirectional"))
    )
    (net (code "203") (name "PETAL_III_11") (class "Default")
      (node (ref "RA26") (pin "3A") (pinfunction "3A_3A") (pintype "passive"))
      (node (ref "X13") (pin "15") (pinfunction "15_15") (pintype "passive"))
      (node (ref "X3") (pin "23") (pinfunction "23_23") (pintype "bidirectional"))
    )
    (net (code "204") (name "PETAL_III_12") (class "Default")
      (node (ref "RA26") (pin "4A") (pinfunction "4A_4A") (pintype "passive"))
      (node (ref "X13") (pin "16") (pinfunction "16_16") (pintype "passive"))
      (node (ref "X3") (pin "24") (pinfunction "24_24") (pintype "bidirectional"))
    )
    (net (code "205") (name "PETAL_III_13") (class "Default")
      (node (ref "RA27") (pin "1A") (pinfunction "1A_1A") (pintype "passive"))
      (node (ref "X13") (pin "17") (pinfunction "17_17") (pintype "passive"))
      (node (ref "X3") (pin "25") (pinfunction "25_25") (pintype "bidirectional"))
    )
    (net (code "206") (name "PETAL_III_14") (class "Default")
      (node (ref "RA27") (pin "2A") (pinfunction "2A_2A") (pintype "passive"))
      (node (ref "X13") (pin "18") (pinfunction "18_18") (pintype "passive"))
      (node (ref "X3") (pin "26") (pinfunction "26_26") (pintype "bidirectional"))
    )
    (net (code "207") (name "PETAL_III_15") (class "Default")
      (node (ref "RA27") (pin "3A") (pinfunction "3A_3A") (pintype "passive"))
      (node (ref "X13") (pin "19") (pinfunction "19_19") (pintype "passive"))
      (node (ref "X3") (pin "27") (pinfunction "27_27") (pintype "bidirectional"))
    )
    (net (code "208") (name "PETAL_III_16") (class "Default")
      (node (ref "RA27") (pin "4A") (pinfunction "4A_4A") (pintype "passive"))
      (node (ref "X13") (pin "20") (pinfunction "20_20") (pintype "passive"))
      (node (ref "X3") (pin "28") (pinfunction "28_28") (pintype "bidirectional"))
    )
    (net (code "209") (name "PETAL_III_17") (class "Default")
      (node (ref "RA28") (pin "1A") (pinfunction "1A_1A") (pintype "passive"))
      (node (ref "X13") (pin "21") (pinfunction "21_21") (pintype "passive"))
      (node (ref "X3") (pin "30") (pinfunction "30_30") (pintype "bidirectional"))
    )
    (net (code "210") (name "PETAL_III_18") (class "Default")
      (node (ref "RA28") (pin "2A") (pinfunction "2A_2A") (pintype "passive"))
      (node (ref "X13") (pin "22") (pinfunction "22_22") (pintype "passive"))
      (node (ref "X3") (pin "31") (pinfunction "31_31") (pintype "bidirectional"))
    )
    (net (code "211") (name "PETAL_III_19") (class "Default")
      (node (ref "RA28") (pin "3A") (pinfunction "3A_3A") (pintype "passive"))
      (node (ref "X13") (pin "23") (pinfunction "23_23") (pintype "passive"))
      (node (ref "X3") (pin "32") (pinfunction "32_32") (pintype "bidirectional"))
    )
    (net (code "212") (name "PETAL_III_20") (class "Default")
      (node (ref "RA28") (pin "4A") (pinfunction "4A_4A") (pintype "passive"))
      (node (ref "X13") (pin "24") (pinfunction "24_24") (pintype "passive"))
      (node (ref "X3") (pin "33") (pinfunction "33_33") (pintype "bidirectional"))
    )
    (net (code "213") (name "PETAL_III_21") (class "Default")
      (node (ref "RA29") (pin "1A") (pinfunction "1A_1A") (pintype "passive"))
      (node (ref "X13") (pin "25") (pinfunction "25_25") (pintype "passive"))
      (node (ref "X3") (pin "35") (pinfunction "35_35") (pintype "bidirectional"))
    )
    (net (code "214") (name "PETAL_III_22") (class "Default")
      (node (ref "RA29") (pin "2A") (pinfunction "2A_2A") (pintype "passive"))
      (node (ref "X13") (pin "26") (pinfunction "26_26") (pintype "passive"))
      (node (ref "X3") (pin "36") (pinfunction "36_36") (pintype "bidirectional"))
    )
    (net (code "215") (name "PETAL_III_23") (class "Default")
      (node (ref "RA29") (pin "3A") (pinfunction "3A_3A") (pintype "passive"))
      (node (ref "X13") (pin "27") (pinfunction "27_27") (pintype "passive"))
      (node (ref "X3") (pin "37") (pinfunction "37_37") (pintype "bidirectional"))
    )
    (net (code "216") (name "PETAL_III_24") (class "Default")
      (node (ref "RA29") (pin "4A") (pinfunction "4A_4A") (pintype "passive"))
      (node (ref "X13") (pin "28") (pinfunction "28_28") (pintype "passive"))
      (node (ref "X3") (pin "38") (pinfunction "38_38") (pintype "bidirectional"))
    )
    (net (code "217") (name "PETAL_III_25") (class "Default")
      (node (ref "RA30") (pin "1A") (pinfunction "1A_1A") (pintype "passive"))
      (node (ref "X13") (pin "29") (pinfunction "29_29") (pintype "passive"))
      (node (ref "X3") (pin "39") (pinfunction "39_39") (pintype "bidirectional"))
    )
    (net (code "218") (name "PETAL_III_26") (class "Default")
      (node (ref "RA30") (pin "2A") (pinfunction "2A_2A") (pintype "passive"))
      (node (ref "X13") (pin "30") (pinfunction "30_30") (pintype "passive"))
      (node (ref "X3") (pin "40") (pinfunction "40_40") (pintype "bidirectional"))
    )
    (net (code "219") (name "PETAL_II_1") (class "Default")
      (node (ref "RA17") (pin "1A") (pinfunction "1A_1A") (pintype "passive"))
      (node (ref "X12") (pin "5") (pinfunction "5_5") (pintype "passive"))
      (node (ref "X2") (pin "11") (pinfunction "11_11") (pintype "bidirectional"))
    )
    (net (code "220") (name "PETAL_II_2") (class "Default")
      (node (ref "RA17") (pin "2A") (pinfunction "2A_2A") (pintype "passive"))
      (node (ref "X12") (pin "6") (pinfunction "6_6") (pintype "passive"))
      (node (ref "X2") (pin "12") (pinfunction "12_12") (pintype "bidirectional"))
    )
    (net (code "221") (name "PETAL_II_3") (class "Default")
      (node (ref "RA17") (pin "3A") (pinfunction "3A_3A") (pintype "passive"))
      (node (ref "X12") (pin "7") (pinfunction "7_7") (pintype "passive"))
      (node (ref "X2") (pin "13") (pinfunction "13_13") (pintype "bidirectional"))
    )
    (net (code "222") (name "PETAL_II_4") (class "Default")
      (node (ref "RA17") (pin "4A") (pinfunction "4A_4A") (pintype "passive"))
      (node (ref "X12") (pin "8") (pinfunction "8_8") (pintype "passive"))
      (node (ref "X2") (pin "14") (pinfunction "14_14") (pintype "bidirectional"))
    )
    (net (code "223") (name "PETAL_II_5") (class "Default")
      (node (ref "RA18") (pin "1A") (pinfunction "1A_1A") (pintype "passive"))
      (node (ref "X12") (pin "9") (pinfunction "9_9") (pintype "passive"))
      (node (ref "X2") (pin "15") (pinfunction "15_15") (pintype "bidirectional"))
    )
    (net (code "224") (name "PETAL_II_6") (class "Default")
      (node (ref "RA18") (pin "2A") (pinfunction "2A_2A") (pintype "passive"))
      (node (ref "X12") (pin "10") (pinfunction "10_10") (pintype "passive"))
      (node (ref "X2") (pin "16") (pinfunction "16_16") (pintype "bidirectional"))
    )
    (net (code "225") (name "PETAL_II_7") (class "Default")
      (node (ref "RA18") (pin "3A") (pinfunction "3A_3A") (pintype "passive"))
      (node (ref "X12") (pin "11") (pinfunction "11_11") (pintype "passive"))
      (node (ref "X2") (pin "18") (pinfunction "18_18") (pintype "bidirectional"))
    )
    (net (code "226") (name "PETAL_II_8") (class "Default")
      (node (ref "RA18") (pin "4A") (pinfunction "4A_4A") (pintype "passive"))
      (node (ref "X12") (pin "12") (pinfunction "12_12") (pintype "passive"))
      (node (ref "X2") (pin "19") (pinfunction "19_19") (pintype "bidirectional"))
    )
    (net (code "227") (name "PETAL_II_9") (class "Default")
      (node (ref "RA19") (pin "1A") (pinfunction "1A_1A") (pintype "passive"))
      (node (ref "X12") (pin "13") (pinfunction "13_13") (pintype "passive"))
      (node (ref "X2") (pin "20") (pinfunction "20_20") (pintype "bidirectional"))
    )
    (net (code "228") (name "PETAL_II_10") (class "Default")
      (node (ref "RA19") (pin "2A") (pinfunction "2A_2A") (pintype "passive"))
      (node (ref "X12") (pin "14") (pinfunction "14_14") (pintype "passive"))
      (node (ref "X2") (pin "21") (pinfunction "21_21") (pintype "bidirectional"))
    )
    (net (code "229") (name "PETAL_II_11") (class "Default")
      (node (ref "RA20") (pin "1B") (pinfunction "1B_1B") (pintype "passive"))
      (node (ref "X12") (pin "15") (pinfunction "15_15") (pintype "passive"))
      (node (ref "X2") (pin "23") (pinfunction "23_23") (pintype "bidirectional"))
    )
    (net (code "230") (name "PETAL_II_12") (class "Default")
      (node (ref "RA20") (pin "2B") (pinfunction "2B_2B") (pintype "passive"))
      (node (ref "X12") (pin "16") (pinfunction "16_16") (pintype "passive"))
      (node (ref "X2") (pin "24") (pinfunction "24_24") (pintype "bidirectional"))
    )
    (net (code "231") (name "PETAL_II_13") (class "Default")
      (node (ref "RA20") (pin "3B") (pinfunction "3B_3B") (pintype "passive"))
      (node (ref "X12") (pin "17") (pinfunction "17_17") (pintype "passive"))
      (node (ref "X2") (pin "25") (pinfunction "25_25") (pintype "bidirectional"))
    )
    (net (code "232") (name "PETAL_II_14") (class "Default")
      (node (ref "RA20") (pin "4B") (pinfunction "4B_4B") (pintype "passive"))
      (node (ref "X12") (pin "18") (pinfunction "18_18") (pintype "passive"))
      (node (ref "X2") (pin "26") (pinfunction "26_26") (pintype "bidirectional"))
    )
    (net (code "233") (name "PETAL_II_15") (class "Default")
      (node (ref "RA21") (pin "1B") (pinfunction "1B_1B") (pintype "passive"))
      (node (ref "X12") (pin "19") (pinfunction "19_19") (pintype "passive"))
      (node (ref "X2") (pin "27") (pinfunction "27_27") (pintype "bidirectional"))
    )
    (net (code "234") (name "PETAL_II_16") (class "Default")
      (node (ref "RA21") (pin "2B") (pinfunction "2B_2B") (pintype "passive"))
      (node (ref "X12") (pin "20") (pinfunction "20_20") (pintype "passive"))
      (node (ref "X2") (pin "28") (pinfunction "28_28") (pintype "bidirectional"))
    )
    (net (code "235") (name "PETAL_II_17") (class "Default")
      (node (ref "RA21") (pin "3B") (pinfunction "3B_3B") (pintype "passive"))
      (node (ref "X12") (pin "21") (pinfunction "21_21") (pintype "passive"))
      (node (ref "X2") (pin "30") (pinfunction "30_30") (pintype "bidirectional"))
    )
    (net (code "236") (name "PETAL_II_18") (class "Default")
      (node (ref "RA21") (pin "4B") (pinfunction "4B_4B") (pintype "passive"))
      (node (ref "X12") (pin "22") (pinfunction "22_22") (pintype "passive"))
      (node (ref "X2") (pin "31") (pinfunction "31_31") (pintype "bidirectional"))
    )
    (net (code "237") (name "PETAL_II_19") (class "Default")
      (node (ref "RA22") (pin "1A") (pinfunction "1A_1A") (pintype "passive"))
      (node (ref "X12") (pin "23") (pinfunction "23_23") (pintype "passive"))
      (node (ref "X2") (pin "32") (pinfunction "32_32") (pintype "bidirectional"))
    )
    (net (code "238") (name "PETAL_II_20") (class "Default")
      (node (ref "RA22") (pin "2A") (pinfunction "2A_2A") (pintype "passive"))
      (node (ref "X12") (pin "24") (pinfunction "24_24") (pintype "passive"))
      (node (ref "X2") (pin "33") (pinfunction "33_33") (pintype "bidirectional"))
    )
    (net (code "239") (name "PETAL_II_21") (class "Default")
      (node (ref "RA22") (pin "3A") (pinfunction "3A_3A") (pintype "passive"))
      (node (ref "X12") (pin "25") (pinfunction "25_25") (pintype "passive"))
      (node (ref "X2") (pin "35") (pinfunction "35_35") (pintype "bidirectional"))
    )
    (net (code "240") (name "PETAL_II_22") (class "Default")
      (node (ref "RA22") (pin "4A") (pinfunction "4A_4A") (pintype "passive"))
      (node (ref "X12") (pin "26") (pinfunction "26_26") (pintype "passive"))
      (node (ref "X2") (pin "36") (pinfunction "36_36") (pintype "bidirectional"))
    )
    (net (code "241") (name "PETAL_II_23") (class "Default")
      (node (ref "RA23") (pin "1A") (pinfunction "1A_1A") (pintype "passive"))
      (node (ref "X12") (pin "27") (pinfunction "27_27") (pintype "passive"))
      (node (ref "X2") (pin "37") (pinfunction "37_37") (pintype "bidirectional"))
    )
    (net (code "242") (name "PETAL_II_24") (class "Default")
      (node (ref "RA23") (pin "2A") (pinfunction "2A_2A") (pintype "passive"))
      (node (ref "X12") (pin "28") (pinfunction "28_28") (pintype "passive"))
      (node (ref "X2") (pin "38") (pinfunction "38_38") (pintype "bidirectional"))
    )
    (net (code "243") (name "PETAL_II_25") (class "Default")
      (node (ref "RA23") (pin "3A") (pinfunction "3A_3A") (pintype "passive"))
      (node (ref "X12") (pin "29") (pinfunction "29_29") (pintype "passive"))
      (node (ref "X2") (pin "39") (pinfunction "39_39") (pintype "bidirectional"))
    )
    (net (code "244") (name "PETAL_II_26") (class "Default")
      (node (ref "RA23") (pin "4A") (pinfunction "4A_4A") (pintype "passive"))
      (node (ref "X12") (pin "30") (pinfunction "30_30") (pintype "passive"))
      (node (ref "X2") (pin "40") (pinfunction "40_40") (pintype "bidirectional"))
    )
    (net (code "245") (name "PETAL_IV_1") (class "Default")
      (node (ref "RA31") (pin "1A") (pinfunction "1A_1A") (pintype "passive"))
      (node (ref "X4") (pin "11") (pinfunction "11_11") (pintype "bidirectional"))
      (node (ref "X7") (pin "5") (pinfunction "5_5") (pintype "passive"))
    )
    (net (code "246") (name "PETAL_IV_2") (class "Default")
      (node (ref "RA31") (pin "2A") (pinfunction "2A_2A") (pintype "passive"))
      (node (ref "X4") (pin "12") (pinfunction "12_12") (pintype "bidirectional"))
      (node (ref "X7") (pin "6") (pinfunction "6_6") (pintype "passive"))
    )
    (net (code "247") (name "PETAL_IV_3") (class "Default")
      (node (ref "RA31") (pin "3A") (pinfunction "3A_3A") (pintype "passive"))
      (node (ref "X4") (pin "13") (pinfunction "13_13") (pintype "bidirectional"))
      (node (ref "X7") (pin "7") (pinfunction "7_7") (pintype "passive"))
    )
    (net (code "248") (name "PETAL_IV_4") (class "Default")
      (node (ref "RA31") (pin "4A") (pinfunction "4A_4A") (pintype "passive"))
      (node (ref "X4") (pin "14") (pinfunction "14_14") (pintype "bidirectional"))
      (node (ref "X7") (pin "8") (pinfunction "8_8") (pintype "passive"))
    )
    (net (code "249") (name "PETAL_IV_5") (class "Default")
      (node (ref "RA32") (pin "1A") (pinfunction "1A_1A") (pintype "passive"))
      (node (ref "X4") (pin "15") (pinfunction "15_15") (pintype "bidirectional"))
      (node (ref "X7") (pin "9") (pinfunction "9_9") (pintype "passive"))
    )
    (net (code "250") (name "PETAL_IV_6") (class "Default")
      (node (ref "RA32") (pin "2A") (pinfunction "2A_2A") (pintype "passive"))
      (node (ref "X4") (pin "16") (pinfunction "16_16") (pintype "bidirectional"))
      (node (ref "X7") (pin "10") (pinfunction "10_10") (pintype "passive"))
    )
    (net (code "251") (name "PETAL_IV_7") (class "Default")
      (node (ref "RA32") (pin "3A") (pinfunction "3A_3A") (pintype "passive"))
      (node (ref "X4") (pin "18") (pinfunction "18_18") (pintype "bidirectional"))
      (node (ref "X7") (pin "11") (pinfunction "11_11") (pintype "passive"))
    )
    (net (code "252") (name "PETAL_IV_8") (class "Default")
      (node (ref "RA32") (pin "4A") (pinfunction "4A_4A") (pintype "passive"))
      (node (ref "X4") (pin "19") (pinfunction "19_19") (pintype "bidirectional"))
      (node (ref "X7") (pin "12") (pinfunction "12_12") (pintype "passive"))
    )
    (net (code "253") (name "PETAL_IV_9") (class "Default")
      (node (ref "RA33") (pin "1A") (pinfunction "1A_1A") (pintype "passive"))
      (node (ref "X4") (pin "20") (pinfunction "20_20") (pintype "bidirectional"))
      (node (ref "X7") (pin "13") (pinfunction "13_13") (pintype "passive"))
    )
    (net (code "254") (name "PETAL_IV_10") (class "Default")
      (node (ref "RA33") (pin "2A") (pinfunction "2A_2A") (pintype "passive"))
      (node (ref "X4") (pin "21") (pinfunction "21_21") (pintype "bidirectional"))
      (node (ref "X7") (pin "14") (pinfunction "14_14") (pintype "passive"))
    )
    (net (code "255") (name "PETAL_IV_11") (class "Default")
      (node (ref "RA33") (pin "3A") (pinfunction "3A_3A") (pintype "passive"))
      (node (ref "X4") (pin "23") (pinfunction "23_23") (pintype "bidirectional"))
      (node (ref "X7") (pin "15") (pinfunction "15_15") (pintype "passive"))
    )
    (net (code "256") (name "PETAL_IV_12") (class "Default")
      (node (ref "RA33") (pin "4A") (pinfunction "4A_4A") (pintype "passive"))
      (node (ref "X4") (pin "24") (pinfunction "24_24") (pintype "bidirectional"))
      (node (ref "X7") (pin "16") (pinfunction "16_16") (pintype "passive"))
    )
    (net (code "257") (name "PETAL_IV_13") (class "Default")
      (node (ref "RA34") (pin "1A") (pinfunction "1A_1A") (pintype "passive"))
      (node (ref "X4") (pin "25") (pinfunction "25_25") (pintype "bidirectional"))
      (node (ref "X7") (pin "17") (pinfunction "17_17") (pintype "passive"))
    )
    (net (code "258") (name "PETAL_IV_14") (class "Default")
      (node (ref "RA34") (pin "2A") (pinfunction "2A_2A") (pintype "passive"))
      (node (ref "X4") (pin "26") (pinfunction "26_26") (pintype "bidirectional"))
      (node (ref "X7") (pin "18") (pinfunction "18_18") (pintype "passive"))
    )
    (net (code "259") (name "PETAL_IV_15") (class "Default")
      (node (ref "RA34") (pin "3A") (pinfunction "3A_3A") (pintype "passive"))
      (node (ref "X4") (pin "27") (pinfunction "27_27") (pintype "bidirectional"))
      (node (ref "X7") (pin "19") (pinfunction "19_19") (pintype "passive"))
    )
    (net (code "260") (name "PETAL_IV_16") (class "Default")
      (node (ref "RA34") (pin "4A") (pinfunction "4A_4A") (pintype "passive"))
      (node (ref "X4") (pin "28") (pinfunction "28_28") (pintype "bidirectional"))
      (node (ref "X7") (pin "20") (pinfunction "20_20") (pintype "passive"))
    )
    (net (code "261") (name "PETAL_IV_17") (class "Default")
      (node (ref "RA35") (pin "1A") (pinfunction "1A_1A") (pintype "passive"))
      (node (ref "X4") (pin "30") (pinfunction "30_30") (pintype "bidirectional"))
      (node (ref "X7") (pin "21") (pinfunction "21_21") (pintype "passive"))
    )
    (net (code "262") (name "PETAL_IV_18") (class "Default")
      (node (ref "RA35") (pin "2A") (pinfunction "2A_2A") (pintype "passive"))
      (node (ref "X4") (pin "31") (pinfunction "31_31") (pintype "bidirectional"))
      (node (ref "X7") (pin "22") (pinfunction "22_22") (pintype "passive"))
    )
    (net (code "263") (name "PETAL_IV_19") (class "Default")
      (node (ref "RA35") (pin "3A") (pinfunction "3A_3A") (pintype "passive"))
      (node (ref "X4") (pin "32") (pinfunction "32_32") (pintype "bidirectional"))
      (node (ref "X7") (pin "23") (pinfunction "23_23") (pintype "passive"))
    )
    (net (code "264") (name "PETAL_IV_20") (class "Default")
      (node (ref "RA35") (pin "4A") (pinfunction "4A_4A") (pintype "passive"))
      (node (ref "X4") (pin "33") (pinfunction "33_33") (pintype "bidirectional"))
      (node (ref "X7") (pin "24") (pinfunction "24_24") (pintype "passive"))
    )
    (net (code "265") (name "PETAL_IV_21") (class "Default")
      (node (ref "RA36") (pin "1A") (pinfunction "1A_1A") (pintype "passive"))
      (node (ref "X4") (pin "35") (pinfunction "35_35") (pintype "bidirectional"))
      (node (ref "X7") (pin "25") (pinfunction "25_25") (pintype "passive"))
    )
    (net (code "266") (name "PETAL_IV_22") (class "Default")
      (node (ref "RA36") (pin "2A") (pinfunction "2A_2A") (pintype "passive"))
      (node (ref "X4") (pin "36") (pinfunction "36_36") (pintype "bidirectional"))
      (node (ref "X7") (pin "26") (pinfunction "26_26") (pintype "passive"))
    )
    (net (code "267") (name "PETAL_IV_23") (class "Default")
      (node (ref "RA36") (pin "3A") (pinfunction "3A_3A") (pintype "passive"))
      (node (ref "X4") (pin "37") (pinfunction "37_37") (pintype "bidirectional"))
      (node (ref "X7") (pin "27") (pinfunction "27_27") (pintype "passive"))
    )
    (net (code "268") (name "PETAL_IV_24") (class "Default")
      (node (ref "RA36") (pin "4A") (pinfunction "4A_4A") (pintype "passive"))
      (node (ref "X4") (pin "38") (pinfunction "38_38") (pintype "bidirectional"))
      (node (ref "X7") (pin "28") (pinfunction "28_28") (pintype "passive"))
    )
    (net (code "269") (name "PETAL_IV_25") (class "Default")
      (node (ref "RA37") (pin "1A") (pinfunction "1A_1A") (pintype "passive"))
      (node (ref "X4") (pin "39") (pinfunction "39_39") (pintype "bidirectional"))
      (node (ref "X7") (pin "29") (pinfunction "29_29") (pintype "passive"))
    )
    (net (code "270") (name "PETAL_IV_26") (class "Default")
      (node (ref "RA37") (pin "2A") (pinfunction "2A_2A") (pintype "passive"))
      (node (ref "X4") (pin "40") (pinfunction "40_40") (pintype "bidirectional"))
      (node (ref "X7") (pin "30") (pinfunction "30_30") (pintype "passive"))
    )
    (net (code "271") (name "PETAL_I_1") (class "Default")
      (node (ref "RA10") (pin "1A") (pinfunction "1A_1A") (pintype "passive"))
      (node (ref "X1") (pin "11") (pinfunction "11_11") (pintype "bidirectional"))
      (node (ref "X11") (pin "5") (pinfunction "5_5") (pintype "passive"))
    )
    (net (code "272") (name "PETAL_I_2") (class "Default")
      (node (ref "RA10") (pin "2A") (pinfunction "2A_2A") (pintype "passive"))
      (node (ref "X1") (pin "12") (pinfunction "12_12") (pintype "bidirectional"))
      (node (ref "X11") (pin "6") (pinfunction "6_6") (pintype "passive"))
    )
    (net (code "273") (name "PETAL_I_3") (class "Default")
      (node (ref "RA10") (pin "3A") (pinfunction "3A_3A") (pintype "passive"))
      (node (ref "X1") (pin "13") (pinfunction "13_13") (pintype "bidirectional"))
      (node (ref "X11") (pin "7") (pinfunction "7_7") (pintype "passive"))
    )
    (net (code "274") (name "PETAL_I_4") (class "Default")
      (node (ref "RA10") (pin "4A") (pinfunction "4A_4A") (pintype "passive"))
      (node (ref "X1") (pin "14") (pinfunction "14_14") (pintype "bidirectional"))
      (node (ref "X11") (pin "8") (pinfunction "8_8") (pintype "passive"))
    )
    (net (code "275") (name "PETAL_I_5") (class "Default")
      (node (ref "RA11") (pin "1A") (pinfunction "1A_1A") (pintype "passive"))
      (node (ref "X1") (pin "15") (pinfunction "15_15") (pintype "bidirectional"))
      (node (ref "X11") (pin "9") (pinfunction "9_9") (pintype "passive"))
    )
    (net (code "276") (name "PETAL_I_6") (class "Default")
      (node (ref "RA11") (pin "2A") (pinfunction "2A_2A") (pintype "passive"))
      (node (ref "X1") (pin "16") (pinfunction "16_16") (pintype "bidirectional"))
      (node (ref "X11") (pin "10") (pinfunction "10_10") (pintype "passive"))
    )
    (net (code "277") (name "PETAL_I_7") (class "Default")
      (node (ref "RA11") (pin "3A") (pinfunction "3A_3A") (pintype "passive"))
      (node (ref "X1") (pin "18") (pinfunction "18_18") (pintype "bidirectional"))
      (node (ref "X11") (pin "11") (pinfunction "11_11") (pintype "passive"))
    )
    (net (code "278") (name "PETAL_I_8") (class "Default")
      (node (ref "RA11") (pin "4A") (pinfunction "4A_4A") (pintype "passive"))
      (node (ref "X1") (pin "19") (pinfunction "19_19") (pintype "bidirectional"))
      (node (ref "X11") (pin "12") (pinfunction "12_12") (pintype "passive"))
    )
    (net (code "279") (name "PETAL_I_9") (class "Default")
      (node (ref "RA12") (pin "1A") (pinfunction "1A_1A") (pintype "passive"))
      (node (ref "X1") (pin "20") (pinfunction "20_20") (pintype "bidirectional"))
      (node (ref "X11") (pin "13") (pinfunction "13_13") (pintype "passive"))
    )
    (net (code "280") (name "PETAL_I_10") (class "Default")
      (node (ref "RA12") (pin "2A") (pinfunction "2A_2A") (pintype "passive"))
      (node (ref "X1") (pin "21") (pinfunction "21_21") (pintype "bidirectional"))
      (node (ref "X11") (pin "14") (pinfunction "14_14") (pintype "passive"))
    )
    (net (code "281") (name "PETAL_I_11") (class "Default")
      (node (ref "RA13") (pin "1A") (pinfunction "1A_1A") (pintype "passive"))
      (node (ref "X1") (pin "23") (pinfunction "23_23") (pintype "bidirectional"))
      (node (ref "X11") (pin "15") (pinfunction "15_15") (pintype "passive"))
    )
    (net (code "282") (name "PETAL_I_12") (class "Default")
      (node (ref "RA13") (pin "2A") (pinfunction "2A_2A") (pintype "passive"))
      (node (ref "X1") (pin "24") (pinfunction "24_24") (pintype "bidirectional"))
      (node (ref "X11") (pin "16") (pinfunction "16_16") (pintype "passive"))
    )
    (net (code "283") (name "PETAL_I_13") (class "Default")
      (node (ref "RA13") (pin "3A") (pinfunction "3A_3A") (pintype "passive"))
      (node (ref "X1") (pin "25") (pinfunction "25_25") (pintype "bidirectional"))
      (node (ref "X11") (pin "17") (pinfunction "17_17") (pintype "passive"))
    )
    (net (code "284") (name "PETAL_I_14") (class "Default")
      (node (ref "RA13") (pin "4A") (pinfunction "4A_4A") (pintype "passive"))
      (node (ref "X1") (pin "26") (pinfunction "26_26") (pintype "bidirectional"))
      (node (ref "X11") (pin "18") (pinfunction "18_18") (pintype "passive"))
    )
    (net (code "285") (name "PETAL_I_15") (class "Default")
      (node (ref "RA14") (pin "1A") (pinfunction "1A_1A") (pintype "passive"))
      (node (ref "X1") (pin "27") (pinfunction "27_27") (pintype "bidirectional"))
      (node (ref "X11") (pin "19") (pinfunction "19_19") (pintype "passive"))
    )
    (net (code "286") (name "PETAL_I_16") (class "Default")
      (node (ref "RA14") (pin "2A") (pinfunction "2A_2A") (pintype "passive"))
      (node (ref "X1") (pin "28") (pinfunction "28_28") (pintype "bidirectional"))
      (node (ref "X11") (pin "20") (pinfunction "20_20") (pintype "passive"))
    )
    (net (code "287") (name "PETAL_I_17") (class "Default")
      (node (ref "RA14") (pin "3A") (pinfunction "3A_3A") (pintype "passive"))
      (node (ref "X1") (pin "30") (pinfunction "30_30") (pintype "bidirectional"))
      (node (ref "X11") (pin "21") (pinfunction "21_21") (pintype "passive"))
    )
    (net (code "288") (name "PETAL_I_18") (class "Default")
      (node (ref "RA14") (pin "4A") (pinfunction "4A_4A") (pintype "passive"))
      (node (ref "X1") (pin "31") (pinfunction "31_31") (pintype "bidirectional"))
      (node (ref "X11") (pin "22") (pinfunction "22_22") (pintype "passive"))
    )
    (net (code "289") (name "PETAL_I_19") (class "Default")
      (node (ref "RA15") (pin "1A") (pinfunction "1A_1A") (pintype "passive"))
      (node (ref "X1") (pin "32") (pinfunction "32_32") (pintype "bidirectional"))
      (node (ref "X11") (pin "23") (pinfunction "23_23") (pintype "passive"))
    )
    (net (code "290") (name "PETAL_I_20") (class "Default")
      (node (ref "RA15") (pin "2A") (pinfunction "2A_2A") (pintype "passive"))
      (node (ref "X1") (pin "33") (pinfunction "33_33") (pintype "bidirectional"))
      (node (ref "X11") (pin "24") (pinfunction "24_24") (pintype "passive"))
    )
    (net (code "291") (name "PETAL_I_21") (class "Default")
      (node (ref "RA15") (pin "3A") (pinfunction "3A_3A") (pintype "passive"))
      (node (ref "X1") (pin "35") (pinfunction "35_35") (pintype "bidirectional"))
      (node (ref "X11") (pin "25") (pinfunction "25_25") (pintype "passive"))
    )
    (net (code "292") (name "PETAL_I_22") (class "Default")
      (node (ref "RA15") (pin "4A") (pinfunction "4A_4A") (pintype "passive"))
      (node (ref "X1") (pin "36") (pinfunction "36_36") (pintype "bidirectional"))
      (node (ref "X11") (pin "26") (pinfunction "26_26") (pintype "passive"))
    )
    (net (code "293") (name "PETAL_I_23") (class "Default")
      (node (ref "RA16") (pin "1A") (pinfunction "1A_1A") (pintype "passive"))
      (node (ref "X1") (pin "37") (pinfunction "37_37") (pintype "bidirectional"))
      (node (ref "X11") (pin "27") (pinfunction "27_27") (pintype "passive"))
    )
    (net (code "294") (name "PETAL_I_24") (class "Default")
      (node (ref "RA16") (pin "2A") (pinfunction "2A_2A") (pintype "passive"))
      (node (ref "X1") (pin "38") (pinfunction "38_38") (pintype "bidirectional"))
      (node (ref "X11") (pin "28") (pinfunction "28_28") (pintype "passive"))
    )
    (net (code "295") (name "PETAL_I_25") (class "Default")
      (node (ref "RA16") (pin "3A") (pinfunction "3A_3A") (pintype "passive"))
      (node (ref "X1") (pin "39") (pinfunction "39_39") (pintype "bidirectional"))
      (node (ref "X11") (pin "29") (pinfunction "29_29") (pintype "passive"))
    )
    (net (code "296") (name "PETAL_I_26") (class "Default")
      (node (ref "RA16") (pin "4A") (pinfunction "4A_4A") (pintype "passive"))
      (node (ref "X1") (pin "40") (pinfunction "40_40") (pintype "bidirectional"))
      (node (ref "X11") (pin "30") (pinfunction "30_30") (pintype "passive"))
    )
    (net (code "297") (name "PF0_ETH") (class "Default")
      (node (ref "T5") (pin "1") (pinfunction "B_1") (pintype "input"))
      (node (ref "TP24") (pin "1") (pinfunction "1_1") (pintype "passive"))
      (node (ref "U1") (pin "42") (pinfunction "PF0_42") (pintype "bidirectional"))
    )
    (net (code "298") (name "PF1_LEDR") (class "Default")
      (node (ref "T1") (pin "1") (pinfunction "B_1") (pintype "input"))
      (node (ref "TP16") (pin "1") (pinfunction "1_1") (pintype "passive"))
      (node (ref "U1") (pin "43") (pinfunction "PF1_43") (pintype "bidirectional"))
    )
    (net (code "299") (name "PF2_LEDB") (class "Default")
      (node (ref "T3") (pin "1") (pinfunction "B_1") (pintype "input"))
      (node (ref "TP18") (pin "1") (pinfunction "1_1") (pintype "passive"))
      (node (ref "U1") (pin "44") (pinfunction "PF2_44") (pintype "bidirectional"))
    )
    (net (code "300") (name "PF3_LEDG") (class "Default")
      (node (ref "T2") (pin "1") (pinfunction "B_1") (pintype "input"))
      (node (ref "TP17") (pin "1") (pinfunction "1_1") (pintype "passive"))
      (node (ref "U1") (pin "45") (pinfunction "PF3_45") (pintype "bidirectional"))
    )
    (net (code "301") (name "PF4_ETH") (class "Default")
      (node (ref "T4") (pin "1") (pinfunction "B_1") (pintype "input"))
      (node (ref "TP23") (pin "1") (pinfunction "1_1") (pintype "passive"))
      (node (ref "U1") (pin "46") (pinfunction "PF4_46") (pintype "bidirectional"))
    )
    (net (code "302") (name "PJ1_FLASHWP") (class "Default")
      (node (ref "R17") (pin "2") (pinfunction "2_2") (pintype "passive"))
      (node (ref "SV2") (pin "3") (pinfunction "3_3") (pintype "passive"))
      (node (ref "U1") (pin "117") (pinfunction "PJ1_117") (pintype "bidirectional"))
    )
    (net (code "303") (name "PROGRAM") (class "Default")
      (node (ref "R1") (pin "2") (pinfunction "2_2") (pintype "passive"))
      (node (ref "TP19") (pin "1") (pinfunction "1_1") (pintype "passive"))
      (node (ref "U1") (pin "31") (pinfunction "PH2_31") (pintype "bidirectional"))
      (node (ref "U4") (pin "37") (pinfunction "PROGRAM_37") (pintype "input"))
    )
    (net (code "304") (name "RBIAS") (class "Default")
      (node (ref "R22") (pin "2") (pinfunction "2_2") (pintype "passive"))
      (node (ref "U1") (pin "59") (pinfunction "RBIAS_59") (pintype "bidirectional"))
    )
    (net (code "305") (name "RUPT0") (class "Default")
      (node (ref "RA9") (pin "2A") (pinfunction "2A_2A") (pintype "passive"))
      (node (ref "U1") (pin "118") (pinfunction "PP0_118") (pintype "bidirectional"))
    )
    (net (code "306") (name "RUPT1") (class "Default")
      (node (ref "RA9") (pin "1A") (pinfunction "1A_1A") (pintype "passive"))
      (node (ref "U1") (pin "119") (pinfunction "PP1_119") (pintype "bidirectional"))
    )
    (net (code "307") (name "RUPT2") (class "Default")
      (node (ref "RA9") (pin "4A") (pinfunction "4A_4A") (pintype "passive"))
      (node (ref "U1") (pin "105") (pinfunction "PP4_105") (pintype "bidirectional"))
    )
    (net (code "308") (name "RUPT3") (class "Default")
      (node (ref "RA9") (pin "3A") (pinfunction "3A_3A") (pintype "passive"))
      (node (ref "U1") (pin "106") (pinfunction "PP5_106") (pintype "bidirectional"))
    )
    (net (code "309") (name "SHIELD") (class "Default")
      (node (ref "L5") (pin "2") (pinfunction "F_2") (pintype "passive"))
      (node (ref "X6") (pin "Z1") (pinfunction "GND_Z1") (pintype "bidirectional"))
      (node (ref "X6") (pin "Z2") (pinfunction "GND_Z2") (pintype "bidirectional"))
      (node (ref "X8") (pin "Z1") (pinfunction "P$1_Z1") (pintype "power_in"))
      (node (ref "X8") (pin "Z2") (pinfunction "P$1_Z2") (pintype "power_in"))
    )
    (net (code "310") (name "SSI0CLK") (class "Default")
      (node (ref "TP12") (pin "1") (pinfunction "1_1") (pintype "passive"))
      (node (ref "U1") (pin "35") (pinfunction "PA2_35") (pintype "bidirectional"))
      (node (ref "U4") (pin "50") (pinfunction "IO_L31N_GCLK30_D15_50") (pintype "bidirectional"))
      (node (ref "U4") (pin "70") (pinfunction "IO_L1P_CCLK_70") (pintype "bidirectional"))
      (node (ref "U5") (pin "6") (pinfunction "CLK_6") (pintype "input"))
    )
    (net (code "311") (name "SSI0D0") (class "Default")
      (node (ref "TP13") (pin "1") (pinfunction "1_1") (pintype "passive"))
      (node (ref "U1") (pin "37") (pinfunction "PA4_37") (pintype "bidirectional"))
      (node (ref "U4") (pin "64") (pinfunction "IO_L3N_MOSI_CSI_B_MISO0_64") (pintype "bidirectional"))
      (node (ref "U5") (pin "5") (pinfunction "MOSI_5") (pintype "input"))
    )
    (net (code "312") (name "SSI0D1") (class "Default")
      (node (ref "TP14") (pin "1") (pinfunction "1_1") (pintype "passive"))
      (node (ref "U1") (pin "38") (pinfunction "PA5_38") (pintype "bidirectional"))
      (node (ref "U4") (pin "65") (pinfunction "IO_L3P_D0_DIN_MISO_MISO1_65") (pintype "bidirectional"))
      (node (ref "U5") (pin "2") (pinfunction "MISO_2") (pintype "output"))
    )
    (net (code "313") (name "SSI0FSS") (class "Default")
      (node (ref "TP15") (pin "1") (pinfunction "1_1") (pintype "passive"))
      (node (ref "U1") (pin "36") (pinfunction "PA3_36") (pintype "bidirectional"))
      (node (ref "U4") (pin "38") (pinfunction "IO_L65N_CSO_B_38") (pintype "bidirectional"))
      (node (ref "U5") (pin "1") (pinfunction "~{CS}_1") (pintype "input"))
    )
    (net (code "314") (name "USB0D_N") (class "Default")
      (node (ref "L3") (pin "4") (pinfunction "1_4") (pintype "passive"))
      (node (ref "U1") (pin "93") (pinfunction "PL7_93") (pintype "bidirectional"))
    )
    (net (code "315") (name "USB0D_P") (class "Default")
      (node (ref "L3") (pin "1") (pinfunction "4_1") (pintype "passive"))
      (node (ref "U1") (pin "94") (pinfunction "PL6_94") (pintype "bidirectional"))
    )
    (net (code "316") (name "USB_DETECT") (class "Default")
      (node (ref "R29") (pin "1") (pinfunction "1_1") (pintype "passive"))
      (node (ref "R30") (pin "2") (pinfunction "2_2") (pintype "passive"))
      (node (ref "TP22") (pin "1") (pinfunction "1_1") (pintype "passive"))
      (node (ref "U1") (pin "63") (pinfunction "PK4_63") (pintype "bidirectional"))
    )
    (net (code "317") (name "VBUS") (class "Default")
      (node (ref "D1") (pin "5") (pinfunction "VDD_5") (pintype "power_in"))
      (node (ref "L4") (pin "2") (pinfunction "F_2") (pintype "passive"))
      (node (ref "X6") (pin "1") (pinfunction "VCC_1") (pintype "passive"))
    )
    (net (code "318") (name "VEXT_A") (class "Default")
      (node (ref "X1") (pin "45") (pinfunction "45_45") (pintype "bidirectional"))
      (node (ref "X1") (pin "46") (pinfunction "46_46") (pintype "bidirectional"))
      (node (ref "X1") (pin "47") (pinfunction "47_47") (pintype "bidirectional"))
      (node (ref "X11") (pin "32") (pinfunction "32_32") (pintype "passive"))
      (node (ref "X12") (pin "32") (pinfunction "32_32") (pintype "passive"))
      (node (ref "X13") (pin "32") (pinfunction "32_32") (pintype "passive"))
      (node (ref "X2") (pin "45") (pinfunction "45_45") (pintype "bidirectional"))
      (node (ref "X2") (pin "46") (pinfunction "46_46") (pintype "bidirectional"))
      (node (ref "X2") (pin "47") (pinfunction "47_47") (pintype "bidirectional"))
      (node (ref "X3") (pin "45") (pinfunction "45_45") (pintype "bidirectional"))
      (node (ref "X3") (pin "46") (pinfunction "46_46") (pintype "bidirectional"))
      (node (ref "X3") (pin "47") (pinfunction "47_47") (pintype "bidirectional"))
      (node (ref "X4") (pin "45") (pinfunction "45_45") (pintype "bidirectional"))
      (node (ref "X4") (pin "46") (pinfunction "46_46") (pintype "bidirectional"))
      (node (ref "X4") (pin "47") (pinfunction "47_47") (pintype "bidirectional"))
      (node (ref "X5") (pin "14") (pinfunction "14_14") (pintype "passive"))
      (node (ref "X5") (pin "16") (pinfunction "16_16") (pintype "passive"))
      (node (ref "X5") (pin "18") (pinfunction "18_18") (pintype "passive"))
      (node (ref "X7") (pin "32") (pinfunction "32_32") (pintype "passive"))
    )
    (net (code "319") (name "VEXT_B") (class "Default")
      (node (ref "X1") (pin "48") (pinfunction "48_48") (pintype "bidirectional"))
      (node (ref "X1") (pin "49") (pinfunction "49_49") (pintype "bidirectional"))
      (node (ref "X1") (pin "50") (pinfunction "50_50") (pintype "bidirectional"))
      (node (ref "X11") (pin "34") (pinfunction "34_34") (pintype "passive"))
      (node (ref "X12") (pin "34") (pinfunction "34_34") (pintype "passive"))
      (node (ref "X13") (pin "34") (pinfunction "34_34") (pintype "passive"))
      (node (ref "X2") (pin "48") (pinfunction "48_48") (pintype "bidirectional"))
      (node (ref "X2") (pin "49") (pinfunction "49_49") (pintype "bidirectional"))
      (node (ref "X2") (pin "50") (pinfunction "50_50") (pintype "bidirectional"))
      (node (ref "X3") (pin "48") (pinfunction "48_48") (pintype "bidirectional"))
      (node (ref "X3") (pin "49") (pinfunction "49_49") (pintype "bidirectional"))
      (node (ref "X3") (pin "50") (pinfunction "50_50") (pintype "bidirectional"))
      (node (ref "X4") (pin "48") (pinfunction "48_48") (pintype "bidirectional"))
      (node (ref "X4") (pin "49") (pinfunction "49_49") (pintype "bidirectional"))
      (node (ref "X4") (pin "50") (pinfunction "50_50") (pintype "bidirectional"))
      (node (ref "X5") (pin "20") (pinfunction "20_20") (pintype "passive"))
      (node (ref "X5") (pin "22") (pinfunction "22_22") (pintype "passive"))
      (node (ref "X5") (pin "24") (pinfunction "24_24") (pintype "passive"))
      (node (ref "X7") (pin "34") (pinfunction "34_34") (pintype "passive"))
    )
    (net (code "320") (name "X3V3") (class "Default")
      (node (ref "X1") (pin "4") (pinfunction "4_4") (pintype "bidirectional"))
      (node (ref "X1") (pin "5") (pinfunction "5_5") (pintype "bidirectional"))
      (node (ref "X1") (pin "6") (pinfunction "6_6") (pintype "bidirectional"))
      (node (ref "X11") (pin "4") (pinfunction "4_4") (pintype "passive"))
      (node (ref "X12") (pin "4") (pinfunction "4_4") (pintype "passive"))
      (node (ref "X13") (pin "4") (pinfunction "4_4") (pintype "passive"))
      (node (ref "X2") (pin "4") (pinfunction "4_4") (pintype "bidirectional"))
      (node (ref "X2") (pin "5") (pinfunction "5_5") (pintype "bidirectional"))
      (node (ref "X2") (pin "6") (pinfunction "6_6") (pintype "bidirectional"))
      (node (ref "X3") (pin "4") (pinfunction "4_4") (pintype "bidirectional"))
      (node (ref "X3") (pin "5") (pinfunction "5_5") (pintype "bidirectional"))
      (node (ref "X3") (pin "6") (pinfunction "6_6") (pintype "bidirectional"))
      (node (ref "X4") (pin "4") (pinfunction "4_4") (pintype "bidirectional"))
      (node (ref "X4") (pin "5") (pinfunction "5_5") (pintype "bidirectional"))
      (node (ref "X4") (pin "6") (pinfunction "6_6") (pintype "bidirectional"))
      (node (ref "X5") (pin "2") (pinfunction "2_2") (pintype "passive"))
      (node (ref "X5") (pin "4") (pinfunction "4_4") (pintype "passive"))
      (node (ref "X5") (pin "6") (pinfunction "6_6") (pintype "passive"))
      (node (ref "X7") (pin "4") (pinfunction "4_4") (pintype "passive"))
    )
    (net (code "321") (name "X5V") (class "Default")
      (node (ref "SW2") (pin "3") (pinfunction "3_3") (pintype "bidirectional"))
      (node (ref "X5") (pin "10") (pinfunction "10_10") (pintype "passive"))
      (node (ref "X5") (pin "12") (pinfunction "12_12") (pintype "passive"))
      (node (ref "X5") (pin "8") (pinfunction "8_8") (pintype "passive"))
    )
    (net (code "322") (name "unconnected-(RA12-Pad3A)") (class "Default")
      (node (ref "RA12") (pin "3A") (pinfunction "3A_3A") (pintype "passive"))
    )
    (net (code "323") (name "unconnected-(RA12-Pad3B)") (class "Default")
      (node (ref "RA12") (pin "3B") (pinfunction "3B_3B") (pintype "passive"))
    )
    (net (code "324") (name "unconnected-(RA12-Pad4A)") (class "Default")
      (node (ref "RA12") (pin "4A") (pinfunction "4A_4A") (pintype "passive"))
    )
    (net (code "325") (name "unconnected-(RA12-Pad4B)") (class "Default")
      (node (ref "RA12") (pin "4B") (pinfunction "4B_4B") (pintype "passive"))
    )
    (net (code "326") (name "unconnected-(RA14-Pad3B)") (class "Default")
      (node (ref "RA14") (pin "3B") (pinfunction "3B_3B") (pintype "passive"))
    )
    (net (code "327") (name "unconnected-(RA14-Pad4B)") (class "Default")
      (node (ref "RA14") (pin "4B") (pinfunction "4B_4B") (pintype "passive"))
    )
    (net (code "328") (name "unconnected-(RA15-Pad1B)") (class "Default")
      (node (ref "RA15") (pin "1B") (pinfunction "1B_1B") (pintype "passive"))
    )
    (net (code "329") (name "unconnected-(RA15-Pad2B)") (class "Default")
      (node (ref "RA15") (pin "2B") (pinfunction "2B_2B") (pintype "passive"))
    )
    (net (code "330") (name "unconnected-(RA15-Pad3B)") (class "Default")
      (node (ref "RA15") (pin "3B") (pinfunction "3B_3B") (pintype "passive"))
    )
    (net (code "331") (name "unconnected-(RA15-Pad4B)") (class "Default")
      (node (ref "RA15") (pin "4B") (pinfunction "4B_4B") (pintype "passive"))
    )
    (net (code "332") (name "unconnected-(RA16-Pad1B)") (class "Default")
      (node (ref "RA16") (pin "1B") (pinfunction "1B_1B") (pintype "passive"))
    )
    (net (code "333") (name "unconnected-(RA16-Pad2B)") (class "Default")
      (node (ref "RA16") (pin "2B") (pinfunction "2B_2B") (pintype "passive"))
    )
    (net (code "334") (name "unconnected-(RA16-Pad3B)") (class "Default")
      (node (ref "RA16") (pin "3B") (pinfunction "3B_3B") (pintype "passive"))
    )
    (net (code "335") (name "unconnected-(RA16-Pad4B)") (class "Default")
      (node (ref "RA16") (pin "4B") (pinfunction "4B_4B") (pintype "passive"))
    )
    (net (code "336") (name "unconnected-(RA19-Pad3A)") (class "Default")
      (node (ref "RA19") (pin "3A") (pinfunction "3A_3A") (pintype "passive"))
    )
    (net (code "337") (name "unconnected-(RA19-Pad3B)") (class "Default")
      (node (ref "RA19") (pin "3B") (pinfunction "3B_3B") (pintype "passive"))
    )
    (net (code "338") (name "unconnected-(RA19-Pad4A)") (class "Default")
      (node (ref "RA19") (pin "4A") (pinfunction "4A_4A") (pintype "passive"))
    )
    (net (code "339") (name "unconnected-(RA19-Pad4B)") (class "Default")
      (node (ref "RA19") (pin "4B") (pinfunction "4B_4B") (pintype "passive"))
    )
    (net (code "340") (name "unconnected-(RA21-Pad3A)") (class "Default")
      (node (ref "RA21") (pin "3A") (pinfunction "3A_3A") (pintype "passive"))
    )
    (net (code "341") (name "unconnected-(RA21-Pad4A)") (class "Default")
      (node (ref "RA21") (pin "4A") (pinfunction "4A_4A") (pintype "passive"))
    )
    (net (code "342") (name "unconnected-(RA22-Pad1B)") (class "Default")
      (node (ref "RA22") (pin "1B") (pinfunction "1B_1B") (pintype "passive"))
    )
    (net (code "343") (name "unconnected-(RA22-Pad2B)") (class "Default")
      (node (ref "RA22") (pin "2B") (pinfunction "2B_2B") (pintype "passive"))
    )
    (net (code "344") (name "unconnected-(RA22-Pad3B)") (class "Default")
      (node (ref "RA22") (pin "3B") (pinfunction "3B_3B") (pintype "passive"))
    )
    (net (code "345") (name "unconnected-(RA22-Pad4B)") (class "Default")
      (node (ref "RA22") (pin "4B") (pinfunction "4B_4B") (pintype "passive"))
    )
    (net (code "346") (name "unconnected-(RA23-Pad1B)") (class "Default")
      (node (ref "RA23") (pin "1B") (pinfunction "1B_1B") (pintype "passive"))
    )
    (net (code "347") (name "unconnected-(RA23-Pad2B)") (class "Default")
      (node (ref "RA23") (pin "2B") (pinfunction "2B_2B") (pintype "passive"))
    )
    (net (code "348") (name "unconnected-(RA23-Pad3B)") (class "Default")
      (node (ref "RA23") (pin "3B") (pinfunction "3B_3B") (pintype "passive"))
    )
    (net (code "349") (name "unconnected-(RA23-Pad4B)") (class "Default")
      (node (ref "RA23") (pin "4B") (pinfunction "4B_4B") (pintype "passive"))
    )
    (net (code "350") (name "unconnected-(RA28-Pad1B)") (class "Default")
      (node (ref "RA28") (pin "1B") (pinfunction "1B_1B") (pintype "passive"))
    )
    (net (code "351") (name "unconnected-(RA28-Pad2B)") (class "Default")
      (node (ref "RA28") (pin "2B") (pinfunction "2B_2B") (pintype "passive"))
    )
    (net (code "352") (name "unconnected-(RA28-Pad3B)") (class "Default")
      (node (ref "RA28") (pin "3B") (pinfunction "3B_3B") (pintype "passive"))
    )
    (net (code "353") (name "unconnected-(RA28-Pad4B)") (class "Default")
      (node (ref "RA28") (pin "4B") (pinfunction "4B_4B") (pintype "passive"))
    )
    (net (code "354") (name "unconnected-(RA29-Pad1B)") (class "Default")
      (node (ref "RA29") (pin "1B") (pinfunction "1B_1B") (pintype "passive"))
    )
    (net (code "355") (name "unconnected-(RA29-Pad2B)") (class "Default")
      (node (ref "RA29") (pin "2B") (pinfunction "2B_2B") (pintype "passive"))
    )
    (net (code "356") (name "unconnected-(RA29-Pad3B)") (class "Default")
      (node (ref "RA29") (pin "3B") (pinfunction "3B_3B") (pintype "passive"))
    )
    (net (code "357") (name "unconnected-(RA29-Pad4B)") (class "Default")
      (node (ref "RA29") (pin "4B") (pinfunction "4B_4B") (pintype "passive"))
    )
    (net (code "358") (name "unconnected-(RA30-Pad1B)") (class "Default")
      (node (ref "RA30") (pin "1B") (pinfunction "1B_1B") (pintype "passive"))
    )
    (net (code "359") (name "unconnected-(RA30-Pad2B)") (class "Default")
      (node (ref "RA30") (pin "2B") (pinfunction "2B_2B") (pintype "passive"))
    )
    (net (code "360") (name "unconnected-(RA30-Pad3A)") (class "Default")
      (node (ref "RA30") (pin "3A") (pinfunction "3A_3A") (pintype "passive"))
    )
    (net (code "361") (name "unconnected-(RA30-Pad3B)") (class "Default")
      (node (ref "RA30") (pin "3B") (pinfunction "3B_3B") (pintype "passive"))
    )
    (net (code "362") (name "unconnected-(RA30-Pad4A)") (class "Default")
      (node (ref "RA30") (pin "4A") (pinfunction "4A_4A") (pintype "passive"))
    )
    (net (code "363") (name "unconnected-(RA30-Pad4B)") (class "Default")
      (node (ref "RA30") (pin "4B") (pinfunction "4B_4B") (pintype "passive"))
    )
    (net (code "364") (name "unconnected-(RA35-Pad1B)") (class "Default")
      (node (ref "RA35") (pin "1B") (pinfunction "1B_1B") (pintype "passive"))
    )
    (net (code "365") (name "unconnected-(RA35-Pad2B)") (class "Default")
      (node (ref "RA35") (pin "2B") (pinfunction "2B_2B") (pintype "passive"))
    )
    (net (code "366") (name "unconnected-(RA35-Pad3B)") (class "Default")
      (node (ref "RA35") (pin "3B") (pinfunction "3B_3B") (pintype "passive"))
    )
    (net (code "367") (name "unconnected-(RA35-Pad4B)") (class "Default")
      (node (ref "RA35") (pin "4B") (pinfunction "4B_4B") (pintype "passive"))
    )
    (net (code "368") (name "unconnected-(RA36-Pad1B)") (class "Default")
      (node (ref "RA36") (pin "1B") (pinfunction "1B_1B") (pintype "passive"))
    )
    (net (code "369") (name "unconnected-(RA36-Pad2B)") (class "Default")
      (node (ref "RA36") (pin "2B") (pinfunction "2B_2B") (pintype "passive"))
    )
    (net (code "370") (name "unconnected-(RA36-Pad3B)") (class "Default")
      (node (ref "RA36") (pin "3B") (pinfunction "3B_3B") (pintype "passive"))
    )
    (net (code "371") (name "unconnected-(RA36-Pad4B)") (class "Default")
      (node (ref "RA36") (pin "4B") (pinfunction "4B_4B") (pintype "passive"))
    )
    (net (code "372") (name "unconnected-(RA37-Pad1B)") (class "Default")
      (node (ref "RA37") (pin "1B") (pinfunction "1B_1B") (pintype "passive"))
    )
    (net (code "373") (name "unconnected-(RA37-Pad2B)") (class "Default")
      (node (ref "RA37") (pin "2B") (pinfunction "2B_2B") (pintype "passive"))
    )
    (net (code "374") (name "unconnected-(RA37-Pad3A)") (class "Default")
      (node (ref "RA37") (pin "3A") (pinfunction "3A_3A") (pintype "passive"))
    )
    (net (code "375") (name "unconnected-(RA37-Pad3B)") (class "Default")
      (node (ref "RA37") (pin "3B") (pinfunction "3B_3B") (pintype "passive"))
    )
    (net (code "376") (name "unconnected-(RA37-Pad4A)") (class "Default")
      (node (ref "RA37") (pin "4A") (pinfunction "4A_4A") (pintype "passive"))
    )
    (net (code "377") (name "unconnected-(RA37-Pad4B)") (class "Default")
      (node (ref "RA37") (pin "4B") (pinfunction "4B_4B") (pintype "passive"))
    )
    (net (code "378") (name "unconnected-(U1A-PJ0-Pad116)") (class "Default")
      (node (ref "U1") (pin "116") (pinfunction "PJ0_116") (pintype "bidirectional"))
    )
    (net (code "379") (name "unconnected-(U1A-PQ4-Pad102)") (class "Default")
      (node (ref "U1") (pin "102") (pinfunction "PQ4_102") (pintype "bidirectional"))
    )
    (net (code "380") (name "unconnected-(U1A-XOSC0-Pad66)") (class "Default")
      (node (ref "U1") (pin "66") (pinfunction "XOSC0_66") (pintype "bidirectional"))
    )
    (net (code "381") (name "unconnected-(U1A-XOSC1-Pad67)") (class "Default")
      (node (ref "U1") (pin "67") (pinfunction "XOSC1_67") (pintype "bidirectional"))
    )
    (net (code "382") (name "unconnected-(U4A-IO_L1N_VREF-Pad143)") (class "Default")
      (node (ref "U4") (pin "143") (pinfunction "IO_L1N_VREF_143") (pintype "bidirectional"))
    )
    (net (code "383") (name "unconnected-(U4A-IO_L1P_HSWAPEN-Pad144)") (class "Default")
      (node (ref "U4") (pin "144") (pinfunction "IO_L1P_HSWAPEN_144") (pintype "bidirectional"))
    )
    (net (code "384") (name "unconnected-(U4C-IO_L12N_D2_MISO3-Pad61)") (class "Default")
      (node (ref "U4") (pin "61") (pinfunction "IO_L12N_D2_MISO3_61") (pintype "bidirectional"))
    )
    (net (code "385") (name "unconnected-(U4C-IO_L13N_D10-Pad59)") (class "Default")
      (node (ref "U4") (pin "59") (pinfunction "IO_L13N_D10_59") (pintype "bidirectional"))
    )
    (net (code "386") (name "unconnected-(U4C-IO_L14N_D12-Pad57)") (class "Default")
      (node (ref "U4") (pin "57") (pinfunction "IO_L14N_D12_57") (pintype "bidirectional"))
    )
    (net (code "387") (name "unconnected-(U4C-IO_L14P_D11-Pad58)") (class "Default")
      (node (ref "U4") (pin "58") (pinfunction "IO_L14P_D11_58") (pintype "bidirectional"))
    )
    (net (code "388") (name "unconnected-(U4C-IO_L30N_GCLK0_USERCCLK-Pad55)") (class "Default")
      (node (ref "U4") (pin "55") (pinfunction "IO_L30N_GCLK0_USERCCLK_55") (pintype "bidirectional"))
    )
    (net (code "389") (name "unconnected-(U4C-IO_L48N_RDWR_B_VREF-Pad47)") (class "Default")
      (node (ref "U4") (pin "47") (pinfunction "IO_L48N_RDWR_B_VREF_47") (pintype "bidirectional"))
    )
    (net (code "390") (name "unconnected-(U4C-IO_L48P_D7-Pad48)") (class "Default")
      (node (ref "U4") (pin "48") (pinfunction "IO_L48P_D7_48") (pintype "bidirectional"))
    )
    (net (code "391") (name "unconnected-(U4C-IO_L49N_D4-Pad45)") (class "Default")
      (node (ref "U4") (pin "45") (pinfunction "IO_L49N_D4_45") (pintype "bidirectional"))
    )
    (net (code "392") (name "unconnected-(U4C-IO_L49P_D3-Pad46)") (class "Default")
      (node (ref "U4") (pin "46") (pinfunction "IO_L49P_D3_46") (pintype "bidirectional"))
    )
    (net (code "393") (name "unconnected-(U4C-IO_L62N_D6-Pad43)") (class "Default")
      (node (ref "U4") (pin "43") (pinfunction "IO_L62N_D6_43") (pintype "bidirectional"))
    )
    (net (code "394") (name "unconnected-(U4C-IO_L62P_D5-Pad44)") (class "Default")
      (node (ref "U4") (pin "44") (pinfunction "IO_L62P_D5_44") (pintype "bidirectional"))
    )
    (net (code "395") (name "unconnected-(U4C-IO_L64N_D9-Pad40)") (class "Default")
      (node (ref "U4") (pin "40") (pinfunction "IO_L64N_D9_40") (pintype "bidirectional"))
    )
    (net (code "396") (name "unconnected-(U4C-IO_L64P_D8-Pad41)") (class "Default")
      (node (ref "U4") (pin "41") (pinfunction "IO_L64P_D8_41") (pintype "bidirectional"))
    )
    (net (code "397") (name "unconnected-(U4D-IO_L49N-Pad11)") (class "Default")
      (node (ref "U4") (pin "11") (pinfunction "IO_L49N_11") (pintype "bidirectional"))
    )
    (net (code "398") (name "unconnected-(U4D-IO_L49P-Pad12)") (class "Default")
      (node (ref "U4") (pin "12") (pinfunction "IO_L49P_12") (pintype "bidirectional"))
    )
    (net (code "399") (name "unconnected-(U4D-IO_L50N-Pad9)") (class "Default")
      (node (ref "U4") (pin "9") (pinfunction "IO_L50N_9") (pintype "bidirectional"))
    )
    (net (code "400") (name "unconnected-(U4D-IO_L50P-Pad10)") (class "Default")
      (node (ref "U4") (pin "10") (pinfunction "IO_L50P_10") (pintype "bidirectional"))
    )
    (net (code "401") (name "unconnected-(U4D-IO_L51N-Pad7)") (class "Default")
      (node (ref "U4") (pin "7") (pinfunction "IO_L51N_7") (pintype "bidirectional"))
    )
    (net (code "402") (name "unconnected-(U4D-IO_L51P-Pad8)") (class "Default")
      (node (ref "U4") (pin "8") (pinfunction "IO_L51P_8") (pintype "bidirectional"))
    )
    (net (code "403") (name "unconnected-(U4D-IO_L52N-Pad5)") (class "Default")
      (node (ref "U4") (pin "5") (pinfunction "IO_L52N_5") (pintype "bidirectional"))
    )
    (net (code "404") (name "unconnected-(U4D-IO_L52P-Pad6)") (class "Default")
      (node (ref "U4") (pin "6") (pinfunction "IO_L52P_6") (pintype "bidirectional"))
    )
    (net (code "405") (name "unconnected-(U4D-IO_L83N_VREF-Pad1)") (class "Default")
      (node (ref "U4") (pin "1") (pinfunction "IO_L83N_VREF_1") (pintype "bidirectional"))
    )
    (net (code "406") (name "unconnected-(U4D-IO_L83P-Pad2)") (class "Default")
      (node (ref "U4") (pin "2") (pinfunction "IO_L83P_2") (pintype "bidirectional"))
    )
    (net (code "407") (name "unconnected-(U4F-CMPCS-Pad72)") (class "Default")
      (node (ref "U4") (pin "72") (pinfunction "CMPCS_72") (pintype "bidirectional"))
    )
    (net (code "408") (name "unconnected-(X23-Pad12)") (class "Default")
      (node (ref "X23") (pin "12") (pinfunction "12_12") (pintype "passive"))
    )
    (net (code "409") (name "unconnected-(X23-Pad14)") (class "Default")
      (node (ref "X23") (pin "14") (pinfunction "14_14") (pintype "passive"))
    )
    (net (code "410") (name "unconnected-(X24-Pad9)") (class "Default")
      (node (ref "X24") (pin "9") (pinfunction "9_9") (pintype "passive"))
    )
    (net (code "411") (name "~{HIB}") (class "Default")
      (node (ref "R16") (pin "2") (pinfunction "2_2") (pintype "passive"))
      (node (ref "TP8") (pin "1") (pinfunction "1_1") (pintype "passive"))
      (node (ref "U1") (pin "65") (pinfunction "~{HIB}_65") (pintype "bidirectional"))
    )
    (net (code "412") (name "~{RST}") (class "Default")
      (node (ref "C51") (pin "1") (pinfunction "1_1") (pintype "passive"))
      (node (ref "R13") (pin "1") (pinfunction "1_1") (pintype "passive"))
      (node (ref "R14") (pin "2") (pinfunction "2_2") (pintype "passive"))
      (node (ref "TP6") (pin "1") (pinfunction "1_1") (pintype "passive"))
      (node (ref "U1") (pin "70") (pinfunction "~{RST}_70") (pintype "bidirectional"))
      (node (ref "X24") (pin "10") (pinfunction "10_10") (pintype "passive"))
    )
    (net (code "413") (name "~{WAKE}") (class "Default")
      (node (ref "R15") (pin "2") (pinfunction "2_2") (pintype "passive"))
      (node (ref "TP7") (pin "1") (pinfunction "1_1") (pintype "passive"))
      (node (ref "U1") (pin "64") (pinfunction "~{WAKE}_64") (pintype "bidirectional"))
    )
  )
)
